# Full_bridge-2-Buck_drives_-10.net
KiCad netlist of a schematic drawn in Altium Designer
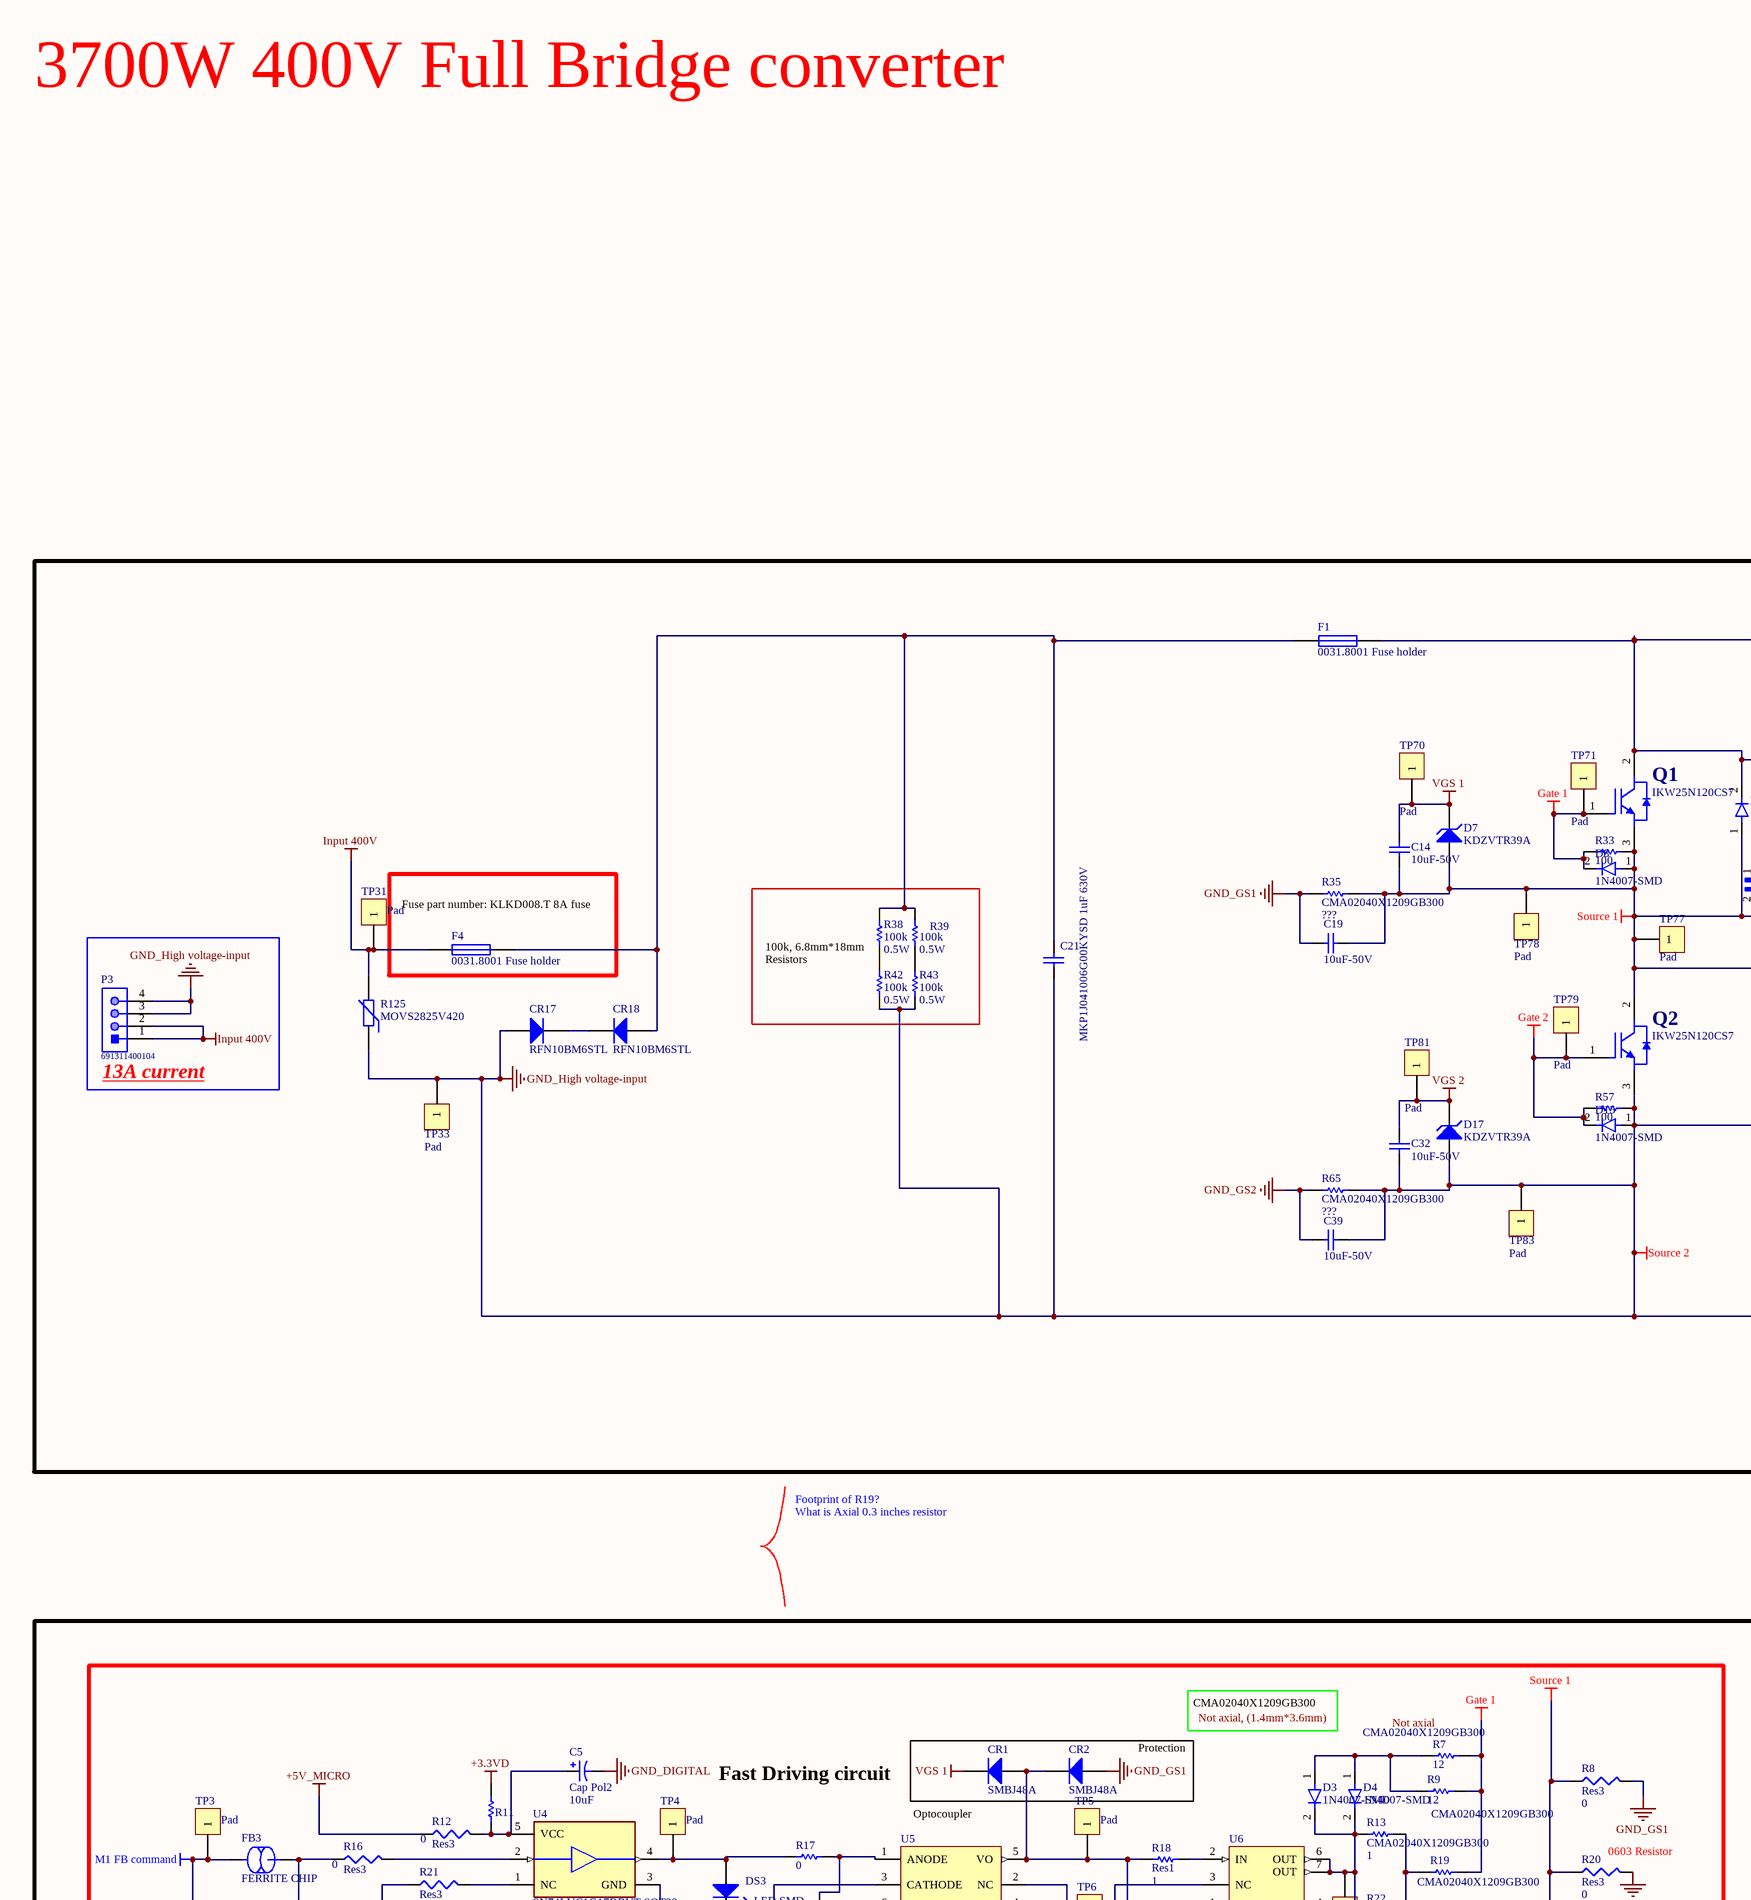
[diagram p0: Full bridge-2-Buck drives -10.SchDoc, top left]
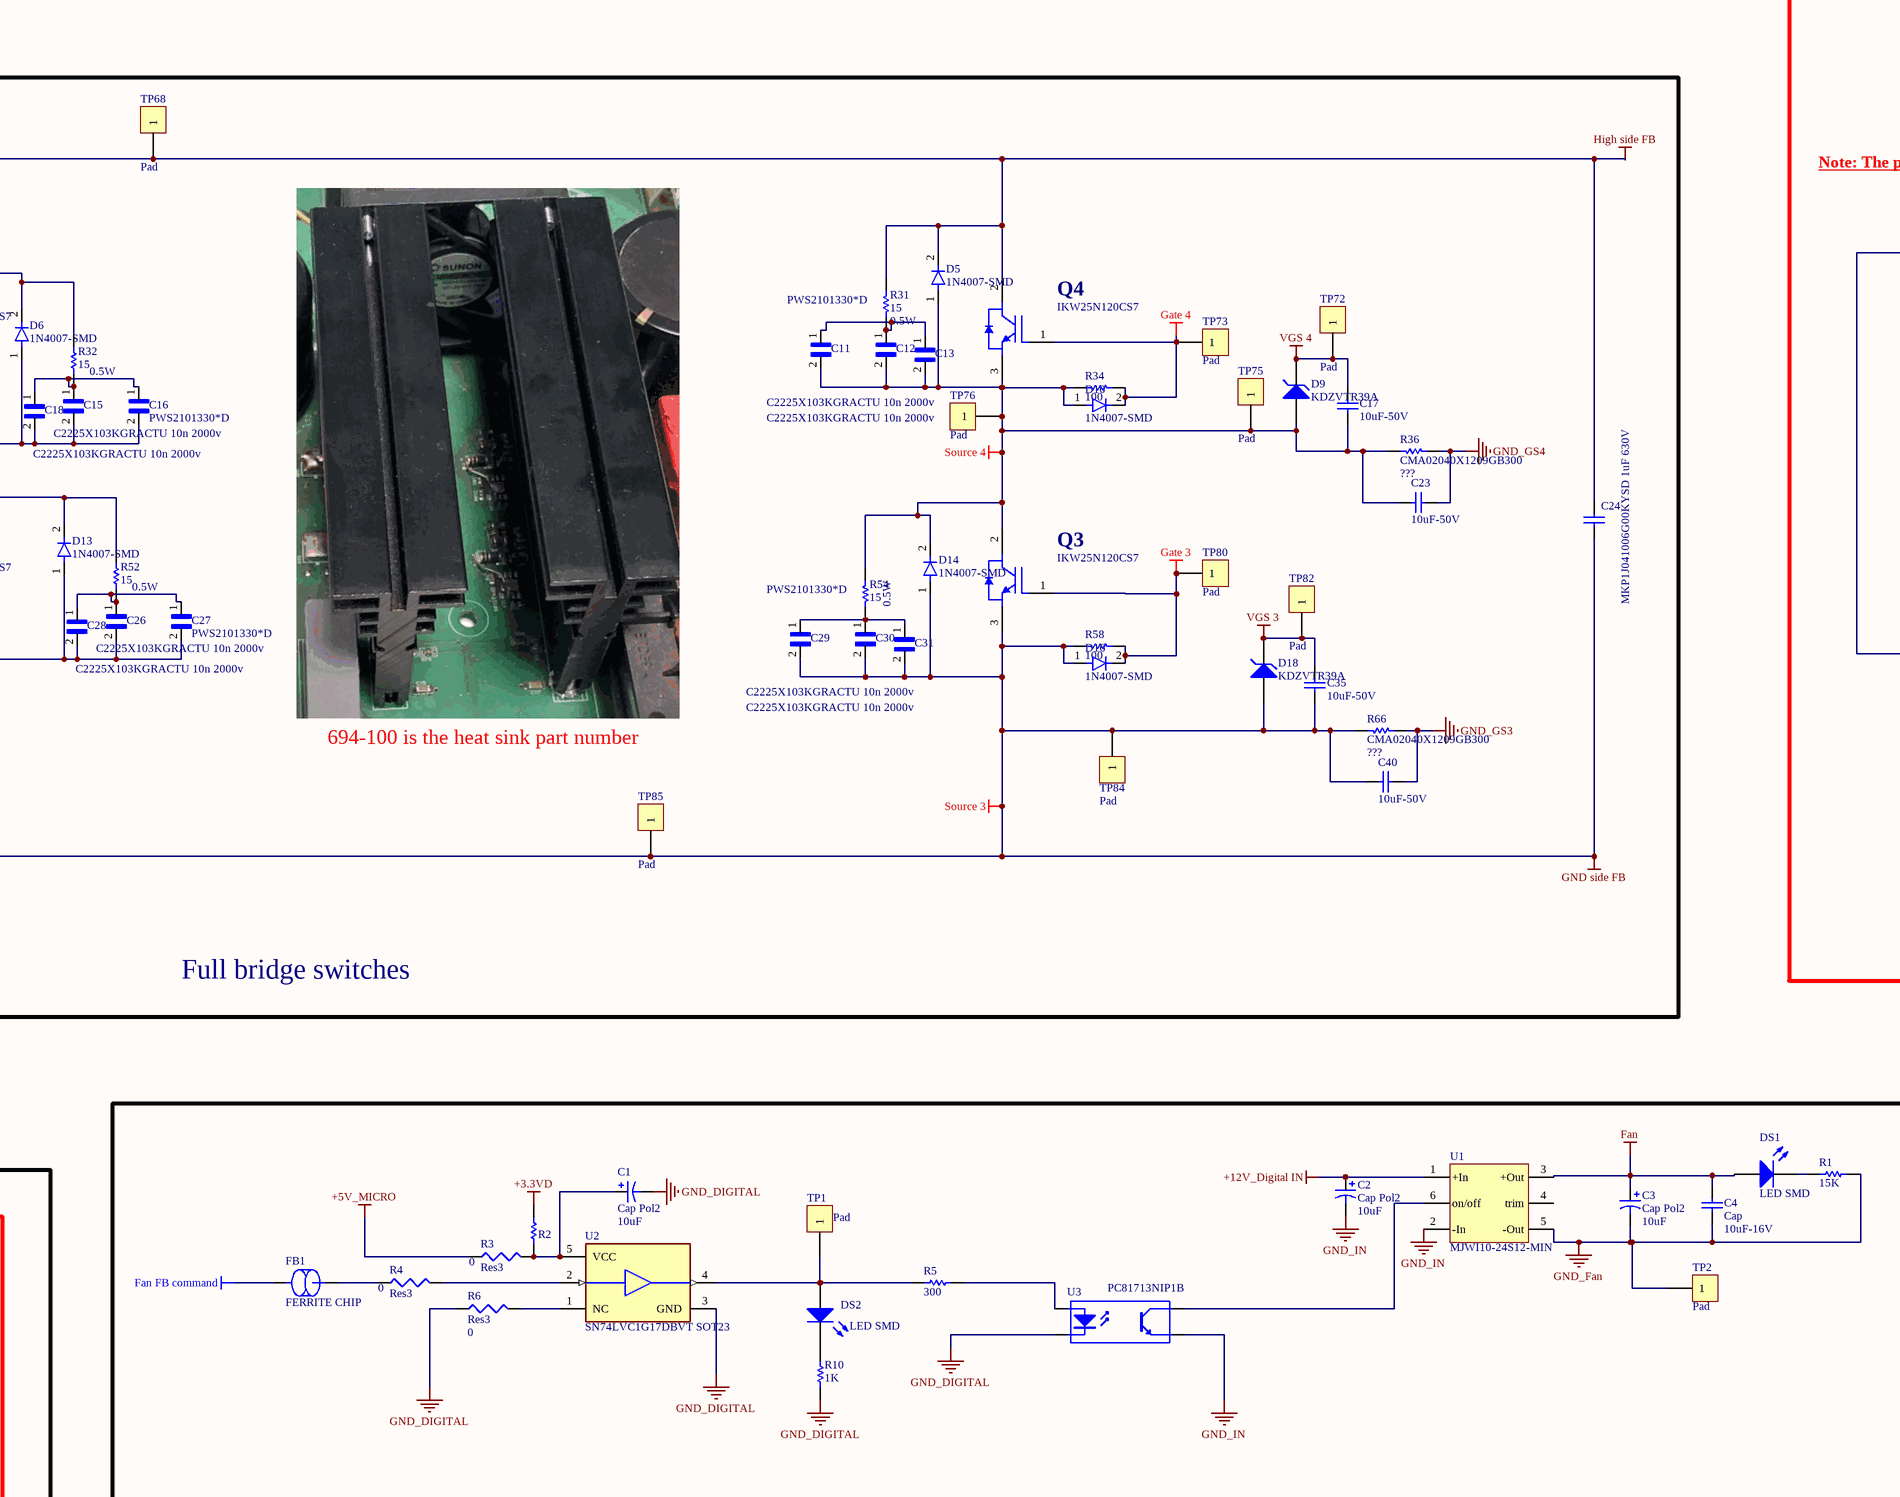
[diagram p1: Full bridge-2-Buck drives -10.SchDoc, top middle]
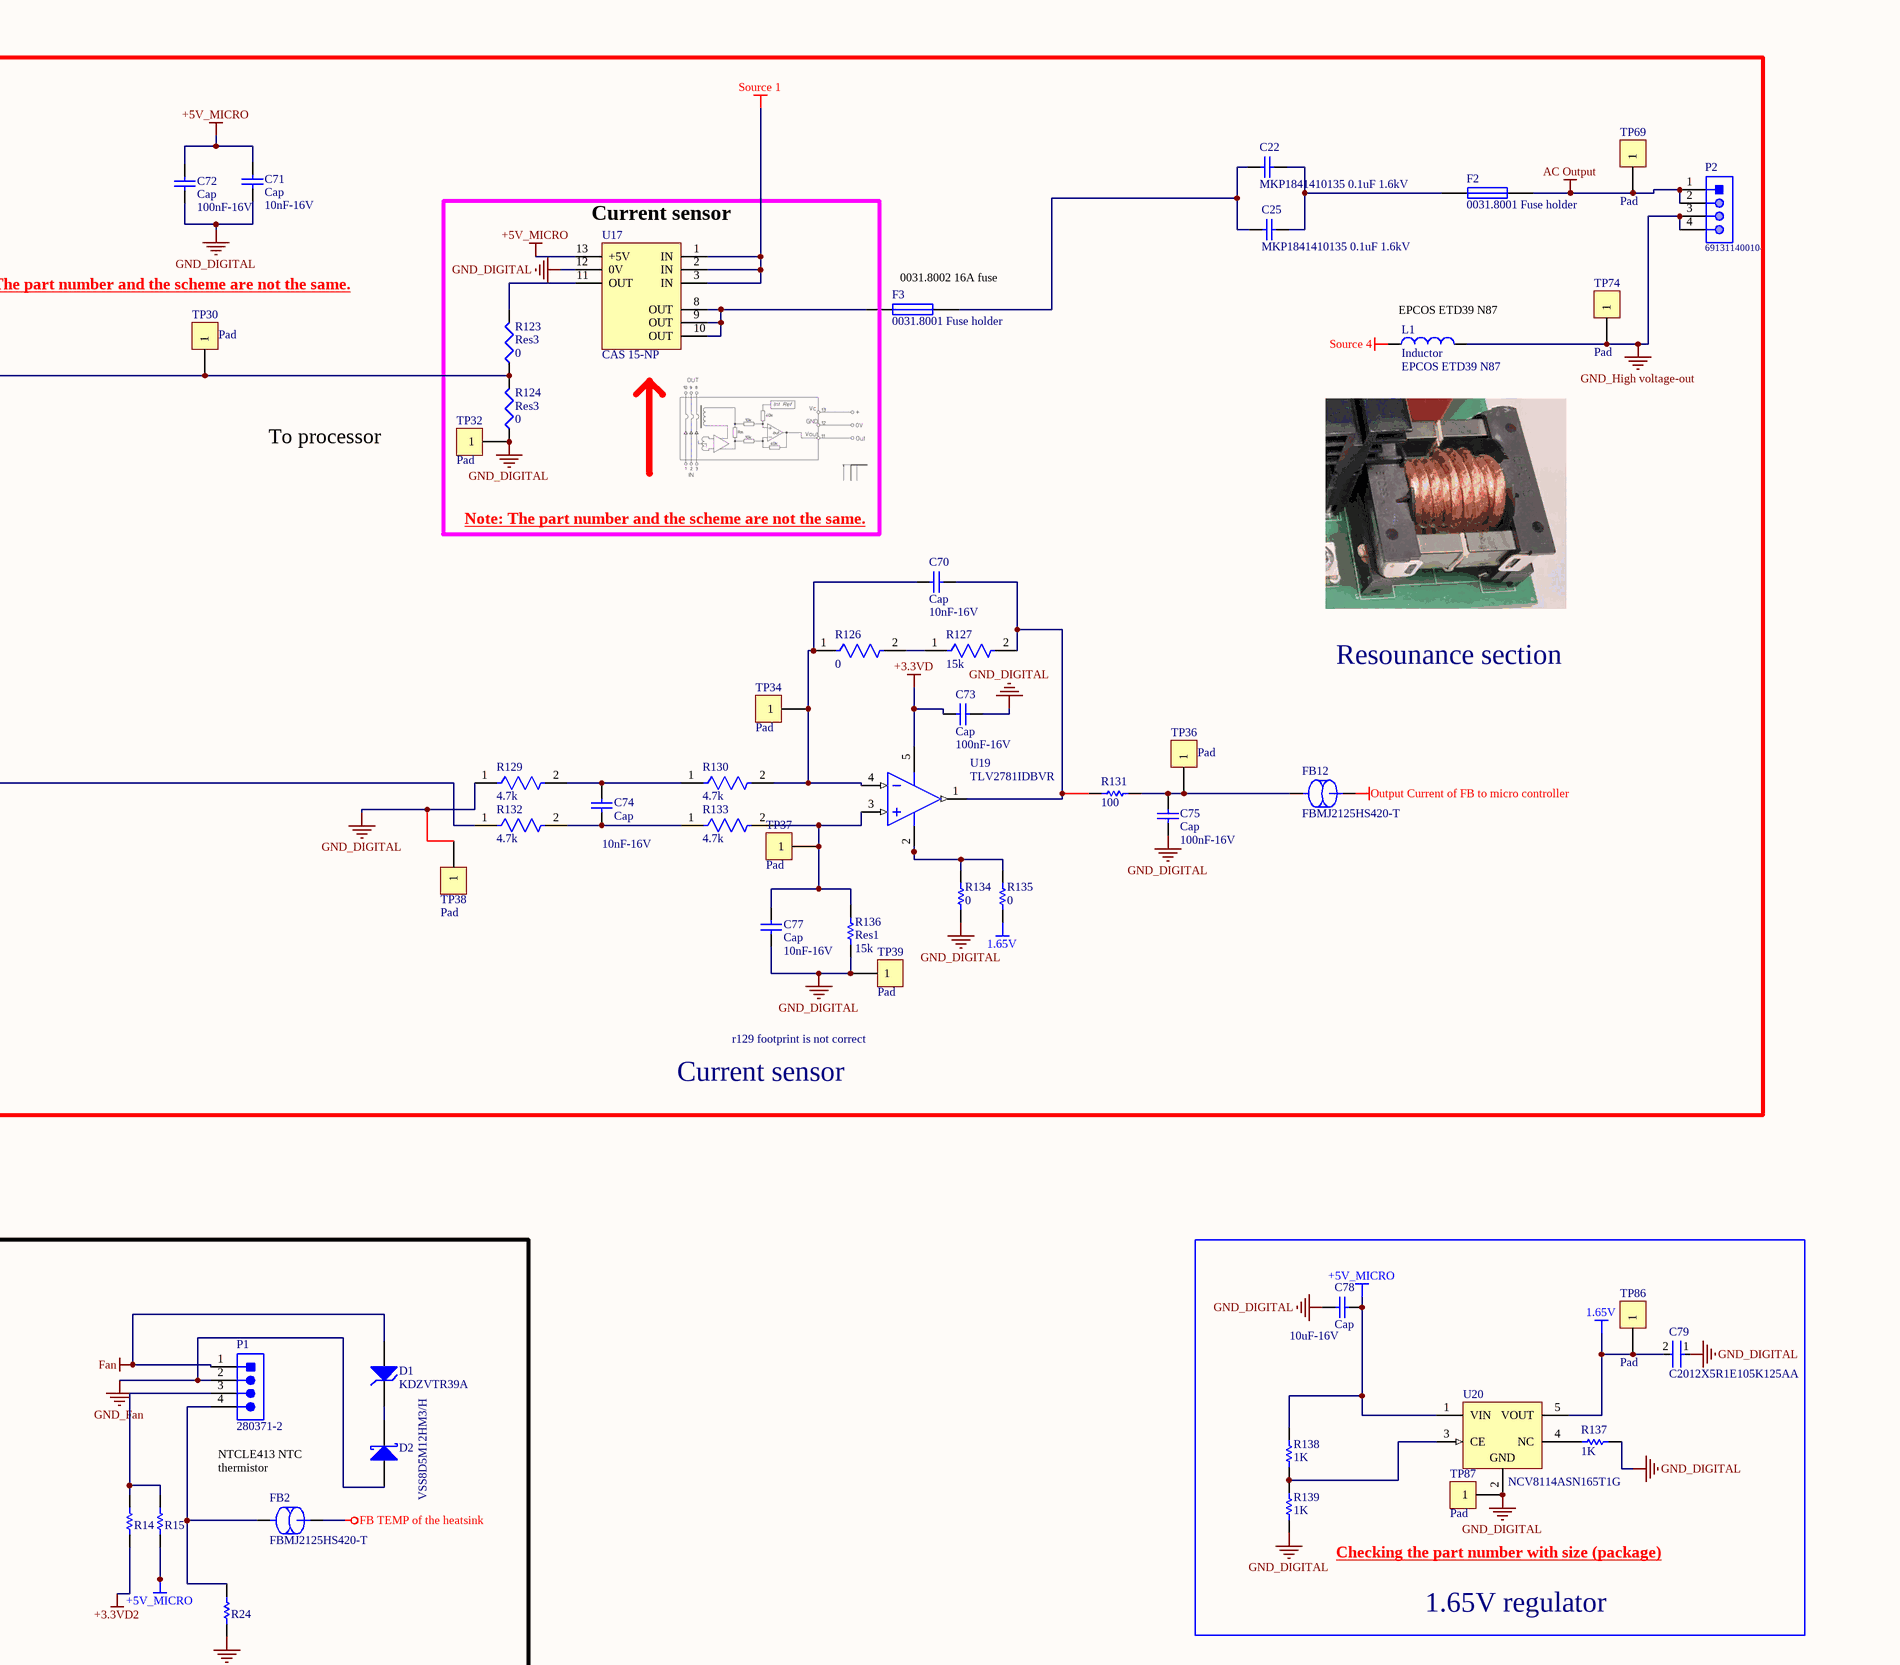
[diagram p2: Full bridge-2-Buck drives -10.SchDoc, top right]
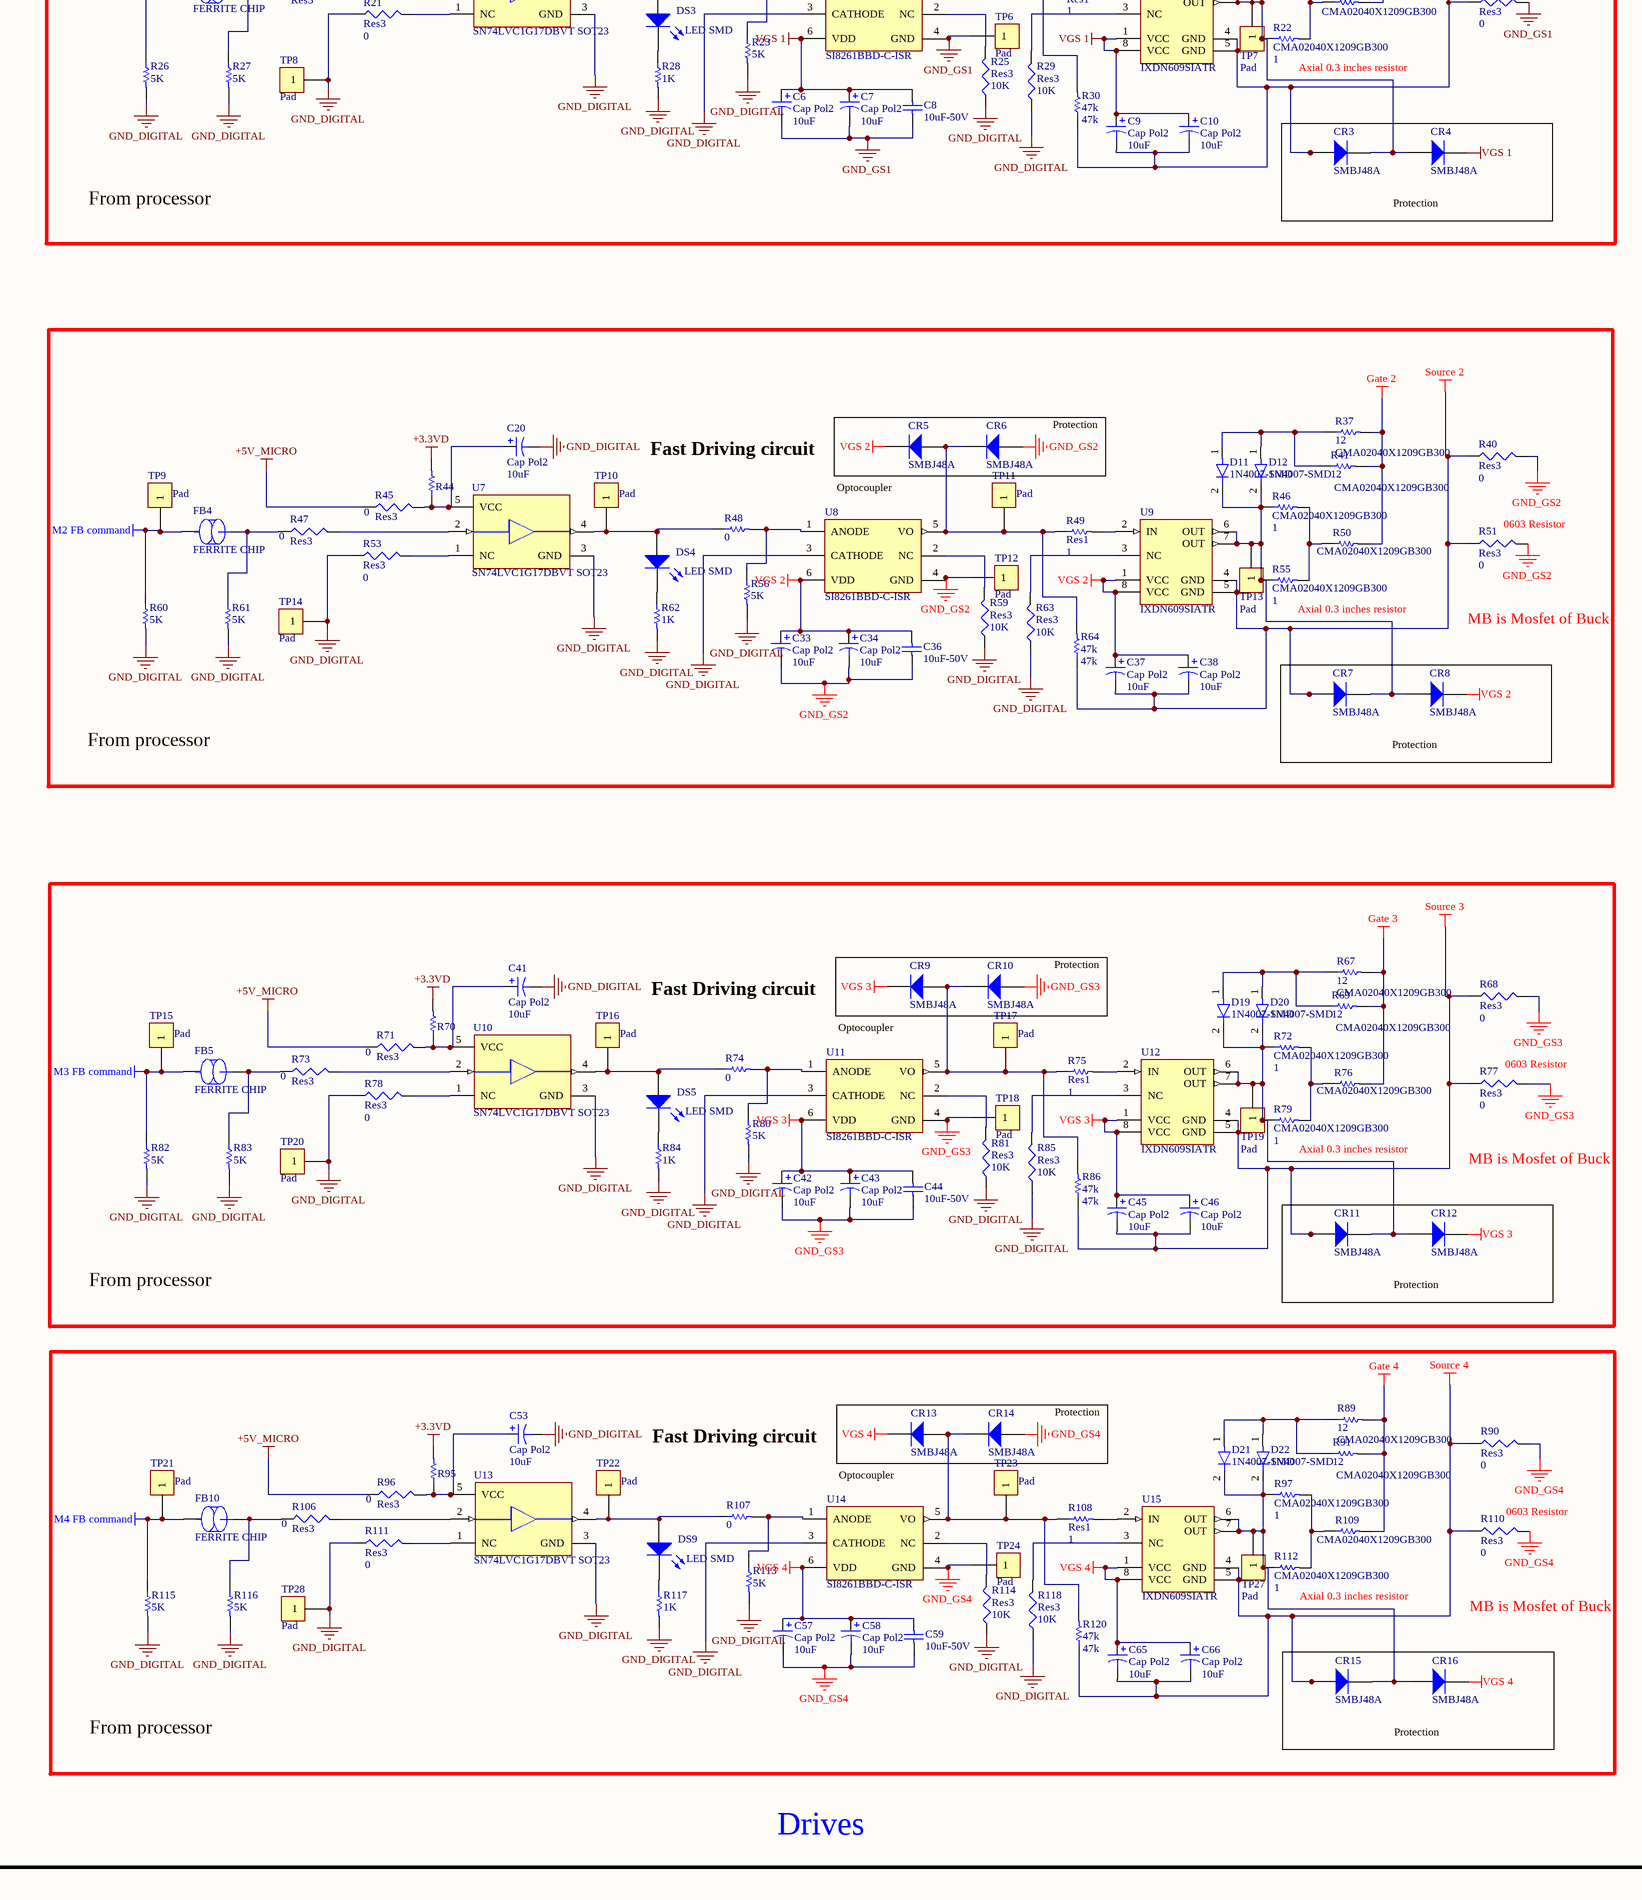
[diagram p3: Full bridge-2-Buck drives -10.SchDoc, bottom left]
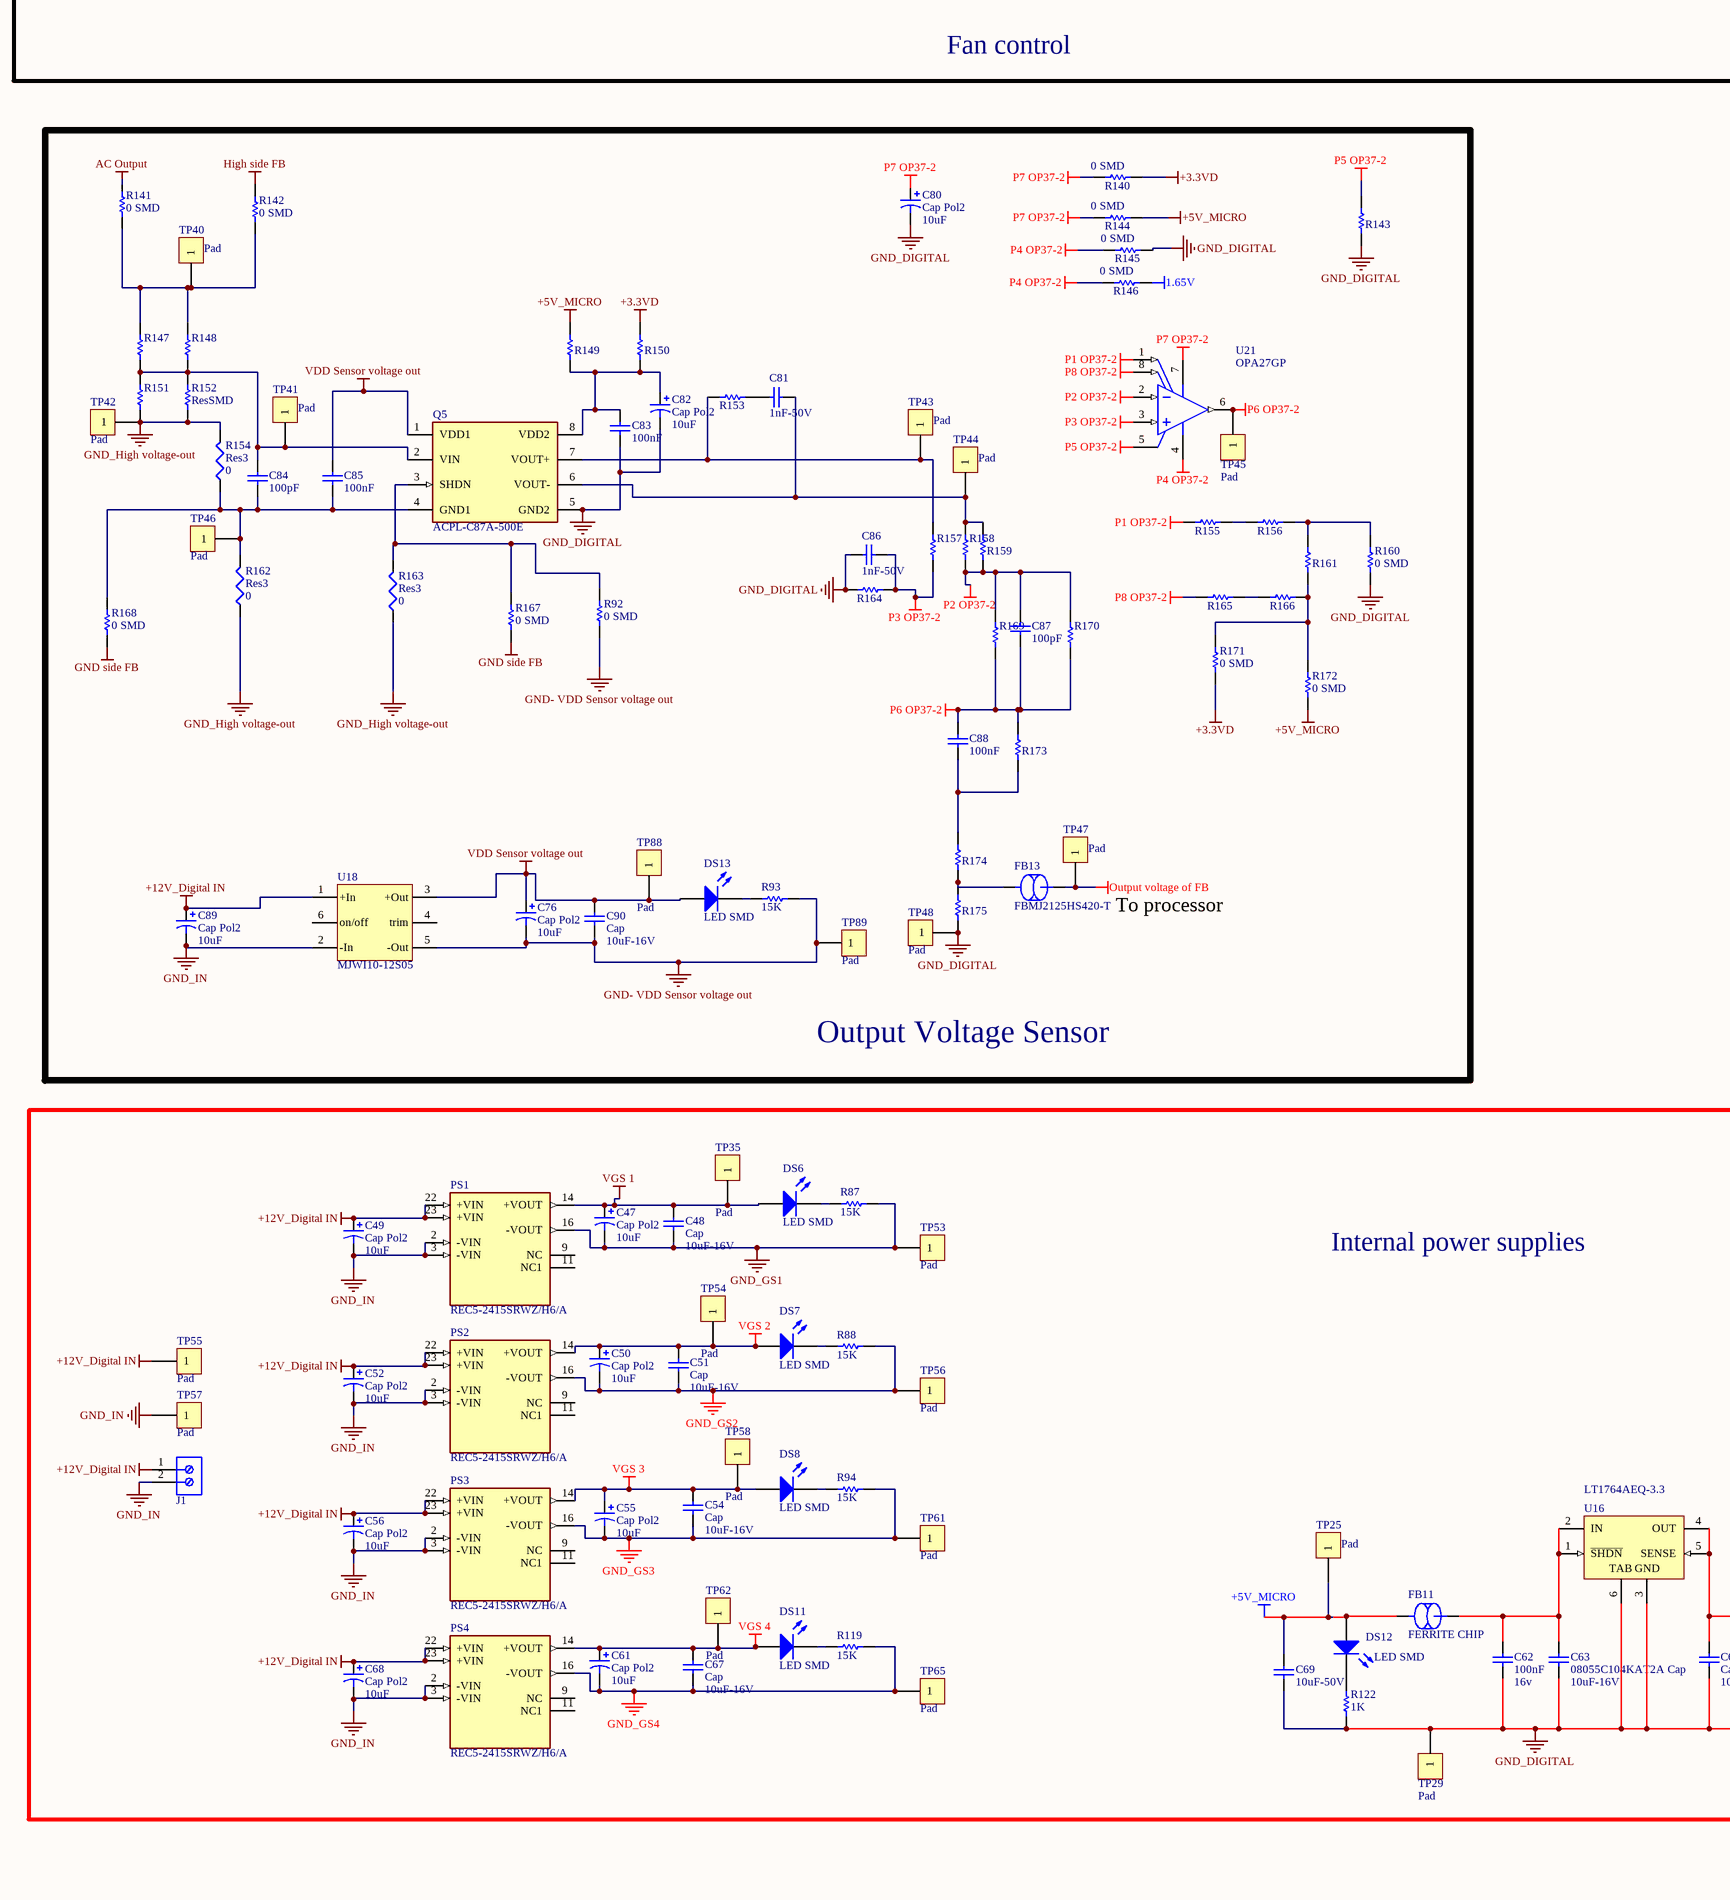
[diagram p4: Full bridge-2-Buck drives -10.SchDoc, bottom middle]
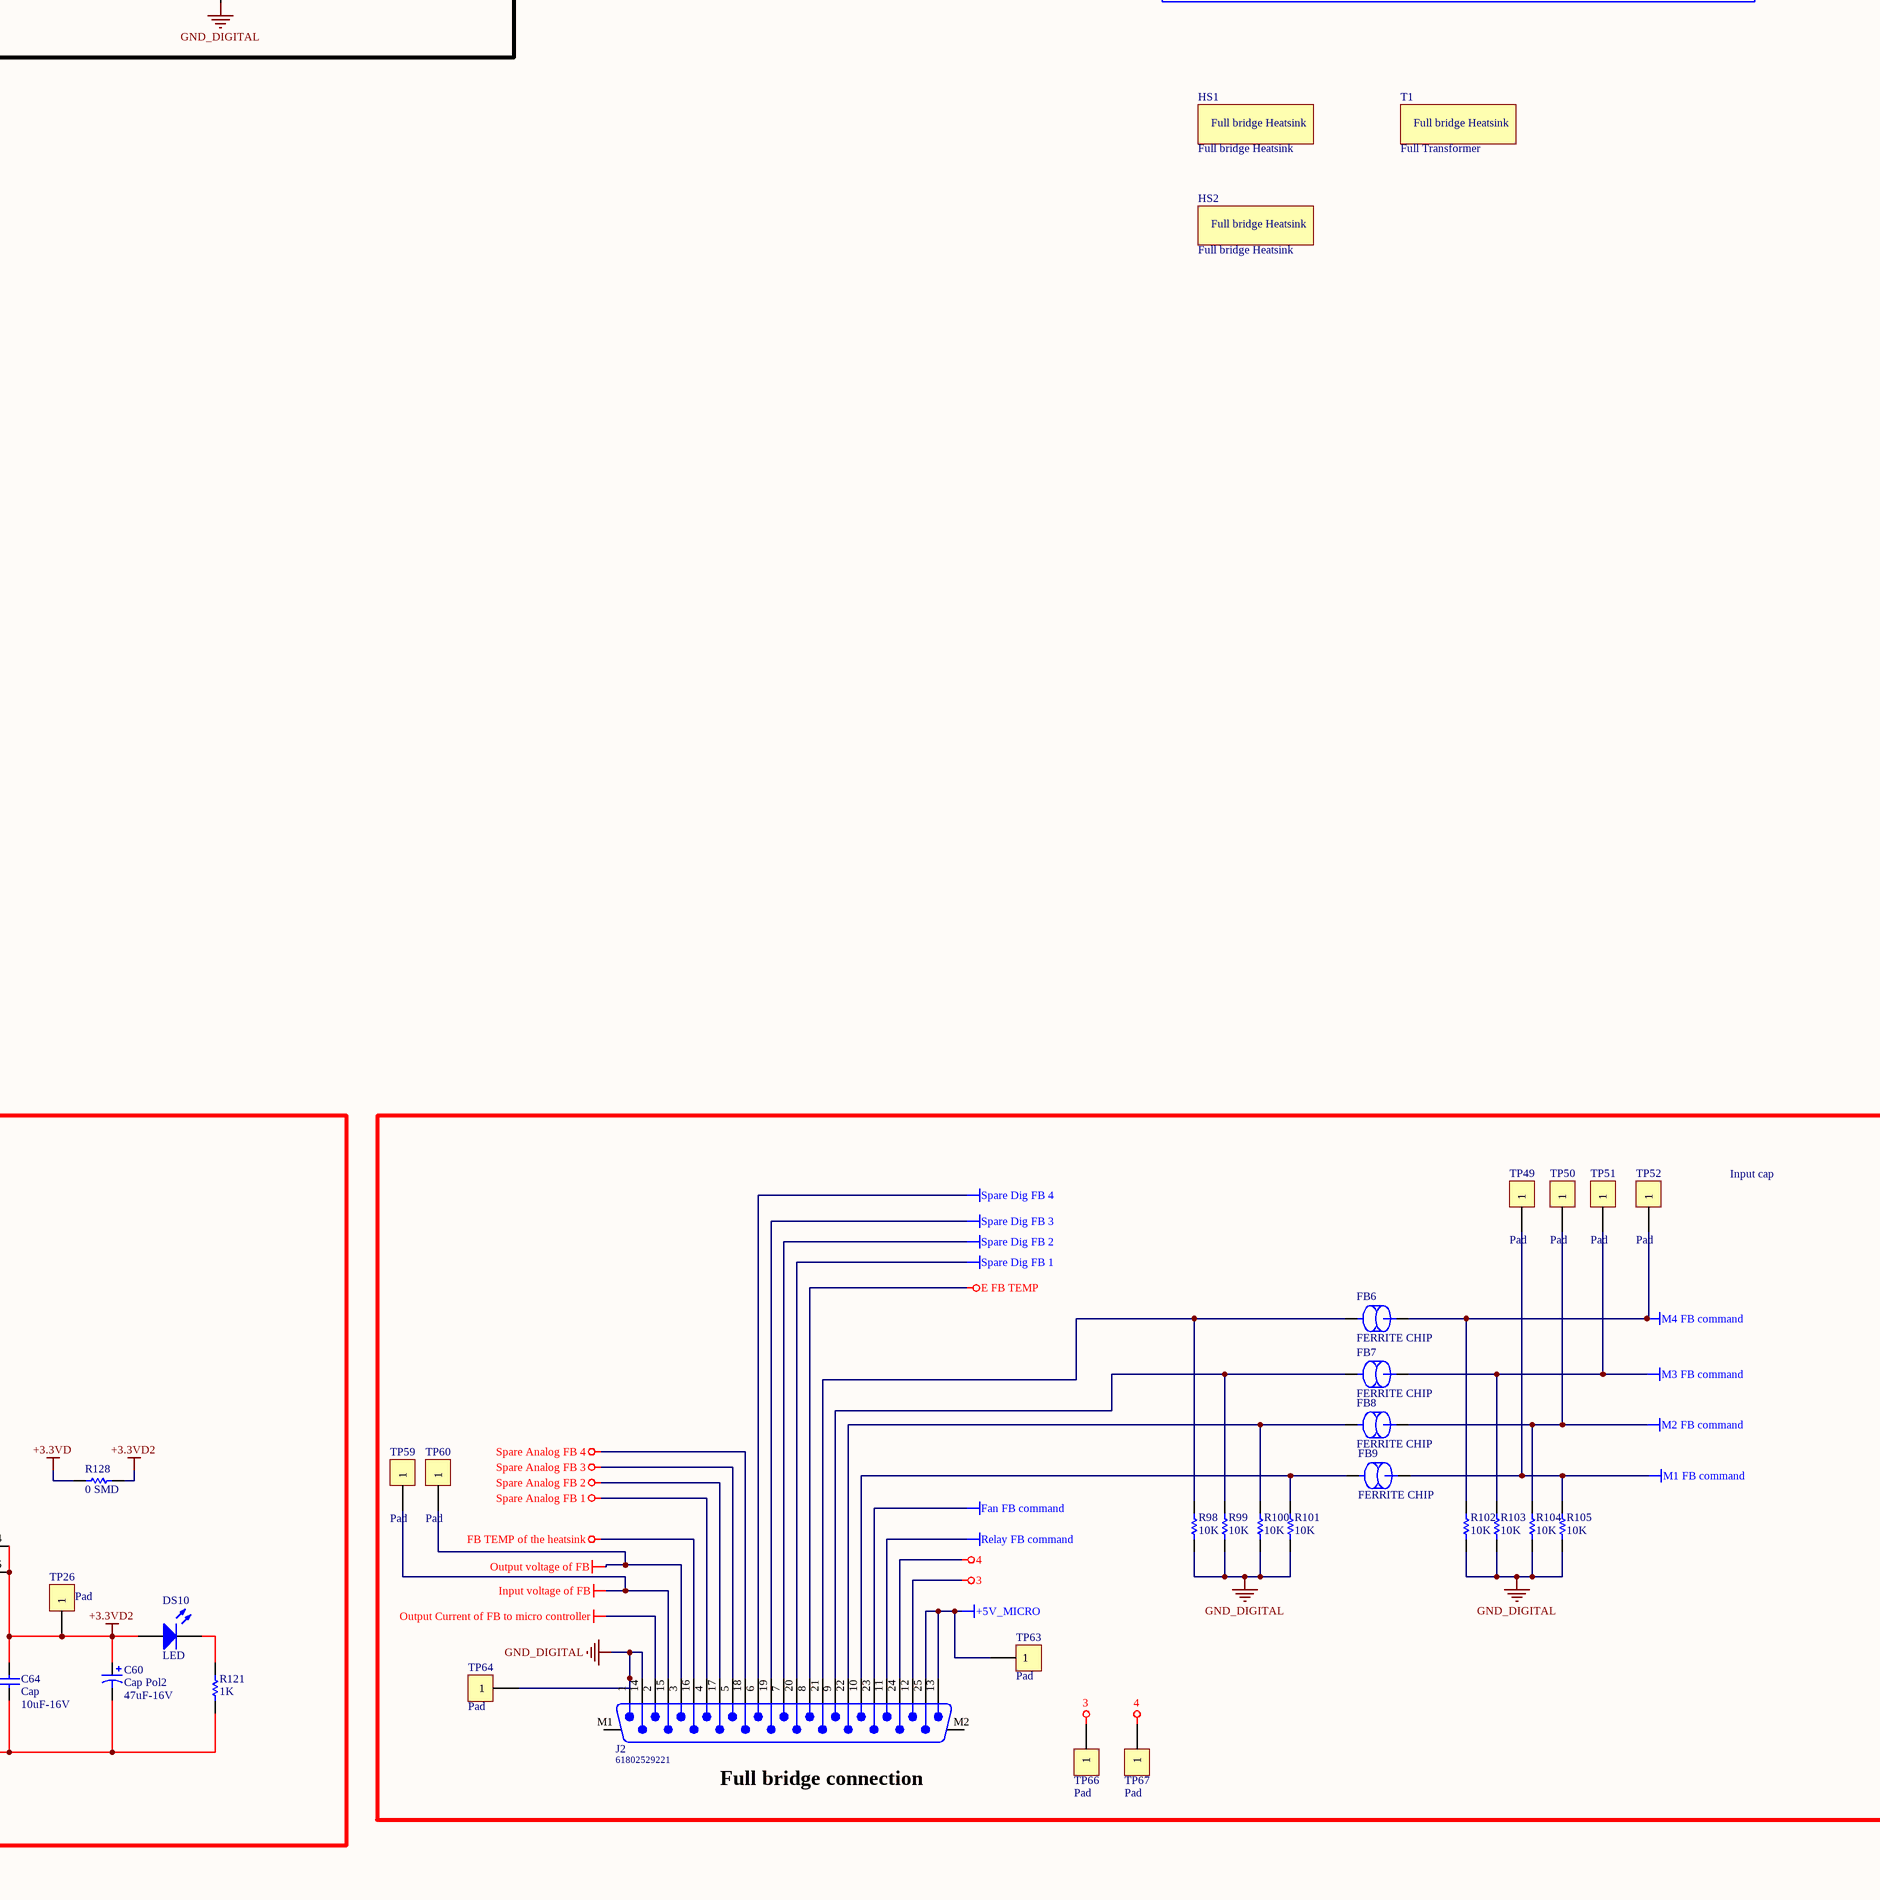
[diagram p5: Full bridge-2-Buck drives -10.SchDoc, bottom right]

(export (version "E")
  (design (tool "Eeschema 10.0.6"))
  (components
    (comp (ref "C1")
      (value "Cap Pol2")
      (footprint "Buck:CAPAE430X565N")
      (description "Polarized Capacitor (Axial)")
      (fields (field (name "ALTIUM_VALUE") "10uF") (field (name "PUBLISHER") "Altium Limited"))
      (libsource (lib "SCH") (part "Cap Pol2"))
    )
    (comp (ref "C2")
      (value "Cap Pol2")
      (footprint "Buck:CAPAE430X565N")
      (description "Polarized Capacitor (Axial)")
      (fields (field (name "ALTIUM_VALUE") "10uF") (field (name "PUBLISHER") "Altium Limited"))
      (libsource (lib "SCH") (part "Cap Pol2"))
    )
    (comp (ref "C3")
      (value "Cap Pol2")
      (footprint "Buck:CAPAE430X565N")
      (description "Polarized Capacitor (Axial)")
      (fields (field (name "ALTIUM_VALUE") "10uF") (field (name "PUBLISHER") "Altium Limited"))
      (libsource (lib "SCH") (part "Cap Pol2"))
    )
    (comp (ref "C4")
      (value "Cap")
      (footprint "Buck:C0805")
      (description "Capacitor")
      (fields (field (name "ALTIUM_VALUE") "10uF-16V") (field (name "PUBLISHER") "Altium Limited"))
      (libsource (lib "SCH") (part "Cap"))
    )
    (comp (ref "C5")
      (value "Cap Pol2")
      (footprint "Buck:CAPAE430X565N")
      (description "Polarized Capacitor (Axial)")
      (fields (field (name "ALTIUM_VALUE") "10uF") (field (name "PUBLISHER") "Altium Limited"))
      (libsource (lib "SCH") (part "Cap Pol2"))
    )
    (comp (ref "C6")
      (value "Cap Pol2")
      (footprint "Buck:CAPAE430X565N")
      (description "Polarized Capacitor (Axial)")
      (fields (field (name "ALTIUM_VALUE") "10uF") (field (name "PUBLISHER") "Altium Limited"))
      (libsource (lib "SCH") (part "Cap Pol2"))
    )
    (comp (ref "C7")
      (value "Cap Pol2")
      (footprint "Buck:CAPAE430X565N")
      (description "Polarized Capacitor (Axial)")
      (fields (field (name "ALTIUM_VALUE") "10uF") (field (name "PUBLISHER") "Altium Limited"))
      (libsource (lib "SCH") (part "Cap Pol2"))
    )
    (comp (ref "C8") (value "10uF-50V") (footprint "Buck:C0805") (libsource (lib "") (part "CapSMD_1")))
    (comp (ref "C9")
      (value "Cap Pol2")
      (footprint "Buck:CAPAE430X565N")
      (description "Polarized Capacitor (Axial)")
      (fields (field (name "ALTIUM_VALUE") "10uF") (field (name "PUBLISHER") "Altium Limited"))
      (libsource (lib "SCH") (part "Cap Pol2"))
    )
    (comp (ref "C10")
      (value "Cap Pol2")
      (footprint "Buck:CAPAE430X565N")
      (description "Polarized Capacitor (Axial)")
      (fields (field (name "ALTIUM_VALUE") "10uF") (field (name "PUBLISHER") "Altium Limited"))
      (libsource (lib "SCH") (part "Cap Pol2"))
    )
    (comp (ref "C11")
      (value "PWS2101330*D")
      (footprint "Buck:PWS2101330KD")
      (fields (field (name "MF") "AVX") (field (name "MP") "LD052C153JAB2A"))
      (libsource (lib "") (part "Ceramic disk capacitor_1"))
    )
    (comp (ref "C12")
      (value "C2225X103KGRACTU 10n 2000v")
      (footprint "Buck:C2225")
      (fields (field (name "MF") "AVX") (field (name "MP") "LD052C153JAB2A"))
      (libsource (lib "") (part "Ceramic disk capacitor_1"))
    )
    (comp (ref "C13")
      (value "C2225X103KGRACTU 10n 2000v")
      (footprint "Buck:C2225")
      (fields (field (name "MF") "AVX") (field (name "MP") "LD052C153JAB2A"))
      (libsource (lib "") (part "Ceramic disk capacitor_1"))
    )
    (comp (ref "C14") (value "10uF-50V") (footprint "Buck:C0805") (libsource (lib "") (part "CapSMD_1")))
    (comp (ref "C15")
      (value "C2225X103KGRACTU 10n 2000v")
      (footprint "Buck:C2225")
      (fields (field (name "MF") "AVX") (field (name "MP") "LD052C153JAB2A"))
      (libsource (lib "Capacitors dip") (part "Ceramic disk capacitor"))
    )
    (comp (ref "C16")
      (value "PWS2101330*D")
      (footprint "Buck:PWS2101330KD")
      (fields (field (name "MF") "AVX") (field (name "MP") "LD052C153JAB2A"))
      (libsource (lib "Capacitors dip") (part "Ceramic disk capacitor"))
    )
    (comp (ref "C17") (value "10uF-50V") (footprint "Buck:C0805") (libsource (lib "") (part "CapSMD_1")))
    (comp (ref "C18")
      (value "C2225X103KGRACTU 10n 2000v")
      (footprint "Buck:C2225")
      (fields (field (name "MF") "AVX") (field (name "MP") "LD052C153JAB2A"))
      (libsource (lib "Capacitors dip") (part "Ceramic disk capacitor"))
    )
    (comp (ref "C19") (value "10uF-50V") (footprint "Buck:C0805") (libsource (lib "") (part "CapSMD_1")))
    (comp (ref "C20")
      (value "Cap Pol2")
      (footprint "Buck:CAPAE430X565N")
      (description "Polarized Capacitor (Axial)")
      (fields (field (name "ALTIUM_VALUE") "10uF") (field (name "PUBLISHER") "Altium Limited"))
      (libsource (lib "SCH") (part "Cap Pol2"))
    )
    (comp (ref "C21")
      (value "MKP1J041006G00KYSD 1uF 630V")
      (footprint "Buck:MKP10_31x17-P27.5mm")
      (libsource (lib "MYLIB") (part "CapSMD"))
    )
    (comp (ref "C22")
      (value "MKP1841410135 0.1uF 1.6kV")
      (footprint "Buck:MKP1841410135")
      (libsource (lib "MYLIB") (part "CapSMD"))
    )
    (comp (ref "C23") (value "10uF-50V") (footprint "Buck:C0805") (libsource (lib "") (part "CapSMD_1")))
    (comp (ref "C24")
      (value "MKP1J041006G00KYSD 1uF 630V")
      (footprint "Buck:MKP10_31x17-P27.5mm")
      (libsource (lib "MYLIB") (part "CapSMD"))
    )
    (comp (ref "C25")
      (value "MKP1841410135 0.1uF 1.6kV")
      (footprint "Buck:MKP1841410135")
      (libsource (lib "MYLIB") (part "CapSMD"))
    )
    (comp (ref "C26")
      (value "C2225X103KGRACTU 10n 2000v")
      (footprint "Buck:C2225")
      (fields (field (name "MF") "AVX") (field (name "MP") "LD052C153JAB2A"))
      (libsource (lib "Capacitors dip") (part "Ceramic disk capacitor"))
    )
    (comp (ref "C27")
      (value "PWS2101330*D")
      (footprint "Buck:PWS2101330KD")
      (fields (field (name "MF") "AVX") (field (name "MP") "LD052C153JAB2A"))
      (libsource (lib "Capacitors dip") (part "Ceramic disk capacitor"))
    )
    (comp (ref "C28")
      (value "C2225X103KGRACTU 10n 2000v")
      (footprint "Buck:C2225")
      (fields (field (name "MF") "AVX") (field (name "MP") "LD052C153JAB2A"))
      (libsource (lib "Capacitors dip") (part "Ceramic disk capacitor"))
    )
    (comp (ref "C29")
      (value "PWS2101330*D")
      (footprint "Buck:PWS2101330KD")
      (fields (field (name "MF") "AVX") (field (name "MP") "LD052C153JAB2A"))
      (libsource (lib "") (part "Ceramic disk capacitor_1"))
    )
    (comp (ref "C30")
      (value "C2225X103KGRACTU 10n 2000v")
      (footprint "Buck:C2225")
      (fields (field (name "MF") "AVX") (field (name "MP") "LD052C153JAB2A"))
      (libsource (lib "") (part "Ceramic disk capacitor_1"))
    )
    (comp (ref "C31")
      (value "C2225X103KGRACTU 10n 2000v")
      (footprint "Buck:C2225")
      (fields (field (name "MF") "AVX") (field (name "MP") "LD052C153JAB2A"))
      (libsource (lib "") (part "Ceramic disk capacitor_1"))
    )
    (comp (ref "C32") (value "10uF-50V") (footprint "Buck:C0805") (libsource (lib "") (part "CapSMD_1")))
    (comp (ref "C33")
      (value "Cap Pol2")
      (footprint "Buck:CAPAE430X565N")
      (description "Polarized Capacitor (Axial)")
      (fields (field (name "ALTIUM_VALUE") "10uF") (field (name "PUBLISHER") "Altium Limited"))
      (libsource (lib "SCH") (part "Cap Pol2"))
    )
    (comp (ref "C34")
      (value "Cap Pol2")
      (footprint "Buck:CAPAE430X565N")
      (description "Polarized Capacitor (Axial)")
      (fields (field (name "ALTIUM_VALUE") "10uF") (field (name "PUBLISHER") "Altium Limited"))
      (libsource (lib "SCH") (part "Cap Pol2"))
    )
    (comp (ref "C35") (value "10uF-50V") (footprint "Buck:C0805") (libsource (lib "") (part "CapSMD_1")))
    (comp (ref "C36") (value "10uF-50V") (footprint "Buck:C0805") (libsource (lib "") (part "CapSMD_1")))
    (comp (ref "C37")
      (value "Cap Pol2")
      (footprint "Buck:CAPAE430X565N")
      (description "Polarized Capacitor (Axial)")
      (fields (field (name "ALTIUM_VALUE") "10uF") (field (name "PUBLISHER") "Altium Limited"))
      (libsource (lib "SCH") (part "Cap Pol2"))
    )
    (comp (ref "C38")
      (value "Cap Pol2")
      (footprint "Buck:CAPAE430X565N")
      (description "Polarized Capacitor (Axial)")
      (fields (field (name "ALTIUM_VALUE") "10uF") (field (name "PUBLISHER") "Altium Limited"))
      (libsource (lib "SCH") (part "Cap Pol2"))
    )
    (comp (ref "C39") (value "10uF-50V") (footprint "Buck:C0805") (libsource (lib "") (part "CapSMD_1")))
    (comp (ref "C40") (value "10uF-50V") (footprint "Buck:C0805") (libsource (lib "") (part "CapSMD_1")))
    (comp (ref "C41")
      (value "Cap Pol2")
      (footprint "Buck:CAPAE430X565N")
      (description "Polarized Capacitor (Axial)")
      (fields (field (name "ALTIUM_VALUE") "10uF") (field (name "PUBLISHER") "Altium Limited"))
      (libsource (lib "SCH") (part "Cap Pol2"))
    )
    (comp (ref "C42")
      (value "Cap Pol2")
      (footprint "Buck:CAPAE430X565N")
      (description "Polarized Capacitor (Axial)")
      (fields (field (name "ALTIUM_VALUE") "10uF") (field (name "PUBLISHER") "Altium Limited"))
      (libsource (lib "SCH") (part "Cap Pol2"))
    )
    (comp (ref "C43")
      (value "Cap Pol2")
      (footprint "Buck:CAPAE430X565N")
      (description "Polarized Capacitor (Axial)")
      (fields (field (name "ALTIUM_VALUE") "10uF") (field (name "PUBLISHER") "Altium Limited"))
      (libsource (lib "SCH") (part "Cap Pol2"))
    )
    (comp (ref "C44") (value "10uF-50V") (footprint "Buck:C0805") (libsource (lib "") (part "CapSMD_1")))
    (comp (ref "C45")
      (value "Cap Pol2")
      (footprint "Buck:CAPAE430X565N")
      (description "Polarized Capacitor (Axial)")
      (fields (field (name "ALTIUM_VALUE") "10uF") (field (name "PUBLISHER") "Altium Limited"))
      (libsource (lib "SCH") (part "Cap Pol2"))
    )
    (comp (ref "C46")
      (value "Cap Pol2")
      (footprint "Buck:CAPAE430X565N")
      (description "Polarized Capacitor (Axial)")
      (fields (field (name "ALTIUM_VALUE") "10uF") (field (name "PUBLISHER") "Altium Limited"))
      (libsource (lib "SCH") (part "Cap Pol2"))
    )
    (comp (ref "C47")
      (value "Cap Pol2")
      (footprint "Buck:CAPAE430X565N")
      (description "Polarized Capacitor (Axial)")
      (fields (field (name "ALTIUM_VALUE") "10uF") (field (name "PUBLISHER") "Altium Limited"))
      (libsource (lib "SCH") (part "Cap Pol2"))
    )
    (comp (ref "C48")
      (value "Cap")
      (footprint "Buck:C0805")
      (description "Capacitor")
      (fields (field (name "ALTIUM_VALUE") "10uF-16V") (field (name "PUBLISHER") "Altium Limited"))
      (libsource (lib "SCH") (part "Cap"))
    )
    (comp (ref "C49")
      (value "Cap Pol2")
      (footprint "Buck:CAPAE430X565N")
      (description "Polarized Capacitor (Axial)")
      (fields (field (name "ALTIUM_VALUE") "10uF") (field (name "PUBLISHER") "Altium Limited"))
      (libsource (lib "SCH") (part "Cap Pol2"))
    )
    (comp (ref "C50")
      (value "Cap Pol2")
      (footprint "Buck:CAPAE430X565N")
      (description "Polarized Capacitor (Axial)")
      (fields (field (name "ALTIUM_VALUE") "10uF") (field (name "PUBLISHER") "Altium Limited"))
      (libsource (lib "SCH") (part "Cap Pol2"))
    )
    (comp (ref "C51")
      (value "Cap")
      (footprint "Buck:C0805")
      (description "Capacitor")
      (fields (field (name "ALTIUM_VALUE") "10uF-16V") (field (name "PUBLISHER") "Altium Limited"))
      (libsource (lib "SCH") (part "Cap"))
    )
    (comp (ref "C52")
      (value "Cap Pol2")
      (footprint "Buck:CAPAE430X565N")
      (description "Polarized Capacitor (Axial)")
      (fields (field (name "ALTIUM_VALUE") "10uF") (field (name "PUBLISHER") "Altium Limited"))
      (libsource (lib "SCH") (part "Cap Pol2"))
    )
    (comp (ref "C53")
      (value "Cap Pol2")
      (footprint "Buck:CAPAE430X565N")
      (description "Polarized Capacitor (Axial)")
      (fields (field (name "ALTIUM_VALUE") "10uF") (field (name "PUBLISHER") "Altium Limited"))
      (libsource (lib "SCH") (part "Cap Pol2"))
    )
    (comp (ref "C54")
      (value "Cap")
      (footprint "Buck:C0805")
      (description "Capacitor")
      (fields (field (name "ALTIUM_VALUE") "10uF-16V") (field (name "PUBLISHER") "Altium Limited"))
      (libsource (lib "SCH") (part "Cap"))
    )
    (comp (ref "C55")
      (value "Cap Pol2")
      (footprint "Buck:CAPAE430X565N")
      (description "Polarized Capacitor (Axial)")
      (fields (field (name "ALTIUM_VALUE") "10uF") (field (name "PUBLISHER") "Altium Limited"))
      (libsource (lib "SCH") (part "Cap Pol2"))
    )
    (comp (ref "C56")
      (value "Cap Pol2")
      (footprint "Buck:CAPAE430X565N")
      (description "Polarized Capacitor (Axial)")
      (fields (field (name "ALTIUM_VALUE") "10uF") (field (name "PUBLISHER") "Altium Limited"))
      (libsource (lib "SCH") (part "Cap Pol2"))
    )
    (comp (ref "C57")
      (value "Cap Pol2")
      (footprint "Buck:CAPAE430X565N")
      (description "Polarized Capacitor (Axial)")
      (fields (field (name "ALTIUM_VALUE") "10uF") (field (name "PUBLISHER") "Altium Limited"))
      (libsource (lib "SCH") (part "Cap Pol2"))
    )
    (comp (ref "C58")
      (value "Cap Pol2")
      (footprint "Buck:CAPAE430X565N")
      (description "Polarized Capacitor (Axial)")
      (fields (field (name "ALTIUM_VALUE") "10uF") (field (name "PUBLISHER") "Altium Limited"))
      (libsource (lib "SCH") (part "Cap Pol2"))
    )
    (comp (ref "C59") (value "10uF-50V") (footprint "Buck:C0805") (libsource (lib "") (part "CapSMD_1")))
    (comp (ref "C60")
      (value "Cap Pol2")
      (footprint "Buck:CAPAE430X565N")
      (description "Polarized Capacitor (Axial)")
      (fields (field (name "ALTIUM_VALUE") "47uF-16V") (field (name "PUBLISHER") "Altium Limited"))
      (libsource (lib "SCH") (part "Cap Pol2"))
    )
    (comp (ref "C61")
      (value "Cap Pol2")
      (footprint "Buck:CAPAE430X565N")
      (description "Polarized Capacitor (Axial)")
      (fields (field (name "ALTIUM_VALUE") "10uF") (field (name "PUBLISHER") "Altium Limited"))
      (libsource (lib "SCH") (part "Cap Pol2"))
    )
    (comp (ref "C62")
      (value "100nF")
      (footprint "Buck:C0805")
      (description "None polar capacitor")
      (fields (field (name "VOLTE") "16v"))
      (libsource (lib "Mylib") (part "Cap ceramic"))
    )
    (comp (ref "C63")
      (value "08055C104KAT2A Cap")
      (footprint "Buck:C0805")
      (description "Capacitor")
      (fields (field (name "ALTIUM_VALUE") "10uF-16V") (field (name "PUBLISHER") "Altium Limited"))
      (libsource (lib "SCH") (part "Cap"))
    )
    (comp (ref "C64")
      (value "Cap")
      (footprint "Buck:C0805")
      (description "Capacitor")
      (fields (field (name "ALTIUM_VALUE") "10uF-16V") (field (name "PUBLISHER") "Altium Limited"))
      (libsource (lib "SCH") (part "Cap"))
    )
    (comp (ref "C65")
      (value "Cap Pol2")
      (footprint "Buck:CAPAE430X565N")
      (description "Polarized Capacitor (Axial)")
      (fields (field (name "ALTIUM_VALUE") "10uF") (field (name "PUBLISHER") "Altium Limited"))
      (libsource (lib "SCH") (part "Cap Pol2"))
    )
    (comp (ref "C66")
      (value "Cap Pol2")
      (footprint "Buck:CAPAE430X565N")
      (description "Polarized Capacitor (Axial)")
      (fields (field (name "ALTIUM_VALUE") "10uF") (field (name "PUBLISHER") "Altium Limited"))
      (libsource (lib "SCH") (part "Cap Pol2"))
    )
    (comp (ref "C67")
      (value "Cap")
      (footprint "Buck:C0805")
      (description "Capacitor")
      (fields (field (name "ALTIUM_VALUE") "10uF-16V") (field (name "PUBLISHER") "Altium Limited"))
      (libsource (lib "SCH") (part "Cap"))
    )
    (comp (ref "C68")
      (value "Cap Pol2")
      (footprint "Buck:CAPAE430X565N")
      (description "Polarized Capacitor (Axial)")
      (fields (field (name "ALTIUM_VALUE") "10uF") (field (name "PUBLISHER") "Altium Limited"))
      (libsource (lib "SCH") (part "Cap Pol2"))
    )
    (comp (ref "C69") (value "10uF-50V") (footprint "Buck:C0805") (libsource (lib "") (part "CapSMD_1")))
    (comp (ref "C70")
      (value "Cap")
      (footprint "Buck:C0805")
      (description "Capacitor")
      (fields (field (name "ALTIUM_VALUE") "10nF-16V") (field (name "PUBLISHER") "Altium Limited"))
      (libsource (lib "SCH") (part "Cap"))
    )
    (comp (ref "C71")
      (value "Cap")
      (footprint "Buck:C0805")
      (description "Capacitor")
      (fields (field (name "ALTIUM_VALUE") "10nF-16V") (field (name "PUBLISHER") "Altium Limited"))
      (libsource (lib "SCH") (part "Cap"))
    )
    (comp (ref "C72")
      (value "Cap")
      (footprint "Buck:C0805")
      (description "Capacitor")
      (fields (field (name "ALTIUM_VALUE") "100nF-16V") (field (name "PUBLISHER") "Altium Limited"))
      (libsource (lib "SCH") (part "Cap"))
    )
    (comp (ref "C73")
      (value "Cap")
      (footprint "Buck:C0805")
      (description "Capacitor")
      (fields (field (name "ALTIUM_VALUE") "100nF-16V") (field (name "PUBLISHER") "Altium Limited"))
      (libsource (lib "SCH") (part "Cap"))
    )
    (comp (ref "C74")
      (value "Cap")
      (footprint "Buck:C0805")
      (description "Capacitor")
      (fields (field (name "ALTIUM_VALUE") "10nF-16V") (field (name "PUBLISHER") "Altium Limited"))
      (libsource (lib "SCH") (part "Cap"))
    )
    (comp (ref "C75")
      (value "Cap")
      (footprint "Buck:C0805")
      (description "Capacitor")
      (fields (field (name "ALTIUM_VALUE") "100nF-16V") (field (name "PUBLISHER") "Altium Limited"))
      (libsource (lib "SCH") (part "Cap"))
    )
    (comp (ref "C76")
      (value "Cap Pol2")
      (footprint "Buck:CAPAE430X565N")
      (description "Polarized Capacitor (Axial)")
      (fields (field (name "ALTIUM_VALUE") "10uF") (field (name "PUBLISHER") "Altium Limited"))
      (libsource (lib "SCH") (part "Cap Pol2"))
    )
    (comp (ref "C77")
      (value "Cap")
      (footprint "Buck:C0805")
      (description "Capacitor")
      (fields (field (name "ALTIUM_VALUE") "10nF-16V") (field (name "PUBLISHER") "Altium Limited"))
      (libsource (lib "SCH") (part "Cap"))
    )
    (comp (ref "C78")
      (value "Cap")
      (footprint "Buck:C0805")
      (description "Capacitor")
      (fields (field (name "ALTIUM_VALUE") "10uF-16V") (field (name "PUBLISHER") "Altium Limited"))
      (libsource (lib "SCH") (part "Cap"))
    )
    (comp (ref "C79")
      (value "C2012X5R1E105K125AA")
      (footprint "Buck:C0805")
      (description "Multilayer Ceramic Capacitors 1μF ±10% 25V X5R SMD 0805")
      (fields (field (name "VOLTAGE") "25V") (field (name "TOLERANCE") "10%"))
      (libsource (lib "Miscellaneous Devices") (part "b4654b650e69147ec39a6b967a45e02"))
    )
    (comp (ref "C80")
      (value "Cap Pol2")
      (footprint "Buck:C0805")
      (description "Polarized Capacitor (Axial)")
      (fields (field (name "ALTIUM_VALUE") "10uF") (field (name "PUBLISHER") "Altium Limited"))
      (libsource (lib "SCH") (part "Cap Pol2"))
    )
    (comp (ref "C81") (value "1nF-50V") (footprint "Buck:C0805") (libsource (lib "MYLIB") (part "CapSMD")))
    (comp (ref "C82")
      (value "Cap Pol2")
      (footprint "Buck:C0805")
      (description "Polarized Capacitor (Axial)")
      (fields (field (name "ALTIUM_VALUE") "10uF") (field (name "PUBLISHER") "Altium Limited"))
      (libsource (lib "SCH") (part "Cap Pol2"))
    )
    (comp (ref "C83")
      (value "100nF")
      (footprint "Buck:C0805")
      (description "None polar capacitor")
      (libsource (lib "Mylib") (part "Cap ceramic"))
    )
    (comp (ref "C84")
      (value "100pF")
      (footprint "Buck:C0805")
      (description "None polar capacitor")
      (libsource (lib "Mylib") (part "Cap ceramic"))
    )
    (comp (ref "C85")
      (value "100nF")
      (footprint "Buck:C0805")
      (description "None polar capacitor")
      (libsource (lib "Mylib") (part "Cap ceramic"))
    )
    (comp (ref "C86") (value "1nF-50V") (footprint "Buck:C0805") (libsource (lib "MYLIB") (part "CapSMD")))
    (comp (ref "C87")
      (value "100pF")
      (footprint "Buck:C0805")
      (description "None polar capacitor")
      (libsource (lib "Mylib") (part "Cap ceramic"))
    )
    (comp (ref "C88")
      (value "100nF")
      (footprint "Buck:C0805")
      (description "None polar capacitor")
      (libsource (lib "Mylib") (part "Cap ceramic"))
    )
    (comp (ref "C89")
      (value "Cap Pol2")
      (footprint "Buck:CAPAE430X565N")
      (description "Polarized Capacitor (Axial)")
      (fields (field (name "ALTIUM_VALUE") "10uF") (field (name "PUBLISHER") "Altium Limited"))
      (libsource (lib "SCH") (part "Cap Pol2"))
    )
    (comp (ref "C90")
      (value "Cap")
      (footprint "Buck:C0805")
      (description "Capacitor")
      (fields (field (name "ALTIUM_VALUE") "10uF-16V") (field (name "PUBLISHER") "Altium Limited"))
      (libsource (lib "SCH") (part "Cap"))
    )
    (comp (ref "CR1")
      (value "SMBJ48A")
      (footprint "Buck:SMB (DO-214AA)")
      (libsource (lib "MYLIB") (part "DiodeSMD4.5mm"))
    )
    (comp (ref "CR2")
      (value "SMBJ48A")
      (footprint "Buck:SMB (DO-214AA)")
      (libsource (lib "MYLIB") (part "DiodeSMD4.5mm"))
    )
    (comp (ref "CR3")
      (value "SMBJ48A")
      (footprint "Buck:SMB (DO-214AA)")
      (libsource (lib "MYLIB") (part "DiodeSMD4.5mm"))
    )
    (comp (ref "CR4")
      (value "SMBJ48A")
      (footprint "Buck:SMB (DO-214AA)")
      (libsource (lib "MYLIB") (part "DiodeSMD4.5mm"))
    )
    (comp (ref "CR5")
      (value "SMBJ48A")
      (footprint "Buck:SMB (DO-214AA)")
      (libsource (lib "MYLIB") (part "DiodeSMD4.5mm"))
    )
    (comp (ref "CR6")
      (value "SMBJ48A")
      (footprint "Buck:SMB (DO-214AA)")
      (libsource (lib "MYLIB") (part "DiodeSMD4.5mm"))
    )
    (comp (ref "CR7")
      (value "SMBJ48A")
      (footprint "Buck:SMB (DO-214AA)")
      (libsource (lib "MYLIB") (part "DiodeSMD4.5mm"))
    )
    (comp (ref "CR8")
      (value "SMBJ48A")
      (footprint "Buck:SMB (DO-214AA)")
      (libsource (lib "MYLIB") (part "DiodeSMD4.5mm"))
    )
    (comp (ref "CR9")
      (value "SMBJ48A")
      (footprint "Buck:SMB (DO-214AA)")
      (libsource (lib "MYLIB") (part "DiodeSMD4.5mm"))
    )
    (comp (ref "CR10")
      (value "SMBJ48A")
      (footprint "Buck:SMB (DO-214AA)")
      (libsource (lib "MYLIB") (part "DiodeSMD4.5mm"))
    )
    (comp (ref "CR11")
      (value "SMBJ48A")
      (footprint "Buck:SMB (DO-214AA)")
      (libsource (lib "MYLIB") (part "DiodeSMD4.5mm"))
    )
    (comp (ref "CR12")
      (value "SMBJ48A")
      (footprint "Buck:SMB (DO-214AA)")
      (libsource (lib "MYLIB") (part "DiodeSMD4.5mm"))
    )
    (comp (ref "CR13")
      (value "SMBJ48A")
      (footprint "Buck:SMB (DO-214AA)")
      (libsource (lib "MYLIB") (part "DiodeSMD4.5mm"))
    )
    (comp (ref "CR14")
      (value "SMBJ48A")
      (footprint "Buck:SMB (DO-214AA)")
      (libsource (lib "MYLIB") (part "DiodeSMD4.5mm"))
    )
    (comp (ref "CR15")
      (value "SMBJ48A")
      (footprint "Buck:SMB (DO-214AA)")
      (libsource (lib "MYLIB") (part "DiodeSMD4.5mm"))
    )
    (comp (ref "CR16")
      (value "SMBJ48A")
      (footprint "Buck:SMB (DO-214AA)")
      (libsource (lib "MYLIB") (part "DiodeSMD4.5mm"))
    )
    (comp (ref "CR17")
      (value "RFN10BM6STL")
      (footprint "Buck:RFN10BM")
      (libsource (lib "MYLIB") (part "DiodeSMD4.5mm"))
    )
    (comp (ref "CR18")
      (value "RFN10BM6STL")
      (footprint "Buck:RFN10BM")
      (libsource (lib "MYLIB") (part "DiodeSMD4.5mm"))
    )
    (comp (ref "D1")
      (value "KDZVTR39A")
      (footprint "Buck:SOD-123FL")
      (description "Zener Diode")
      (fields (field (name "PUBLISHER") "Altium Limited"))
      (libsource (lib "Miscellaneous Devices") (part "D Zener"))
    )
    (comp (ref "D2")
      (value "VSS8D5M12HM3/H")
      (footprint "Buck:DO-221AD")
      (description "Schottky Diode")
      (fields (field (name "PUBLISHER") "Altium Limited"))
      (libsource (lib "Miscellaneous Devices") (part "D Schottky"))
    )
    (comp (ref "D3")
      (value "1N4007-SMD")
      (footprint "Buck:SMA (DO-214AC)")
      (description "Diode Standard 1000V 1A Through Hole DO-204AL _DO-41_")
      (fields (field (name "MF") "ON Semiconductor") (field (name "MP") "1N4007"))
      (libsource (lib "Buck") (part "1N4007"))
    )
    (comp (ref "D4")
      (value "1N4007-SMD")
      (footprint "Buck:SMA (DO-214AC)")
      (description "Diode Standard 1000V 1A Through Hole DO-204AL _DO-41_")
      (fields (field (name "MF") "ON Semiconductor") (field (name "MP") "1N4007"))
      (libsource (lib "Buck") (part "1N4007"))
    )
    (comp (ref "D5")
      (value "1N4007-SMD")
      (footprint "Buck:SMA (DO-214AC)")
      (description "Diode Standard 1000V 1A Through Hole DO-204AL _DO-41_")
      (fields (field (name "MF") "ON Semiconductor") (field (name "MP") "1N4007"))
      (libsource (lib "Buck") (part "1N4007"))
    )
    (comp (ref "D6")
      (value "1N4007-SMD")
      (footprint "Buck:SMA (DO-214AC)")
      (description "Diode Standard 1000V 1A Through Hole DO-204AL _DO-41_")
      (fields (field (name "MF") "ON Semiconductor") (field (name "MP") "1N4007"))
      (libsource (lib "Buck") (part "1N4007"))
    )
    (comp (ref "D7")
      (value "KDZVTR39A")
      (footprint "Buck:SOD-123FL")
      (description "Zener Diode")
      (fields (field (name "PUBLISHER") "Altium Limited"))
      (libsource (lib "Miscellaneous Devices") (part "D Zener"))
    )
    (comp (ref "D8")
      (value "1N4007-SMD")
      (footprint "Buck:SMA (DO-214AC)")
      (description "Diode Standard 1000V 1A Through Hole DO-204AL _DO-41_")
      (fields (field (name "MF") "ON Semiconductor") (field (name "MP") "1N4007"))
      (libsource (lib "Buck") (part "1N4007"))
    )
    (comp (ref "D9")
      (value "KDZVTR39A")
      (footprint "Buck:SOD-123FL")
      (description "Zener Diode")
      (fields (field (name "PUBLISHER") "Altium Limited"))
      (libsource (lib "Miscellaneous Devices") (part "D Zener"))
    )
    (comp (ref "D10")
      (value "1N4007-SMD")
      (footprint "Buck:SMA (DO-214AC)")
      (description "Diode Standard 1000V 1A Through Hole DO-204AL _DO-41_")
      (fields (field (name "MF") "ON Semiconductor") (field (name "MP") "1N4007"))
      (libsource (lib "Buck") (part "1N4007"))
    )
    (comp (ref "D11")
      (value "1N4007-SMD")
      (footprint "Buck:SMA (DO-214AC)")
      (description "Diode Standard 1000V 1A Through Hole DO-204AL _DO-41_")
      (fields (field (name "MF") "ON Semiconductor") (field (name "MP") "1N4007"))
      (libsource (lib "Buck") (part "1N4007"))
    )
    (comp (ref "D12")
      (value "1N4007-SMD")
      (footprint "Buck:SMA (DO-214AC)")
      (description "Diode Standard 1000V 1A Through Hole DO-204AL _DO-41_")
      (fields (field (name "MF") "ON Semiconductor") (field (name "MP") "1N4007"))
      (libsource (lib "Buck") (part "1N4007"))
    )
    (comp (ref "D13")
      (value "1N4007-SMD")
      (footprint "Buck:SMA (DO-214AC)")
      (description "Diode Standard 1000V 1A Through Hole DO-204AL _DO-41_")
      (fields (field (name "MF") "ON Semiconductor") (field (name "MP") "1N4007"))
      (libsource (lib "Buck") (part "1N4007"))
    )
    (comp (ref "D14")
      (value "1N4007-SMD")
      (footprint "Buck:SMA (DO-214AC)")
      (description "Diode Standard 1000V 1A Through Hole DO-204AL _DO-41_")
      (fields (field (name "MF") "ON Semiconductor") (field (name "MP") "1N4007"))
      (libsource (lib "Buck") (part "1N4007"))
    )
    (comp (ref "D15")
      (value "1N4007-SMD")
      (footprint "Buck:SMA (DO-214AC)")
      (description "Diode Standard 1000V 1A Through Hole DO-204AL _DO-41_")
      (fields (field (name "MF") "ON Semiconductor") (field (name "MP") "1N4007"))
      (libsource (lib "Buck") (part "1N4007"))
    )
    (comp (ref "D16")
      (value "1N4007-SMD")
      (footprint "Buck:SMA (DO-214AC)")
      (description "Diode Standard 1000V 1A Through Hole DO-204AL _DO-41_")
      (fields (field (name "MF") "ON Semiconductor") (field (name "MP") "1N4007"))
      (libsource (lib "Buck") (part "1N4007"))
    )
    (comp (ref "D17")
      (value "KDZVTR39A")
      (footprint "Buck:SOD-123FL")
      (description "Zener Diode")
      (fields (field (name "PUBLISHER") "Altium Limited"))
      (libsource (lib "Miscellaneous Devices") (part "D Zener"))
    )
    (comp (ref "D18")
      (value "KDZVTR39A")
      (footprint "Buck:SOD-123FL")
      (description "Zener Diode")
      (fields (field (name "PUBLISHER") "Altium Limited"))
      (libsource (lib "Miscellaneous Devices") (part "D Zener"))
    )
    (comp (ref "D19")
      (value "1N4007-SMD")
      (footprint "Buck:SMA (DO-214AC)")
      (description "Diode Standard 1000V 1A Through Hole DO-204AL _DO-41_")
      (fields (field (name "MF") "ON Semiconductor") (field (name "MP") "1N4007"))
      (libsource (lib "Buck") (part "1N4007"))
    )
    (comp (ref "D20")
      (value "1N4007-SMD")
      (footprint "Buck:SMA (DO-214AC)")
      (description "Diode Standard 1000V 1A Through Hole DO-204AL _DO-41_")
      (fields (field (name "MF") "ON Semiconductor") (field (name "MP") "1N4007"))
      (libsource (lib "Buck") (part "1N4007"))
    )
    (comp (ref "D21")
      (value "1N4007-SMD")
      (footprint "Buck:SMA (DO-214AC)")
      (description "Diode Standard 1000V 1A Through Hole DO-204AL _DO-41_")
      (fields (field (name "MF") "ON Semiconductor") (field (name "MP") "1N4007"))
      (libsource (lib "Buck") (part "1N4007"))
    )
    (comp (ref "D22")
      (value "1N4007-SMD")
      (footprint "Buck:SMA (DO-214AC)")
      (description "Diode Standard 1000V 1A Through Hole DO-204AL _DO-41_")
      (fields (field (name "MF") "ON Semiconductor") (field (name "MP") "1N4007"))
      (libsource (lib "Buck") (part "1N4007"))
    )
    (comp (ref "DS1") (value "LED SMD") (footprint "Buck:LED0805") (libsource (lib "MYLIB") (part "LED SMD")))
    (comp (ref "DS2")
      (value "LED SMD")
      (footprint "Buck:LED0805")
      (description "Blue SURFACE MOUNT LED LAMP, -40 to +85 ,0805 SIZE")
      (fields (field (name "PART NUMBER") "QTLP630C-7"))
      (libsource (lib "kashizadeh_ali") (part "LED"))
    )
    (comp (ref "DS3")
      (value "LED SMD")
      (footprint "Buck:LED0805")
      (description "Blue SURFACE MOUNT LED LAMP, -40 to +85 ,0805 SIZE")
      (fields (field (name "PART NUMBER") "QTLP630C-7"))
      (libsource (lib "kashizadeh_ali") (part "LED"))
    )
    (comp (ref "DS4")
      (value "LED SMD")
      (footprint "Buck:LED0805")
      (description "Blue SURFACE MOUNT LED LAMP, -40 to +85 ,0805 SIZE")
      (fields (field (name "PART NUMBER") "QTLP630C-7"))
      (libsource (lib "kashizadeh_ali") (part "LED"))
    )
    (comp (ref "DS5")
      (value "LED SMD")
      (footprint "Buck:LED0805")
      (description "Blue SURFACE MOUNT LED LAMP, -40 to +85 ,0805 SIZE")
      (fields (field (name "PART NUMBER") "QTLP630C-7"))
      (libsource (lib "kashizadeh_ali") (part "LED"))
    )
    (comp (ref "DS6") (value "LED SMD") (footprint "Buck:LED0805") (libsource (lib "MYLIB") (part "LED SMD")))
    (comp (ref "DS7") (value "LED SMD") (footprint "Buck:LED0805") (libsource (lib "MYLIB") (part "LED SMD")))
    (comp (ref "DS8") (value "LED SMD") (footprint "Buck:LED0805") (libsource (lib "MYLIB") (part "LED SMD")))
    (comp (ref "DS9")
      (value "LED SMD")
      (footprint "Buck:LED0805")
      (description "Blue SURFACE MOUNT LED LAMP, -40 to +85 ,0805 SIZE")
      (fields (field (name "PART NUMBER") "QTLP630C-7"))
      (libsource (lib "kashizadeh_ali") (part "LED"))
    )
    (comp (ref "DS10") (value "LED") (footprint "Buck:LED0805") (libsource (lib "SCH") (part "LED")))
    (comp (ref "DS11")
      (value "LED SMD")
      (footprint "Buck:LED0805")
      (libsource (lib "MYLIB") (part "LED SMD"))
    )
    (comp (ref "DS12")
      (value "LED SMD")
      (footprint "Buck:LED0805")
      (description "Blue SURFACE MOUNT LED LAMP, -40 to +85 ,0805 SIZE")
      (fields (field (name "PART NUMBER") "QTLP630C-7"))
      (libsource (lib "kashizadeh_ali") (part "LED"))
    )
    (comp (ref "DS13")
      (value "LED SMD")
      (footprint "Buck:LED0805")
      (libsource (lib "MYLIB") (part "LED SMD"))
    )
    (comp (ref "F1")
      (value "0031.8001 Fuse holder")
      (footprint "Buck:00318001")
      (description "Fuse")
      (fields (field (name "PUBLISHER") "Altium Limited"))
      (libsource (lib "Miscellaneous Devices") (part "Fuse 1"))
    )
    (comp (ref "F2")
      (value "0031.8001 Fuse holder")
      (footprint "Buck:00318001")
      (description "Fuse")
      (fields (field (name "PUBLISHER") "Altium Limited"))
      (libsource (lib "Miscellaneous Devices") (part "Fuse 1"))
    )
    (comp (ref "F3")
      (value "0031.8001 Fuse holder")
      (footprint "Buck:00318001")
      (description "Fuse")
      (fields (field (name "PUBLISHER") "Altium Limited"))
      (libsource (lib "Miscellaneous Devices") (part "Fuse 1"))
    )
    (comp (ref "F4")
      (value "0031.8001 Fuse holder")
      (footprint "Buck:00318001")
      (description "Fuse")
      (fields (field (name "PUBLISHER") "Altium Limited"))
      (libsource (lib "Miscellaneous Devices") (part "Fuse 1"))
    )
    (comp (ref "FB1")
      (value "FERRITE CHIP")
      (footprint "Buck:L0805")
      (libsource (lib "No_avaran") (part "FERRITE CHIP"))
    )
    (comp (ref "FB2")
      (value "FBMJ2125HS420-T")
      (footprint "Buck:L0805")
      (libsource (lib "No_avaran") (part "FERRITE CHIP"))
    )
    (comp (ref "FB3")
      (value "FERRITE CHIP")
      (footprint "Buck:L0805")
      (libsource (lib "No_avaran") (part "FERRITE CHIP"))
    )
    (comp (ref "FB4")
      (value "FERRITE CHIP")
      (footprint "Buck:L0805")
      (libsource (lib "No_avaran") (part "FERRITE CHIP"))
    )
    (comp (ref "FB5")
      (value "FERRITE CHIP")
      (footprint "Buck:L0805")
      (libsource (lib "No_avaran") (part "FERRITE CHIP"))
    )
    (comp (ref "FB6")
      (value "FERRITE CHIP")
      (footprint "Buck:L0805")
      (libsource (lib "No_avaran") (part "FERRITE CHIP"))
    )
    (comp (ref "FB7")
      (value "FERRITE CHIP")
      (footprint "Buck:L0805")
      (libsource (lib "No_avaran") (part "FERRITE CHIP"))
    )
    (comp (ref "FB8")
      (value "FERRITE CHIP")
      (footprint "Buck:L0805")
      (libsource (lib "No_avaran") (part "FERRITE CHIP"))
    )
    (comp (ref "FB9")
      (value "FERRITE CHIP")
      (footprint "Buck:L0805")
      (libsource (lib "No_avaran") (part "FERRITE CHIP"))
    )
    (comp (ref "FB10")
      (value "FERRITE CHIP")
      (footprint "Buck:L0805")
      (libsource (lib "No_avaran") (part "FERRITE CHIP"))
    )
    (comp (ref "FB11")
      (value "FERRITE CHIP")
      (footprint "Buck:L0805")
      (libsource (lib "No_avaran") (part "FERRITE CHIP"))
    )
    (comp (ref "FB12")
      (value "FBMJ2125HS420-T")
      (footprint "Buck:L0805")
      (libsource (lib "No_avaran") (part "FERRITE CHIP"))
    )
    (comp (ref "FB13")
      (value "FBMJ2125HS420-T")
      (footprint "Buck:L0805")
      (libsource (lib "No_avaran") (part "FERRITE CHIP"))
    )
    (comp (ref "HS1")
      (value "Full bridge Heatsink")
      (footprint "Buck:Full_bridge_Heatsink")
      (libsource (lib "Full bridge-V1.00") (part "Full_bridge_Heatsink"))
    )
    (comp (ref "HS2")
      (value "Full bridge Heatsink")
      (footprint "Buck:Full_bridge_Heatsink")
      (libsource (lib "Full bridge-V1.00") (part "Full_bridge_Heatsink"))
    )
    (comp (ref "J1")
      (value "691101710002")
      (footprint "Buck:691101710002")
      (description "WR-TBL Series 101 Horizontal Entry Modular, THT, pitch 5mm, 2p")
      (fields (field (name "MANUFACTURER") "Wurth Elektronik"))
      (libsource (lib "Altium_WR-TBL (rev22b)") (part "691101710002"))
    )
    (comp (ref "J2")
      (value "61802529221")
      (footprint "Buck:61802525123")
      (description "Male PCB Connector with Hex Screw WR-DSUB, Vertical, 25 pins")
      (fields (field (name "MANUFACTURER") "Wurth Elektronik") (field (name "PUBLISHER") "WurthElektronik"))
      (libsource (lib "Miscellaneous Connectors") (part "WE-CN-2S-2M-D25"))
    )
    (comp (ref "L1")
      (value "Inductor")
      (footprint "Buck:FullBridge_Inductor")
      (fields (field (name "ALTIUM_VALUE") "EPCOS ETD39 N87") (field (name "PUBLISHER") "Altium Limited"))
      (libsource (lib "Miscellaneous Devices") (part "Inductor"))
    )
    (comp (ref "P1")
      (value "280371-2")
      (footprint "Buck:TECO-280371-2_V")
      (fields (field (name "MANUFACTURER") "TE Connectivity"))
      (libsource (lib "Miscellaneous Devices") (part "CN-1P-M-R4"))
    )
    (comp (ref "P2")
      (value "691311400104")
      (footprint "Buck:691311400104")
      (description "Serie 3114 - 7.62mm Close Vertical PCB Header WR-TBL, 4 pin")
      (fields (field (name "MANUFACTURER") "Wurth Elektronik") (field (name "PUBLISHER") "WurthElektronik"))
      (libsource (lib "Miscellaneous Connectors") (part "WE-CN-1P-M-R4"))
    )
    (comp (ref "P3")
      (value "691311400104")
      (footprint "Buck:691311400104")
      (description "Serie 3114 - 7.62mm Close Vertical PCB Header WR-TBL, 4 pin")
      (fields (field (name "MANUFACTURER") "Wurth Elektronik") (field (name "PUBLISHER") "WurthElektronik"))
      (libsource (lib "") (part "WE-CN-1P-M-R4_1"))
    )
    (comp (ref "PS1")
      (value "REC5-2415SRWZ/H6/A")
      (footprint "Buck:REC52415SRWZH6A")
      (description "DC/DC-Converter, 2kV, 4kVDC & 6kVDC Isolation. Continuous Short Circuit Protection")
      (libsource (lib "REC5-2415SRWZ_H6_A") (part "REC5-2415SRWZ/H6/A"))
    )
    (comp (ref "PS2")
      (value "REC5-2415SRWZ/H6/A")
      (footprint "Buck:REC52415SRWZH6A")
      (description "DC/DC-Converter, 2kV, 4kVDC & 6kVDC Isolation. Continuous Short Circuit Protection")
      (libsource (lib "REC5-2415SRWZ_H6_A") (part "REC5-2415SRWZ/H6/A"))
    )
    (comp (ref "PS3")
      (value "REC5-2415SRWZ/H6/A")
      (footprint "Buck:REC52415SRWZH6A")
      (description "DC/DC-Converter, 2kV, 4kVDC & 6kVDC Isolation. Continuous Short Circuit Protection")
      (libsource (lib "REC5-2415SRWZ_H6_A") (part "REC5-2415SRWZ/H6/A"))
    )
    (comp (ref "PS4")
      (value "REC5-2415SRWZ/H6/A")
      (footprint "Buck:REC52415SRWZH6A")
      (description "DC/DC-Converter, 2kV, 4kVDC & 6kVDC Isolation. Continuous Short Circuit Protection")
      (libsource (lib "REC5-2415SRWZ_H6_A") (part "REC5-2415SRWZ/H6/A"))
    )
    (comp (ref "Q1")
      (value "IKW25N120CS7")
      (footprint "Buck:PG-TO247-3")
      (fields (field (name "MANUFACTURER") "Infineon") (field (name "PARTNUMBER") "IKW40N120H3"))
      (libsource (lib "Miscellaneous Devices") (part "INF-IXXXXXXX-PG-TO220_247-3_1"))
    )
    (comp (ref "Q2")
      (value "IKW25N120CS7")
      (footprint "Buck:PG-TO247-3")
      (fields (field (name "MANUFACTURER") "Infineon") (field (name "PARTNUMBER") "IKW40N120H3"))
      (libsource (lib "Miscellaneous Devices") (part "INF-IXXXXXXX-PG-TO220_247-3_1"))
    )
    (comp (ref "Q3")
      (value "IKW25N120CS7")
      (footprint "Buck:PG-TO247-3")
      (fields (field (name "MANUFACTURER") "Infineon") (field (name "PARTNUMBER") "IKW40N120H3"))
      (libsource (lib "Miscellaneous Devices") (part "INF-IXXXXXXX-PG-TO220_247-3_1"))
    )
    (comp (ref "Q4")
      (value "IKW25N120CS7")
      (footprint "Buck:PG-TO247-3")
      (fields (field (name "MANUFACTURER") "Infineon") (field (name "PARTNUMBER") "IKW40N120H3"))
      (libsource (lib "Miscellaneous Devices") (part "INF-IXXXXXXX-PG-TO220_247-3_1"))
    )
    (comp (ref "Q5")
      (value "ACPL-C87A-500E")
      (footprint "Buck:FP-SSO-8-MFG")
      (description "IC OPAMP ISOLATION 100KHZ 8SO")
      (libsource (lib "Miscellaneous Devices") (part "b42ed144594ce334135a4fb1ded0a30"))
    )
    (comp (ref "R1") (value "15K") (footprint "Buck:R0805") (libsource (lib "MYLIB") (part "ResSMD")))
    (comp (ref "R2") (value "ResSMD") (footprint "Buck:R0805") (libsource (lib "MYLIB") (part "ResSMD")))
    (comp (ref "R3")
      (value "Res3")
      (footprint "Buck:R0603")
      (description "Resistor")
      (fields (field (name "ALTIUM_VALUE") "0") (field (name "PUBLISHER") "Altium Limited"))
      (libsource (lib "Miscellaneous Devices") (part "Res3"))
    )
    (comp (ref "R4")
      (value "Res3")
      (footprint "Buck:R0603")
      (description "Resistor")
      (fields (field (name "ALTIUM_VALUE") "0") (field (name "PUBLISHER") "Altium Limited"))
      (libsource (lib "Miscellaneous Devices") (part "Res3"))
    )
    (comp (ref "R5") (value "300") (footprint "Buck:R0805") (libsource (lib "MYLIB") (part "ResSMD")))
    (comp (ref "R6")
      (value "Res3")
      (footprint "Buck:R0603")
      (description "Resistor")
      (fields (field (name "ALTIUM_VALUE") "0") (field (name "PUBLISHER") "Altium Limited"))
      (libsource (lib "Miscellaneous Devices") (part "Res3"))
    )
    (comp (ref "R7")
      (value "12")
      (footprint "Buck:MELF 0204")
      (description "Semiconductor Resistor")
      (fields (field (name "ALTIUM_VALUE") "CMA02040X1209GB300") (field (name "PUBLISHER") "Altium Limited"))
      (libsource (lib "Miscellaneous Devices") (part "Res Semi"))
    )
    (comp (ref "R8")
      (value "Res3")
      (footprint "Buck:R0603")
      (description "Resistor")
      (fields (field (name "ALTIUM_VALUE") "0") (field (name "PUBLISHER") "Altium Limited"))
      (libsource (lib "Miscellaneous Devices") (part "Res3"))
    )
    (comp (ref "R9")
      (value "12")
      (footprint "Buck:MELF 0204")
      (description "Semiconductor Resistor")
      (fields (field (name "ALTIUM_VALUE") "CMA02040X1209GB300") (field (name "PUBLISHER") "Altium Limited"))
      (libsource (lib "Miscellaneous Devices") (part "Res Semi"))
    )
    (comp (ref "R10") (value "1K") (footprint "Buck:R0805") (libsource (lib "MYLIB") (part "ResSMD")))
    (comp (ref "R11") (value "ResSMD") (footprint "Buck:R0805") (libsource (lib "MYLIB") (part "ResSMD")))
    (comp (ref "R12")
      (value "Res3")
      (footprint "Buck:R0603")
      (description "Resistor")
      (fields (field (name "ALTIUM_VALUE") "0") (field (name "PUBLISHER") "Altium Limited"))
      (libsource (lib "Miscellaneous Devices") (part "Res3"))
    )
    (comp (ref "R13")
      (value "CMA02040X1209GB300")
      (footprint "Buck:MMF50S")
      (description "Resistor")
      (fields (field (name "ALTIUM_VALUE") "1") (field (name "PUBLISHER") "Altium Limited"))
      (libsource (lib "Miscellaneous Devices") (part "Res1"))
    )
    (comp (ref "R14") (value "ResSMD") (footprint "Buck:R0805") (libsource (lib "MYLIB") (part "ResSMD")))
    (comp (ref "R15") (value "ResSMD") (footprint "Buck:R0805") (libsource (lib "MYLIB") (part "ResSMD")))
    (comp (ref "R16")
      (value "Res3")
      (footprint "Buck:R0603")
      (description "Resistor")
      (fields (field (name "ALTIUM_VALUE") "0") (field (name "PUBLISHER") "Altium Limited"))
      (libsource (lib "Miscellaneous Devices") (part "Res3"))
    )
    (comp (ref "R17") (value "0") (footprint "Buck:R0805") (libsource (lib "MYLIB") (part "ResSMD")))
    (comp (ref "R18")
      (value "Res1")
      (footprint "Buck:R0805")
      (description "Resistor")
      (fields (field (name "ALTIUM_VALUE") "1") (field (name "PUBLISHER") "Altium Limited"))
      (libsource (lib "Miscellaneous Devices") (part "Res1"))
    )
    (comp (ref "R19")
      (value "CMA02040X1209GB300")
      (footprint "Buck:MELF 0204")
      (description "Resistor")
      (fields (field (name "PUBLISHER") "Altium Limited"))
      (libsource (lib "Miscellaneous Devices") (part "Res1"))
    )
    (comp (ref "R20")
      (value "Res3")
      (footprint "Buck:R0603")
      (description "Resistor")
      (fields (field (name "ALTIUM_VALUE") "0") (field (name "PUBLISHER") "Altium Limited"))
      (libsource (lib "Miscellaneous Devices") (part "Res3"))
    )
    (comp (ref "R21")
      (value "Res3")
      (footprint "Buck:R0603")
      (description "Resistor")
      (fields (field (name "ALTIUM_VALUE") "0") (field (name "PUBLISHER") "Altium Limited"))
      (libsource (lib "Miscellaneous Devices") (part "Res3"))
    )
    (comp (ref "R22")
      (value "CMA02040X1209GB300")
      (footprint "Buck:MMF50S")
      (description "Resistor")
      (fields (field (name "ALTIUM_VALUE") "1") (field (name "PUBLISHER") "Altium Limited"))
      (libsource (lib "Miscellaneous Devices") (part "Res1"))
    )
    (comp (ref "R23") (value "5K") (footprint "Buck:R0805") (libsource (lib "MYLIB") (part "ResSMD")))
    (comp (ref "R24") (value "ResSMD") (footprint "Buck:R0805") (libsource (lib "MYLIB") (part "ResSMD")))
    (comp (ref "R25")
      (value "Res3")
      (footprint "Buck:R0603")
      (description "Resistor")
      (fields (field (name "ALTIUM_VALUE") "10K") (field (name "PUBLISHER") "Altium Limited"))
      (libsource (lib "Miscellaneous Devices") (part "Res3"))
    )
    (comp (ref "R26") (value "5K") (footprint "Buck:R0805") (libsource (lib "MYLIB") (part "ResSMD")))
    (comp (ref "R27") (value "5K") (footprint "Buck:R0805") (libsource (lib "MYLIB") (part "ResSMD")))
    (comp (ref "R28") (value "1K") (footprint "Buck:R0805") (libsource (lib "MYLIB") (part "ResSMD")))
    (comp (ref "R29")
      (value "Res3")
      (footprint "Buck:R0603")
      (description "Resistor")
      (fields (field (name "ALTIUM_VALUE") "10K") (field (name "PUBLISHER") "Altium Limited"))
      (libsource (lib "Miscellaneous Devices") (part "Res3"))
    )
    (comp (ref "R30")
      (value "47k")
      (footprint "Buck:R0805")
      (description "Resistor")
      (fields (field (name "ALTIUM_VALUE") "47k") (field (name "PUBLISHER") "Altium Limited"))
      (libsource (lib "Miscellaneous Devices") (part "Res1"))
    )
    (comp (ref "R31")
      (value "15")
      (footprint "Buck:AXIAL-0.5")
      (description "Semiconductor Resistor")
      (fields (field (name "ALTIUM_VALUE") "0.5W") (field (name "PUBLISHER") "Altium Limited"))
      (libsource (lib "Miscellaneous Devices") (part "Res Semi"))
    )
    (comp (ref "R32")
      (value "15")
      (footprint "Buck:AXIAL-0.5")
      (description "Semiconductor Resistor")
      (fields (field (name "ALTIUM_VALUE") "0.5W") (field (name "PUBLISHER") "Altium Limited"))
      (libsource (lib "Miscellaneous Devices") (part "Res Semi"))
    )
    (comp (ref "R33") (value "100") (footprint "Buck:R0805") (libsource (lib "MYLIB") (part "ResSMD")))
    (comp (ref "R34") (value "100") (footprint "Buck:R0805") (libsource (lib "MYLIB") (part "ResSMD")))
    (comp (ref "R35")
      (value "CMA02040X1209GB300")
      (footprint "Buck:MMF50S")
      (description "Resistor")
      (fields (field (name "ALTIUM_VALUE") "???") (field (name "PUBLISHER") "Altium Limited"))
      (libsource (lib "Miscellaneous Devices") (part "Res1"))
    )
    (comp (ref "R36")
      (value "CMA02040X1209GB300")
      (footprint "Buck:MMF50S")
      (description "Resistor")
      (fields (field (name "ALTIUM_VALUE") "???") (field (name "PUBLISHER") "Altium Limited"))
      (libsource (lib "Miscellaneous Devices") (part "Res1"))
    )
    (comp (ref "R37")
      (value "12")
      (footprint "Buck:MELF 0204")
      (description "Semiconductor Resistor")
      (fields (field (name "ALTIUM_VALUE") "CMA02040X1209GB300") (field (name "PUBLISHER") "Altium Limited"))
      (libsource (lib "Miscellaneous Devices") (part "Res Semi"))
    )
    (comp (ref "R38")
      (value "100k")
      (footprint "Buck:AXIAL0.9-VR68")
      (description "Semiconductor Resistor")
      (fields (field (name "ALTIUM_VALUE") "0.5W") (field (name "PUBLISHER") "Altium Limited"))
      (libsource (lib "Miscellaneous Devices") (part "Res Semi"))
    )
    (comp (ref "R39")
      (value "100k")
      (footprint "Buck:AXIAL0.9-VR68")
      (description "Semiconductor Resistor")
      (fields (field (name "ALTIUM_VALUE") "0.5W") (field (name "PUBLISHER") "Altium Limited"))
      (libsource (lib "Miscellaneous Devices") (part "Res Semi"))
    )
    (comp (ref "R40")
      (value "Res3")
      (footprint "Buck:R0603")
      (description "Resistor")
      (fields (field (name "ALTIUM_VALUE") "0") (field (name "PUBLISHER") "Altium Limited"))
      (libsource (lib "Miscellaneous Devices") (part "Res3"))
    )
    (comp (ref "R41")
      (value "12")
      (footprint "Buck:MELF 0204")
      (description "Semiconductor Resistor")
      (fields (field (name "ALTIUM_VALUE") "CMA02040X1209GB300") (field (name "PUBLISHER") "Altium Limited"))
      (libsource (lib "Miscellaneous Devices") (part "Res Semi"))
    )
    (comp (ref "R42")
      (value "100k")
      (footprint "Buck:AXIAL0.9-VR68")
      (description "Semiconductor Resistor")
      (fields (field (name "ALTIUM_VALUE") "0.5W") (field (name "PUBLISHER") "Altium Limited"))
      (libsource (lib "Miscellaneous Devices") (part "Res Semi"))
    )
    (comp (ref "R43")
      (value "100k")
      (footprint "Buck:AXIAL0.9-VR68")
      (description "Semiconductor Resistor")
      (fields (field (name "ALTIUM_VALUE") "0.5W") (field (name "PUBLISHER") "Altium Limited"))
      (libsource (lib "Miscellaneous Devices") (part "Res Semi"))
    )
    (comp (ref "R44") (value "ResSMD") (footprint "Buck:R0805") (libsource (lib "MYLIB") (part "ResSMD")))
    (comp (ref "R45")
      (value "Res3")
      (footprint "Buck:R0603")
      (description "Resistor")
      (fields (field (name "ALTIUM_VALUE") "0") (field (name "PUBLISHER") "Altium Limited"))
      (libsource (lib "Miscellaneous Devices") (part "Res3"))
    )
    (comp (ref "R46")
      (value "CMA02040X1209GB300")
      (footprint "Buck:MMF50S")
      (description "Resistor")
      (fields (field (name "ALTIUM_VALUE") "1") (field (name "PUBLISHER") "Altium Limited"))
      (libsource (lib "Miscellaneous Devices") (part "Res1"))
    )
    (comp (ref "R47")
      (value "Res3")
      (footprint "Buck:R0603")
      (description "Resistor")
      (fields (field (name "ALTIUM_VALUE") "0") (field (name "PUBLISHER") "Altium Limited"))
      (libsource (lib "Miscellaneous Devices") (part "Res3"))
    )
    (comp (ref "R48") (value "0") (footprint "Buck:R0805") (libsource (lib "MYLIB") (part "ResSMD")))
    (comp (ref "R49")
      (value "Res1")
      (footprint "Buck:R0805")
      (description "Resistor")
      (fields (field (name "ALTIUM_VALUE") "1") (field (name "PUBLISHER") "Altium Limited"))
      (libsource (lib "Miscellaneous Devices") (part "Res1"))
    )
    (comp (ref "R50")
      (value "CMA02040X1209GB300")
      (footprint "Buck:MELF 0204")
      (description "Resistor")
      (fields (field (name "PUBLISHER") "Altium Limited"))
      (libsource (lib "Miscellaneous Devices") (part "Res1"))
    )
    (comp (ref "R51")
      (value "Res3")
      (footprint "Buck:R0603")
      (description "Resistor")
      (fields (field (name "ALTIUM_VALUE") "0") (field (name "PUBLISHER") "Altium Limited"))
      (libsource (lib "Miscellaneous Devices") (part "Res3"))
    )
    (comp (ref "R52")
      (value "15")
      (footprint "Buck:AXIAL-0.5")
      (description "Semiconductor Resistor")
      (fields (field (name "ALTIUM_VALUE") "0.5W") (field (name "PUBLISHER") "Altium Limited"))
      (libsource (lib "Miscellaneous Devices") (part "Res Semi"))
    )
    (comp (ref "R53")
      (value "Res3")
      (footprint "Buck:R0603")
      (description "Resistor")
      (fields (field (name "ALTIUM_VALUE") "0") (field (name "PUBLISHER") "Altium Limited"))
      (libsource (lib "Miscellaneous Devices") (part "Res3"))
    )
    (comp (ref "R54")
      (value "15")
      (footprint "Buck:AXIAL-0.5")
      (description "Semiconductor Resistor")
      (fields (field (name "ALTIUM_VALUE") "0.5W") (field (name "PUBLISHER") "Altium Limited"))
      (libsource (lib "Miscellaneous Devices") (part "Res Semi"))
    )
    (comp (ref "R55")
      (value "CMA02040X1209GB300")
      (footprint "Buck:MMF50S")
      (description "Resistor")
      (fields (field (name "ALTIUM_VALUE") "1") (field (name "PUBLISHER") "Altium Limited"))
      (libsource (lib "Miscellaneous Devices") (part "Res1"))
    )
    (comp (ref "R56") (value "5K") (footprint "Buck:R0805") (libsource (lib "MYLIB") (part "ResSMD")))
    (comp (ref "R57") (value "100") (footprint "Buck:R0805") (libsource (lib "MYLIB") (part "ResSMD")))
    (comp (ref "R58") (value "100") (footprint "Buck:R0805") (libsource (lib "MYLIB") (part "ResSMD")))
    (comp (ref "R59")
      (value "Res3")
      (footprint "Buck:R0603")
      (description "Resistor")
      (fields (field (name "ALTIUM_VALUE") "10K") (field (name "PUBLISHER") "Altium Limited"))
      (libsource (lib "Miscellaneous Devices") (part "Res3"))
    )
    (comp (ref "R60") (value "5K") (footprint "Buck:R0805") (libsource (lib "MYLIB") (part "ResSMD")))
    (comp (ref "R61") (value "5K") (footprint "Buck:R0805") (libsource (lib "MYLIB") (part "ResSMD")))
    (comp (ref "R62") (value "1K") (footprint "Buck:R0805") (libsource (lib "MYLIB") (part "ResSMD")))
    (comp (ref "R63")
      (value "Res3")
      (footprint "Buck:R0603")
      (description "Resistor")
      (fields (field (name "ALTIUM_VALUE") "10K") (field (name "PUBLISHER") "Altium Limited"))
      (libsource (lib "Miscellaneous Devices") (part "Res3"))
    )
    (comp (ref "R64")
      (value "47k")
      (footprint "Buck:R0805")
      (description "Resistor")
      (fields (field (name "ALTIUM_VALUE") "47k") (field (name "PUBLISHER") "Altium Limited"))
      (libsource (lib "Miscellaneous Devices") (part "Res1"))
    )
    (comp (ref "R65")
      (value "CMA02040X1209GB300")
      (footprint "Buck:MMF50S")
      (description "Resistor")
      (fields (field (name "ALTIUM_VALUE") "???") (field (name "PUBLISHER") "Altium Limited"))
      (libsource (lib "Miscellaneous Devices") (part "Res1"))
    )
    (comp (ref "R66")
      (value "CMA02040X1209GB300")
      (footprint "Buck:MMF50S")
      (description "Resistor")
      (fields (field (name "ALTIUM_VALUE") "???") (field (name "PUBLISHER") "Altium Limited"))
      (libsource (lib "Miscellaneous Devices") (part "Res1"))
    )
    (comp (ref "R67")
      (value "12")
      (footprint "Buck:MELF 0204")
      (description "Semiconductor Resistor")
      (fields (field (name "ALTIUM_VALUE") "CMA02040X1209GB300") (field (name "PUBLISHER") "Altium Limited"))
      (libsource (lib "Miscellaneous Devices") (part "Res Semi"))
    )
    (comp (ref "R68")
      (value "Res3")
      (footprint "Buck:R0603")
      (description "Resistor")
      (fields (field (name "ALTIUM_VALUE") "0") (field (name "PUBLISHER") "Altium Limited"))
      (libsource (lib "Miscellaneous Devices") (part "Res3"))
    )
    (comp (ref "R69")
      (value "12")
      (footprint "Buck:MELF 0204")
      (description "Semiconductor Resistor")
      (fields (field (name "ALTIUM_VALUE") "CMA02040X1209GB300") (field (name "PUBLISHER") "Altium Limited"))
      (libsource (lib "Miscellaneous Devices") (part "Res Semi"))
    )
    (comp (ref "R70") (value "ResSMD") (footprint "Buck:R0805") (libsource (lib "MYLIB") (part "ResSMD")))
    (comp (ref "R71")
      (value "Res3")
      (footprint "Buck:R0603")
      (description "Resistor")
      (fields (field (name "ALTIUM_VALUE") "0") (field (name "PUBLISHER") "Altium Limited"))
      (libsource (lib "Miscellaneous Devices") (part "Res3"))
    )
    (comp (ref "R72")
      (value "CMA02040X1209GB300")
      (footprint "Buck:MMF50S")
      (description "Resistor")
      (fields (field (name "ALTIUM_VALUE") "1") (field (name "PUBLISHER") "Altium Limited"))
      (libsource (lib "Miscellaneous Devices") (part "Res1"))
    )
    (comp (ref "R73")
      (value "Res3")
      (footprint "Buck:R0603")
      (description "Resistor")
      (fields (field (name "ALTIUM_VALUE") "0") (field (name "PUBLISHER") "Altium Limited"))
      (libsource (lib "Miscellaneous Devices") (part "Res3"))
    )
    (comp (ref "R74") (value "0") (footprint "Buck:R0805") (libsource (lib "MYLIB") (part "ResSMD")))
    (comp (ref "R75")
      (value "Res1")
      (footprint "Buck:R0805")
      (description "Resistor")
      (fields (field (name "ALTIUM_VALUE") "1") (field (name "PUBLISHER") "Altium Limited"))
      (libsource (lib "Miscellaneous Devices") (part "Res1"))
    )
    (comp (ref "R76")
      (value "CMA02040X1209GB300")
      (footprint "Buck:MELF 0204")
      (description "Resistor")
      (fields (field (name "PUBLISHER") "Altium Limited"))
      (libsource (lib "Miscellaneous Devices") (part "Res1"))
    )
    (comp (ref "R77")
      (value "Res3")
      (footprint "Buck:R0603")
      (description "Resistor")
      (fields (field (name "ALTIUM_VALUE") "0") (field (name "PUBLISHER") "Altium Limited"))
      (libsource (lib "Miscellaneous Devices") (part "Res3"))
    )
    (comp (ref "R78")
      (value "Res3")
      (footprint "Buck:R0603")
      (description "Resistor")
      (fields (field (name "ALTIUM_VALUE") "0") (field (name "PUBLISHER") "Altium Limited"))
      (libsource (lib "Miscellaneous Devices") (part "Res3"))
    )
    (comp (ref "R79")
      (value "CMA02040X1209GB300")
      (footprint "Buck:MMF50S")
      (description "Resistor")
      (fields (field (name "ALTIUM_VALUE") "1") (field (name "PUBLISHER") "Altium Limited"))
      (libsource (lib "Miscellaneous Devices") (part "Res1"))
    )
    (comp (ref "R80") (value "5K") (footprint "Buck:R0805") (libsource (lib "MYLIB") (part "ResSMD")))
    (comp (ref "R81")
      (value "Res3")
      (footprint "Buck:R0603")
      (description "Resistor")
      (fields (field (name "ALTIUM_VALUE") "10K") (field (name "PUBLISHER") "Altium Limited"))
      (libsource (lib "Miscellaneous Devices") (part "Res3"))
    )
    (comp (ref "R82") (value "5K") (footprint "Buck:R0805") (libsource (lib "MYLIB") (part "ResSMD")))
    (comp (ref "R83") (value "5K") (footprint "Buck:R0805") (libsource (lib "MYLIB") (part "ResSMD")))
    (comp (ref "R84") (value "1K") (footprint "Buck:R0805") (libsource (lib "MYLIB") (part "ResSMD")))
    (comp (ref "R85")
      (value "Res3")
      (footprint "Buck:R0603")
      (description "Resistor")
      (fields (field (name "ALTIUM_VALUE") "10K") (field (name "PUBLISHER") "Altium Limited"))
      (libsource (lib "Miscellaneous Devices") (part "Res3"))
    )
    (comp (ref "R86")
      (value "47k")
      (footprint "Buck:R0805")
      (description "Resistor")
      (fields (field (name "ALTIUM_VALUE") "47k") (field (name "PUBLISHER") "Altium Limited"))
      (libsource (lib "Miscellaneous Devices") (part "Res1"))
    )
    (comp (ref "R87") (value "15K") (footprint "Buck:R0805") (libsource (lib "MYLIB") (part "ResSMD")))
    (comp (ref "R88") (value "15K") (footprint "Buck:R0805") (libsource (lib "MYLIB") (part "ResSMD")))
    (comp (ref "R89")
      (value "12")
      (footprint "Buck:MELF 0204")
      (description "Semiconductor Resistor")
      (fields (field (name "ALTIUM_VALUE") "CMA02040X1209GB300") (field (name "PUBLISHER") "Altium Limited"))
      (libsource (lib "Miscellaneous Devices") (part "Res Semi"))
    )
    (comp (ref "R90")
      (value "Res3")
      (footprint "Buck:R0603")
      (description "Resistor")
      (fields (field (name "ALTIUM_VALUE") "0") (field (name "PUBLISHER") "Altium Limited"))
      (libsource (lib "Miscellaneous Devices") (part "Res3"))
    )
    (comp (ref "R91")
      (value "12")
      (footprint "Buck:MELF 0204")
      (description "Semiconductor Resistor")
      (fields (field (name "ALTIUM_VALUE") "CMA02040X1209GB300") (field (name "PUBLISHER") "Altium Limited"))
      (libsource (lib "Miscellaneous Devices") (part "Res Semi"))
    )
    (comp (ref "R92") (value "0 SMD") (footprint "Buck:R0805") (libsource (lib "MYLIB") (part "ResSMD")))
    (comp (ref "R93") (value "15K") (footprint "Buck:R0805") (libsource (lib "MYLIB") (part "ResSMD")))
    (comp (ref "R94") (value "15K") (footprint "Buck:R0805") (libsource (lib "MYLIB") (part "ResSMD")))
    (comp (ref "R95") (value "ResSMD") (footprint "Buck:R0805") (libsource (lib "MYLIB") (part "ResSMD")))
    (comp (ref "R96")
      (value "Res3")
      (footprint "Buck:R0603")
      (description "Resistor")
      (fields (field (name "ALTIUM_VALUE") "0") (field (name "PUBLISHER") "Altium Limited"))
      (libsource (lib "Miscellaneous Devices") (part "Res3"))
    )
    (comp (ref "R97")
      (value "CMA02040X1209GB300")
      (footprint "Buck:MMF50S")
      (description "Resistor")
      (fields (field (name "ALTIUM_VALUE") "1") (field (name "PUBLISHER") "Altium Limited"))
      (libsource (lib "Miscellaneous Devices") (part "Res1"))
    )
    (comp (ref "R98") (value "10K") (footprint "Buck:R0805") (libsource (lib "MYLIB") (part "ResSMD")))
    (comp (ref "R99") (value "10K") (footprint "Buck:R0805") (libsource (lib "MYLIB") (part "ResSMD")))
    (comp (ref "R100") (value "10K") (footprint "Buck:R0805") (libsource (lib "MYLIB") (part "ResSMD")))
    (comp (ref "R101") (value "10K") (footprint "Buck:R0805") (libsource (lib "MYLIB") (part "ResSMD")))
    (comp (ref "R102") (value "10K") (footprint "Buck:R0805") (libsource (lib "MYLIB") (part "ResSMD")))
    (comp (ref "R103") (value "10K") (footprint "Buck:R0805") (libsource (lib "MYLIB") (part "ResSMD")))
    (comp (ref "R104") (value "10K") (footprint "Buck:R0805") (libsource (lib "MYLIB") (part "ResSMD")))
    (comp (ref "R105") (value "10K") (footprint "Buck:R0805") (libsource (lib "MYLIB") (part "ResSMD")))
    (comp (ref "R106")
      (value "Res3")
      (footprint "Buck:R0603")
      (description "Resistor")
      (fields (field (name "ALTIUM_VALUE") "0") (field (name "PUBLISHER") "Altium Limited"))
      (libsource (lib "Miscellaneous Devices") (part "Res3"))
    )
    (comp (ref "R107") (value "0") (footprint "Buck:R0805") (libsource (lib "MYLIB") (part "ResSMD")))
    (comp (ref "R108")
      (value "Res1")
      (footprint "Buck:R0805")
      (description "Resistor")
      (fields (field (name "ALTIUM_VALUE") "1") (field (name "PUBLISHER") "Altium Limited"))
      (libsource (lib "Miscellaneous Devices") (part "Res1"))
    )
    (comp (ref "R109")
      (value "CMA02040X1209GB300")
      (footprint "Buck:MELF 0204")
      (description "Resistor")
      (fields (field (name "PUBLISHER") "Altium Limited"))
      (libsource (lib "Miscellaneous Devices") (part "Res1"))
    )
    (comp (ref "R110")
      (value "Res3")
      (footprint "Buck:R0603")
      (description "Resistor")
      (fields (field (name "ALTIUM_VALUE") "0") (field (name "PUBLISHER") "Altium Limited"))
      (libsource (lib "Miscellaneous Devices") (part "Res3"))
    )
    (comp (ref "R111")
      (value "Res3")
      (footprint "Buck:R0603")
      (description "Resistor")
      (fields (field (name "ALTIUM_VALUE") "0") (field (name "PUBLISHER") "Altium Limited"))
      (libsource (lib "Miscellaneous Devices") (part "Res3"))
    )
    (comp (ref "R112")
      (value "CMA02040X1209GB300")
      (footprint "Buck:MMF50S")
      (description "Resistor")
      (fields (field (name "ALTIUM_VALUE") "1") (field (name "PUBLISHER") "Altium Limited"))
      (libsource (lib "Miscellaneous Devices") (part "Res1"))
    )
    (comp (ref "R113") (value "5K") (footprint "Buck:R0805") (libsource (lib "MYLIB") (part "ResSMD")))
    (comp (ref "R114")
      (value "Res3")
      (footprint "Buck:R0603")
      (description "Resistor")
      (fields (field (name "ALTIUM_VALUE") "10K") (field (name "PUBLISHER") "Altium Limited"))
      (libsource (lib "Miscellaneous Devices") (part "Res3"))
    )
    (comp (ref "R115") (value "5K") (footprint "Buck:R0805") (libsource (lib "MYLIB") (part "ResSMD")))
    (comp (ref "R116") (value "5K") (footprint "Buck:R0805") (libsource (lib "MYLIB") (part "ResSMD")))
    (comp (ref "R117") (value "1K") (footprint "Buck:R0805") (libsource (lib "MYLIB") (part "ResSMD")))
    (comp (ref "R118")
      (value "Res3")
      (footprint "Buck:R0603")
      (description "Resistor")
      (fields (field (name "ALTIUM_VALUE") "10K") (field (name "PUBLISHER") "Altium Limited"))
      (libsource (lib "Miscellaneous Devices") (part "Res3"))
    )
    (comp (ref "R119") (value "15K") (footprint "Buck:R0805") (libsource (lib "MYLIB") (part "ResSMD")))
    (comp (ref "R120")
      (value "47k")
      (footprint "Buck:R0805")
      (description "Resistor")
      (fields (field (name "ALTIUM_VALUE") "47k") (field (name "PUBLISHER") "Altium Limited"))
      (libsource (lib "Miscellaneous Devices") (part "Res1"))
    )
    (comp (ref "R121")
      (value "1K")
      (footprint "Buck:R0805")
      (description "resistor 1/4 wat")
      (libsource (lib "Mylib") (part "Res"))
    )
    (comp (ref "R122") (value "1K") (footprint "Buck:R0805") (libsource (lib "MYLIB") (part "ResSMD")))
    (comp (ref "R123")
      (value "Res3")
      (footprint "Buck:R0603")
      (description "Resistor")
      (fields (field (name "ALTIUM_VALUE") "0") (field (name "PUBLISHER") "Altium Limited"))
      (libsource (lib "Miscellaneous Devices") (part "Res3"))
    )
    (comp (ref "R124")
      (value "Res3")
      (footprint "Buck:R0603")
      (description "Resistor")
      (fields (field (name "ALTIUM_VALUE") "0") (field (name "PUBLISHER") "Altium Limited"))
      (libsource (lib "Miscellaneous Devices") (part "Res3"))
    )
    (comp (ref "R125")
      (value "MOVS2825V420")
      (footprint "Buck:MOVS2825V420")
      (description "Varistor (Voltage-Sensitive Resistor)")
      (fields (field (name "PUBLISHER") "Altium Limited"))
      (libsource (lib "Miscellaneous Devices") (part "Res Varistor"))
    )
    (comp (ref "R126")
      (value "0")
      (footprint "Buck:R0603")
      (description "RES Thick Film, 2kΩ, 1%, 0.25W, 100ppm/°C, 1206")
      (fields (field (name "TOLERANCE") "1%"))
      (libsource (lib "Miscellaneous Devices") (part "1029c3af85768c4190bb7ad29bc67b5"))
    )
    (comp (ref "R127")
      (value "15k")
      (footprint "Buck:R0603")
      (description "RES Thick Film, 2kΩ, 1%, 0.25W, 100ppm/°C, 1206")
      (fields (field (name "TOLERANCE") "1%"))
      (libsource (lib "Miscellaneous Devices") (part "1029c3af85768c4190bb7ad29bc67b5"))
    )
    (comp (ref "R128") (value "0 SMD") (footprint "Buck:R0805") (libsource (lib "MYLIB") (part "ResSMD")))
    (comp (ref "R129")
      (value "4.7k")
      (footprint "Buck:R0805")
      (description "RES Thick Film, 2kΩ, 1%, 0.25W, 100ppm/°C, 1206")
      (fields (field (name "TOLERANCE") "1%"))
      (libsource (lib "Miscellaneous Devices") (part "1029c3af85768c4190bb7ad29bc67b5"))
    )
    (comp (ref "R130")
      (value "4.7k")
      (footprint "Buck:R0805")
      (description "RES Thick Film, 2kΩ, 1%, 0.25W, 100ppm/°C, 1206")
      (fields (field (name "TOLERANCE") "1%"))
      (libsource (lib "Miscellaneous Devices") (part "1029c3af85768c4190bb7ad29bc67b5"))
    )
    (comp (ref "R131") (value "100") (footprint "Buck:R0805") (libsource (lib "MYLIB") (part "ResSMD")))
    (comp (ref "R132")
      (value "4.7k")
      (footprint "Buck:R0805")
      (description "RES Thick Film, 2kΩ, 1%, 0.25W, 100ppm/°C, 1206")
      (fields (field (name "TOLERANCE") "1%"))
      (libsource (lib "Miscellaneous Devices") (part "1029c3af85768c4190bb7ad29bc67b5"))
    )
    (comp (ref "R133")
      (value "4.7k")
      (footprint "Buck:R0805")
      (description "RES Thick Film, 2kΩ, 1%, 0.25W, 100ppm/°C, 1206")
      (fields (field (name "TOLERANCE") "1%"))
      (libsource (lib "Miscellaneous Devices") (part "1029c3af85768c4190bb7ad29bc67b5"))
    )
    (comp (ref "R134") (value "0") (footprint "Buck:R0805") (libsource (lib "MYLIB") (part "ResSMD")))
    (comp (ref "R135") (value "0") (footprint "Buck:R0805") (libsource (lib "MYLIB") (part "ResSMD")))
    (comp (ref "R136")
      (value "Res1")
      (footprint "Buck:R0805")
      (description "Resistor")
      (fields (field (name "ALTIUM_VALUE") "15k") (field (name "PUBLISHER") "Altium Limited"))
      (libsource (lib "Miscellaneous Devices") (part "Res1"))
    )
    (comp (ref "R137") (value "1K") (footprint "Buck:R0805") (libsource (lib "MYLIB") (part "ResSMD")))
    (comp (ref "R138") (value "1K") (footprint "Buck:R0805") (libsource (lib "MYLIB") (part "ResSMD")))
    (comp (ref "R139") (value "1K") (footprint "Buck:R0805") (libsource (lib "MYLIB") (part "ResSMD")))
    (comp (ref "R140") (value "0 SMD") (footprint "Buck:R0805") (libsource (lib "MYLIB") (part "ResSMD")))
    (comp (ref "R141") (value "0 SMD") (footprint "Buck:R0805") (libsource (lib "MYLIB") (part "ResSMD")))
    (comp (ref "R142") (value "0 SMD") (footprint "Buck:R0805") (libsource (lib "MYLIB") (part "ResSMD")))
    (comp (ref "R143") (value "ResSMD") (footprint "Buck:R0805") (libsource (lib "MYLIB") (part "ResSMD")))
    (comp (ref "R144") (value "0 SMD") (footprint "Buck:R0805") (libsource (lib "MYLIB") (part "ResSMD")))
    (comp (ref "R145") (value "0 SMD") (footprint "Buck:R0805") (libsource (lib "MYLIB") (part "ResSMD")))
    (comp (ref "R146") (value "0 SMD") (footprint "Buck:R0805") (libsource (lib "MYLIB") (part "ResSMD")))
    (comp (ref "R147") (value "ResSMD") (footprint "Buck:R0805") (libsource (lib "MYLIB") (part "ResSMD")))
    (comp (ref "R148") (value "ResSMD") (footprint "Buck:R0805") (libsource (lib "MYLIB") (part "ResSMD")))
    (comp (ref "R149") (value "ResSMD") (footprint "Buck:R0805") (libsource (lib "MYLIB") (part "ResSMD")))
    (comp (ref "R150") (value "ResSMD") (footprint "Buck:R0805") (libsource (lib "MYLIB") (part "ResSMD")))
    (comp (ref "R151") (value "ResSMD") (footprint "Buck:R0805") (libsource (lib "MYLIB") (part "ResSMD")))
    (comp (ref "R152") (value "ResSMD") (footprint "Buck:R0805") (libsource (lib "MYLIB") (part "ResSMD")))
    (comp (ref "R153") (value "ResSMD") (footprint "Buck:R0805") (libsource (lib "MYLIB") (part "ResSMD")))
    (comp (ref "R154")
      (value "Res3")
      (footprint "Buck:R0603")
      (description "Resistor")
      (fields (field (name "ALTIUM_VALUE") "0") (field (name "PUBLISHER") "Altium Limited"))
      (libsource (lib "Miscellaneous Devices") (part "Res3"))
    )
    (comp (ref "R155") (value "ResSMD") (footprint "Buck:R0805") (libsource (lib "MYLIB") (part "ResSMD")))
    (comp (ref "R156") (value "ResSMD") (footprint "Buck:R0805") (libsource (lib "MYLIB") (part "ResSMD")))
    (comp (ref "R157") (value "ResSMD") (footprint "Buck:R0805") (libsource (lib "MYLIB") (part "ResSMD")))
    (comp (ref "R158") (value "ResSMD") (footprint "Buck:R0805") (libsource (lib "MYLIB") (part "ResSMD")))
    (comp (ref "R159") (value "ResSMD") (footprint "Buck:R0805") (libsource (lib "MYLIB") (part "ResSMD")))
    (comp (ref "R160") (value "0 SMD") (footprint "Buck:R0805") (libsource (lib "MYLIB") (part "ResSMD")))
    (comp (ref "R161") (value "ResSMD") (footprint "Buck:R0805") (libsource (lib "MYLIB") (part "ResSMD")))
    (comp (ref "R162")
      (value "Res3")
      (footprint "Buck:R0603")
      (description "Resistor")
      (fields (field (name "ALTIUM_VALUE") "0") (field (name "PUBLISHER") "Altium Limited"))
      (libsource (lib "Miscellaneous Devices") (part "Res3"))
    )
    (comp (ref "R163")
      (value "Res3")
      (footprint "Buck:R0603")
      (description "Resistor")
      (fields (field (name "ALTIUM_VALUE") "0") (field (name "PUBLISHER") "Altium Limited"))
      (libsource (lib "Miscellaneous Devices") (part "Res3"))
    )
    (comp (ref "R164") (value "ResSMD") (footprint "Buck:R0805") (libsource (lib "MYLIB") (part "ResSMD")))
    (comp (ref "R165") (value "ResSMD") (footprint "Buck:R0805") (libsource (lib "MYLIB") (part "ResSMD")))
    (comp (ref "R166") (value "ResSMD") (footprint "Buck:R0805") (libsource (lib "MYLIB") (part "ResSMD")))
    (comp (ref "R167") (value "0 SMD") (footprint "Buck:R0805") (libsource (lib "MYLIB") (part "ResSMD")))
    (comp (ref "R168") (value "0 SMD") (footprint "Buck:R0805") (libsource (lib "MYLIB") (part "ResSMD")))
    (comp (ref "R169") (value "ResSMD") (footprint "Buck:R0805") (libsource (lib "MYLIB") (part "ResSMD")))
    (comp (ref "R170") (value "ResSMD") (footprint "Buck:R0805") (libsource (lib "MYLIB") (part "ResSMD")))
    (comp (ref "R171") (value "0 SMD") (footprint "Buck:R0805") (libsource (lib "MYLIB") (part "ResSMD")))
    (comp (ref "R172") (value "0 SMD") (footprint "Buck:R0805") (libsource (lib "MYLIB") (part "ResSMD")))
    (comp (ref "R173") (value "ResSMD") (footprint "Buck:R0805") (libsource (lib "MYLIB") (part "ResSMD")))
    (comp (ref "R174") (value "ResSMD") (footprint "Buck:R0805") (libsource (lib "MYLIB") (part "ResSMD")))
    (comp (ref "R175") (value "ResSMD") (footprint "Buck:R0805") (libsource (lib "MYLIB") (part "ResSMD")))
    (comp (ref "T1")
      (value "Full Transformer")
      (footprint "Buck:Full_Transformer")
      (libsource (lib "Full bridge-V1.00") (part "Full_Transformer"))
    )
    (comp (ref "TP1")
      (value "Pad")
      (footprint "Buck:TP-0.5mm")
      (libsource (lib "") (part "Con1 pin-Small_1"))
    )
    (comp (ref "TP2")
      (value "Pad")
      (footprint "Buck:TP-0.5mm")
      (libsource (lib "MYLIB") (part "Con1 pin-Small"))
    )
    (comp (ref "TP3")
      (value "Pad")
      (footprint "Buck:TP-0.5mm")
      (libsource (lib "") (part "Con1 pin-Small_1"))
    )
    (comp (ref "TP4")
      (value "Pad")
      (footprint "Buck:TP-0.5mm")
      (libsource (lib "") (part "Con1 pin-Small_1"))
    )
    (comp (ref "TP5")
      (value "Pad")
      (footprint "Buck:TP-0.5mm")
      (libsource (lib "") (part "Con1 pin-Small_1"))
    )
    (comp (ref "TP6")
      (value "Pad")
      (footprint "Buck:TP-0.5mm")
      (libsource (lib "MYLIB") (part "Con1 pin-Small"))
    )
    (comp (ref "TP7")
      (value "Pad")
      (footprint "Buck:TP-0.5mm")
      (libsource (lib "") (part "Con1 pin-Small_3"))
    )
    (comp (ref "TP8")
      (value "Pad")
      (footprint "Buck:TP-0.5mm")
      (libsource (lib "") (part "Con1 pin-Small_2"))
    )
    (comp (ref "TP9")
      (value "Pad")
      (footprint "Buck:TP-0.5mm")
      (libsource (lib "") (part "Con1 pin-Small_1"))
    )
    (comp (ref "TP10")
      (value "Pad")
      (footprint "Buck:TP-0.5mm")
      (libsource (lib "") (part "Con1 pin-Small_1"))
    )
    (comp (ref "TP11")
      (value "Pad")
      (footprint "Buck:TP-0.5mm")
      (libsource (lib "") (part "Con1 pin-Small_1"))
    )
    (comp (ref "TP12")
      (value "Pad")
      (footprint "Buck:TP-0.5mm")
      (libsource (lib "MYLIB") (part "Con1 pin-Small"))
    )
    (comp (ref "TP13")
      (value "Pad")
      (footprint "Buck:TP-0.5mm")
      (libsource (lib "") (part "Con1 pin-Small_3"))
    )
    (comp (ref "TP14")
      (value "Pad")
      (footprint "Buck:TP-0.5mm")
      (libsource (lib "") (part "Con1 pin-Small_2"))
    )
    (comp (ref "TP15")
      (value "Pad")
      (footprint "Buck:TP-0.5mm")
      (libsource (lib "") (part "Con1 pin-Small_1"))
    )
    (comp (ref "TP16")
      (value "Pad")
      (footprint "Buck:TP-0.5mm")
      (libsource (lib "") (part "Con1 pin-Small_1"))
    )
    (comp (ref "TP17")
      (value "Pad")
      (footprint "Buck:TP-0.5mm")
      (libsource (lib "") (part "Con1 pin-Small_1"))
    )
    (comp (ref "TP18")
      (value "Pad")
      (footprint "Buck:TP-0.5mm")
      (libsource (lib "MYLIB") (part "Con1 pin-Small"))
    )
    (comp (ref "TP19")
      (value "Pad")
      (footprint "Buck:TP-0.5mm")
      (libsource (lib "") (part "Con1 pin-Small_3"))
    )
    (comp (ref "TP20")
      (value "Pad")
      (footprint "Buck:TP-0.5mm")
      (libsource (lib "") (part "Con1 pin-Small_2"))
    )
    (comp (ref "TP21")
      (value "Pad")
      (footprint "Buck:TP-0.5mm")
      (libsource (lib "") (part "Con1 pin-Small_1"))
    )
    (comp (ref "TP22")
      (value "Pad")
      (footprint "Buck:TP-0.5mm")
      (libsource (lib "") (part "Con1 pin-Small_1"))
    )
    (comp (ref "TP23")
      (value "Pad")
      (footprint "Buck:TP-0.5mm")
      (libsource (lib "") (part "Con1 pin-Small_1"))
    )
    (comp (ref "TP24")
      (value "Pad")
      (footprint "Buck:TP-0.5mm")
      (libsource (lib "MYLIB") (part "Con1 pin-Small"))
    )
    (comp (ref "TP25")
      (value "Pad")
      (footprint "Buck:TP-0.5mm")
      (libsource (lib "") (part "Con1 pin-Small_1"))
    )
    (comp (ref "TP26")
      (value "Pad")
      (footprint "Buck:TP-0.5mm")
      (libsource (lib "") (part "Con1 pin-Small_1"))
    )
    (comp (ref "TP27")
      (value "Pad")
      (footprint "Buck:TP-0.5mm")
      (libsource (lib "") (part "Con1 pin-Small_3"))
    )
    (comp (ref "TP28")
      (value "Pad")
      (footprint "Buck:TP-0.5mm")
      (libsource (lib "") (part "Con1 pin-Small_2"))
    )
    (comp (ref "TP29")
      (value "Pad")
      (footprint "Buck:TP-0.5mm")
      (libsource (lib "") (part "Con1 pin-Small_3"))
    )
    (comp (ref "TP30")
      (value "Pad")
      (footprint "Buck:TP-0.5mm")
      (libsource (lib "") (part "Con1 pin-Small_1"))
    )
    (comp (ref "TP31")
      (value "Pad")
      (footprint "Buck:TP-0.5mm")
      (libsource (lib "") (part "Con1 pin-Small_1"))
    )
    (comp (ref "TP32")
      (value "Pad")
      (footprint "Buck:TP-0.5mm")
      (libsource (lib "") (part "Con1 pin-Small_2"))
    )
    (comp (ref "TP33")
      (value "Pad")
      (footprint "Buck:TP-0.5mm")
      (libsource (lib "") (part "Con1 pin-Small_3"))
    )
    (comp (ref "TP34")
      (value "Pad")
      (footprint "Buck:TP-0.5mm")
      (libsource (lib "") (part "Con1 pin-Small_2"))
    )
    (comp (ref "TP35")
      (value "Pad")
      (footprint "Buck:TP-0.5mm")
      (libsource (lib "") (part "Con1 pin-Small_1"))
    )
    (comp (ref "TP36")
      (value "Pad")
      (footprint "Buck:TP-0.5mm")
      (libsource (lib "") (part "Con1 pin-Small_1"))
    )
    (comp (ref "TP37")
      (value "Pad")
      (footprint "Buck:TP-0.5mm")
      (libsource (lib "") (part "Con1 pin-Small_2"))
    )
    (comp (ref "TP38")
      (value "Pad")
      (footprint "Buck:TP-0.5mm")
      (libsource (lib "") (part "Con1 pin-Small_3"))
    )
    (comp (ref "TP39")
      (value "Pad")
      (footprint "Buck:TP-0.5mm")
      (libsource (lib "MYLIB") (part "Con1 pin-Small"))
    )
    (comp (ref "TP40")
      (value "Pad")
      (footprint "Buck:TP-0.5mm")
      (libsource (lib "") (part "Con1 pin-Small_1"))
    )
    (comp (ref "TP41")
      (value "Pad")
      (footprint "Buck:TP-0.5mm")
      (libsource (lib "") (part "Con1 pin-Small_1"))
    )
    (comp (ref "TP42")
      (value "Pad")
      (footprint "Buck:TP-0.5mm")
      (libsource (lib "") (part "Con1 pin-Small_2"))
    )
    (comp (ref "TP43")
      (value "Pad")
      (footprint "Buck:TP-0.5mm")
      (libsource (lib "") (part "Con1 pin-Small_1"))
    )
    (comp (ref "TP44")
      (value "Pad")
      (footprint "Buck:TP-0.5mm")
      (libsource (lib "") (part "Con1 pin-Small_1"))
    )
    (comp (ref "TP45")
      (value "Pad")
      (footprint "Buck:TP-0.5mm")
      (libsource (lib "") (part "Con1 pin-Small_3"))
    )
    (comp (ref "TP46")
      (value "Pad")
      (footprint "Buck:TP-0.5mm")
      (libsource (lib "") (part "Con1 pin-Small_2"))
    )
    (comp (ref "TP47")
      (value "Pad")
      (footprint "Buck:TP-0.5mm")
      (libsource (lib "") (part "Con1 pin-Small_1"))
    )
    (comp (ref "TP48")
      (value "Pad")
      (footprint "Buck:TP-0.5mm")
      (libsource (lib "") (part "Con1 pin-Small_2"))
    )
    (comp (ref "TP49")
      (value "Pad")
      (footprint "Buck:TP-0.5mm")
      (libsource (lib "") (part "Con1 pin-Small_1"))
    )
    (comp (ref "TP50")
      (value "Pad")
      (footprint "Buck:TP-0.5mm")
      (libsource (lib "") (part "Con1 pin-Small_1"))
    )
    (comp (ref "TP51")
      (value "Pad")
      (footprint "Buck:TP-0.5mm")
      (libsource (lib "") (part "Con1 pin-Small_1"))
    )
    (comp (ref "TP52")
      (value "Pad")
      (footprint "Buck:TP-0.5mm")
      (libsource (lib "") (part "Con1 pin-Small_1"))
    )
    (comp (ref "TP53")
      (value "Pad")
      (footprint "Buck:TP-0.5mm")
      (libsource (lib "MYLIB") (part "Con1 pin-Small"))
    )
    (comp (ref "TP54")
      (value "Pad")
      (footprint "Buck:TP-0.5mm")
      (libsource (lib "") (part "Con1 pin-Small_1"))
    )
    (comp (ref "TP55")
      (value "Pad")
      (footprint "Buck:TP-0.5mm")
      (libsource (lib "MYLIB") (part "Con1 pin-Small"))
    )
    (comp (ref "TP56")
      (value "Pad")
      (footprint "Buck:TP-0.5mm")
      (libsource (lib "MYLIB") (part "Con1 pin-Small"))
    )
    (comp (ref "TP57")
      (value "Pad")
      (footprint "Buck:TP-0.5mm")
      (libsource (lib "MYLIB") (part "Con1 pin-Small"))
    )
    (comp (ref "TP58")
      (value "Pad")
      (footprint "Buck:TP-0.5mm")
      (libsource (lib "") (part "Con1 pin-Small_1"))
    )
    (comp (ref "TP59")
      (value "Pad")
      (footprint "Buck:TP-0.5mm")
      (libsource (lib "") (part "Con1 pin-Small_1"))
    )
    (comp (ref "TP60")
      (value "Pad")
      (footprint "Buck:TP-0.5mm")
      (libsource (lib "") (part "Con1 pin-Small_1"))
    )
    (comp (ref "TP61")
      (value "Pad")
      (footprint "Buck:TP-0.5mm")
      (libsource (lib "MYLIB") (part "Con1 pin-Small"))
    )
    (comp (ref "TP62")
      (value "Pad")
      (footprint "Buck:TP-0.5mm")
      (libsource (lib "") (part "Con1 pin-Small_1"))
    )
    (comp (ref "TP63")
      (value "Pad")
      (footprint "Buck:TP-0.5mm")
      (libsource (lib "MYLIB") (part "Con1 pin-Small"))
    )
    (comp (ref "TP64")
      (value "Pad")
      (footprint "Buck:TP-0.5mm")
      (libsource (lib "") (part "Con1 pin-Small_2"))
    )
    (comp (ref "TP65")
      (value "Pad")
      (footprint "Buck:TP-0.5mm")
      (libsource (lib "MYLIB") (part "Con1 pin-Small"))
    )
    (comp (ref "TP66")
      (value "Pad")
      (footprint "Buck:TP-0.5mm")
      (libsource (lib "") (part "Con1 pin-Small_3"))
    )
    (comp (ref "TP67")
      (value "Pad")
      (footprint "Buck:TP-0.5mm")
      (libsource (lib "") (part "Con1 pin-Small_3"))
    )
    (comp (ref "TP68")
      (value "Pad")
      (footprint "Buck:TP-0.5mm")
      (libsource (lib "") (part "Con1 pin-Small_1"))
    )
    (comp (ref "TP69")
      (value "Pad")
      (footprint "Buck:TP-0.5mm")
      (libsource (lib "") (part "Con1 pin-Small_1"))
    )
    (comp (ref "TP70")
      (value "Pad")
      (footprint "Buck:TP-0.5mm")
      (libsource (lib "") (part "Con1 pin-Small_1"))
    )
    (comp (ref "TP71")
      (value "Pad")
      (footprint "Buck:TP-0.5mm")
      (libsource (lib "") (part "Con1 pin-Small_1"))
    )
    (comp (ref "TP72")
      (value "Pad")
      (footprint "Buck:TP-0.5mm")
      (libsource (lib "") (part "Con1 pin-Small_1"))
    )
    (comp (ref "TP73")
      (value "Pad")
      (footprint "Buck:TP-0.5mm")
      (libsource (lib "MYLIB") (part "Con1 pin-Small"))
    )
    (comp (ref "TP74")
      (value "Pad")
      (footprint "Buck:TP-0.5mm")
      (libsource (lib "") (part "Con1 pin-Small_1"))
    )
    (comp (ref "TP75")
      (value "Pad")
      (footprint "Buck:TP-0.5mm")
      (libsource (lib "") (part "Con1 pin-Small_1"))
    )
    (comp (ref "TP76")
      (value "Pad")
      (footprint "Buck:TP-0.5mm")
      (libsource (lib "") (part "Con1 pin-Small_2"))
    )
    (comp (ref "TP77")
      (value "Pad")
      (footprint "Buck:TP-0.5mm")
      (libsource (lib "MYLIB") (part "Con1 pin-Small"))
    )
    (comp (ref "TP78")
      (value "Pad")
      (footprint "Buck:TP-0.5mm")
      (libsource (lib "") (part "Con1 pin-Small_3"))
    )
    (comp (ref "TP79")
      (value "Pad")
      (footprint "Buck:TP-0.5mm")
      (libsource (lib "") (part "Con1 pin-Small_1"))
    )
    (comp (ref "TP80")
      (value "Pad")
      (footprint "Buck:TP-0.5mm")
      (libsource (lib "MYLIB") (part "Con1 pin-Small"))
    )
    (comp (ref "TP81")
      (value "Pad")
      (footprint "Buck:TP-0.5mm")
      (libsource (lib "") (part "Con1 pin-Small_1"))
    )
    (comp (ref "TP82")
      (value "Pad")
      (footprint "Buck:TP-0.5mm")
      (libsource (lib "") (part "Con1 pin-Small_1"))
    )
    (comp (ref "TP83")
      (value "Pad")
      (footprint "Buck:TP-0.5mm")
      (libsource (lib "") (part "Con1 pin-Small_3"))
    )
    (comp (ref "TP84")
      (value "Pad")
      (footprint "Buck:TP-0.5mm")
      (libsource (lib "") (part "Con1 pin-Small_3"))
    )
    (comp (ref "TP85")
      (value "Pad")
      (footprint "Buck:TP-0.5mm")
      (libsource (lib "") (part "Con1 pin-Small_1"))
    )
    (comp (ref "TP86")
      (value "Pad")
      (footprint "Buck:TP-0.5mm")
      (libsource (lib "") (part "Con1 pin-Small_1"))
    )
    (comp (ref "TP87")
      (value "Pad")
      (footprint "Buck:TP-0.5mm")
      (libsource (lib "") (part "Con1 pin-Small_2"))
    )
    (comp (ref "TP88")
      (value "Pad")
      (footprint "Buck:TP-0.5mm")
      (libsource (lib "") (part "Con1 pin-Small_1"))
    )
    (comp (ref "TP89")
      (value "Pad")
      (footprint "Buck:TP-0.5mm")
      (libsource (lib "MYLIB") (part "Con1 pin-Small"))
    )
    (comp (ref "U1")
      (value "MJWI10-24S12-MIN")
      (footprint "Buck:MJWI10-24S12")
      (libsource (lib "MYLIB") (part "MINMAX-MJWI20"))
    )
    (comp (ref "U2")
      (value "SN74LVC1G17DBVT SOT23")
      (footprint "Buck:SOT95P280X145-5N")
      (description "IC BUF NON-INVERT 5.5V SC70-5")
      (libsource (lib "Miscellaneous Devices") (part "333895c48767551a2a38df23237d11a"))
    )
    (comp (ref "U3")
      (value "PC81713NIP1B")
      (footprint "Buck:SOP-4L")
      (libsource (lib "MYLIB") (part "PC817"))
    )
    (comp (ref "U4")
      (value "SN74LVC1G17DBVT SOT23")
      (footprint "Buck:SOT95P280X145-5N")
      (description "IC BUF NON-INVERT 5.5V SC70-5")
      (libsource (lib "Miscellaneous Devices") (part "333895c48767551a2a38df23237d11a"))
    )
    (comp (ref "U5")
      (value "SI8261BBD-C-ISR")
      (footprint "Buck:SLAB-SDIP6_N")
      (fields (field (name "PARTNUMBER") "Si8261BBD-C-IS") (field (name "MANUFACTURER") "Silicon Labs"))
      (libsource (lib "Miscellaneous Devices") (part "SLAB-Si8261X-SDIP-6"))
    )
    (comp (ref "U6")
      (value "IXDN609SIATR")
      (footprint "Buck:IXDN609SIATR")
      (fields (field (name "PARTNUMBER") "IXDN609SI"))
      (libsource (lib "Miscellaneous Devices") (part "IXYS-IXDN609-8"))
    )
    (comp (ref "U7")
      (value "SN74LVC1G17DBVT SOT23")
      (footprint "Buck:SOT95P280X145-5N")
      (description "IC BUF NON-INVERT 5.5V SC70-5")
      (libsource (lib "Miscellaneous Devices") (part "333895c48767551a2a38df23237d11a"))
    )
    (comp (ref "U8")
      (value "SI8261BBD-C-ISR")
      (footprint "Buck:SLAB-SDIP6_N")
      (fields (field (name "PARTNUMBER") "Si8261BBD-C-IS") (field (name "MANUFACTURER") "Silicon Labs"))
      (libsource (lib "Miscellaneous Devices") (part "SLAB-Si8261X-SDIP-6"))
    )
    (comp (ref "U9")
      (value "IXDN609SIATR")
      (footprint "Buck:IXDN609SIATR")
      (fields (field (name "PARTNUMBER") "IXDN609SI"))
      (libsource (lib "Miscellaneous Devices") (part "IXYS-IXDN609-8"))
    )
    (comp (ref "U10")
      (value "SN74LVC1G17DBVT SOT23")
      (footprint "Buck:SOT95P280X145-5N")
      (description "IC BUF NON-INVERT 5.5V SC70-5")
      (libsource (lib "Miscellaneous Devices") (part "333895c48767551a2a38df23237d11a"))
    )
    (comp (ref "U11")
      (value "SI8261BBD-C-ISR")
      (footprint "Buck:SLAB-SDIP6_N")
      (fields (field (name "PARTNUMBER") "Si8261BBD-C-IS") (field (name "MANUFACTURER") "Silicon Labs"))
      (libsource (lib "Miscellaneous Devices") (part "SLAB-Si8261X-SDIP-6"))
    )
    (comp (ref "U12")
      (value "IXDN609SIATR")
      (footprint "Buck:IXDN609SIATR")
      (fields (field (name "PARTNUMBER") "IXDN609SI"))
      (libsource (lib "Miscellaneous Devices") (part "IXYS-IXDN609-8"))
    )
    (comp (ref "U13")
      (value "SN74LVC1G17DBVT SOT23")
      (footprint "Buck:SOT95P280X145-5N")
      (description "IC BUF NON-INVERT 5.5V SC70-5")
      (libsource (lib "Miscellaneous Devices") (part "333895c48767551a2a38df23237d11a"))
    )
    (comp (ref "U14")
      (value "SI8261BBD-C-ISR")
      (footprint "Buck:SLAB-SDIP6_N")
      (fields (field (name "PARTNUMBER") "Si8261BBD-C-IS") (field (name "MANUFACTURER") "Silicon Labs"))
      (libsource (lib "Miscellaneous Devices") (part "SLAB-Si8261X-SDIP-6"))
    )
    (comp (ref "U15")
      (value "IXDN609SIATR")
      (footprint "Buck:IXDN609SIATR")
      (fields (field (name "PARTNUMBER") "IXDN609SI"))
      (libsource (lib "Miscellaneous Devices") (part "IXYS-IXDN609-8"))
    )
    (comp (ref "U16")
      (value "LT1764AEQ-3.3")
      (footprint "Buck:LT1764AEQ33TRPBF")
      (fields (field (name "MANUFACTURER") "Linear Technology"))
      (libsource (lib "Linear Technology Power Management LDO Linear Regulators") (part "LT1764AEQ-3.3"))
    )
    (comp (ref "U17")
      (value "CAS 15-NP")
      (footprint "Buck:CAS 15-NP")
      (description "Current Transducer, 5 V, -40 to 85 degC, 10-Pin THD, RoHS, Tray")
      (fields (field (name "MANUFACTURER") "LEM") (field (name "PARTNUMBER") "LTSR 15-NP"))
      (libsource (lib "Miscellaneous Devices") (part "CAS 15-NP"))
    )
    (comp (ref "U18")
      (value "MJWI10-12S05")
      (footprint "Buck:MJWI15-24S05")
      (libsource (lib "MYLIB") (part "MINMAX-MJWI20"))
    )
    (comp (ref "U19")
      (value "TLV2781IDBVR")
      (footprint "Buck:DBV0005A_L")
      (fields (field (name "PARTNUMBER") "OPA320AIDBVR") (field (name "MANUFACTURER") "Texas Instruments"))
      (libsource (lib "Miscellaneous Devices") (part "TI-OPA_SM7XXXX-DBV5"))
    )
    (comp (ref "U20")
      (value "NCV8114ASN165T1G")
      (footprint "Buck:TSOP-5")
      (libsource (lib "Miscellaneous Devices") (part "ONSC-MC78PC-SOT-23-5"))
    )
    (comp (ref "U21")
      (value "OPA27GP")
      (footprint "Buck:P0008A")
      (fields (field (name "MANUFACTURER") "Texas Instruments"))
      (libsource (lib "Miscellaneous Devices") (part "TI-OPA27-X8"))
    )
  )
  (nets
    (net (code "1") (name "+3.3VD") (class "Default")
      (node (ref "C73") (pin "2") (pinfunction "2_2") (pintype "passive"))
      (node (ref "R11") (pin "2") (pinfunction "2_2") (pintype "passive"))
      (node (ref "R128") (pin "1") (pinfunction "1_1") (pintype "passive"))
      (node (ref "R140") (pin "1") (pinfunction "1_1") (pintype "passive"))
      (node (ref "R150") (pin "2") (pinfunction "2_2") (pintype "passive"))
      (node (ref "R171") (pin "1") (pinfunction "1_1") (pintype "passive"))
      (node (ref "R2") (pin "2") (pinfunction "2_2") (pintype "passive"))
      (node (ref "R44") (pin "2") (pinfunction "2_2") (pintype "passive"))
      (node (ref "R70") (pin "2") (pinfunction "2_2") (pintype "passive"))
      (node (ref "R95") (pin "2") (pinfunction "2_2") (pintype "passive"))
      (node (ref "U19") (pin "5") (pinfunction "V+_5") (pintype "power_in"))
    )
    (net (code "2") (name "+3.3VD2") (class "Default")
      (node (ref "C60") (pin "1") (pinfunction "1_1") (pintype "passive"))
      (node (ref "C64") (pin "2") (pinfunction "2_2") (pintype "passive"))
      (node (ref "DS10") (pin "1") (pinfunction "A_1") (pintype "passive"))
      (node (ref "R128") (pin "2") (pinfunction "2_2") (pintype "passive"))
      (node (ref "R14") (pin "1") (pinfunction "1_1") (pintype "passive"))
      (node (ref "TP26") (pin "1") (pinfunction "1_1") (pintype "passive"))
      (node (ref "U16") (pin "4") (pinfunction "OUT_4") (pintype "power_in"))
      (node (ref "U16") (pin "5") (pinfunction "SENSE_5") (pintype "input"))
    )
    (net (code "3") (name "+5V_MICRO") (class "Default")
      (node (ref "C69") (pin "2") (pinfunction "2_2") (pintype "passive"))
      (node (ref "C71") (pin "2") (pinfunction "2_2") (pintype "passive"))
      (node (ref "C72") (pin "2") (pinfunction "2_2") (pintype "passive"))
      (node (ref "C78") (pin "2") (pinfunction "2_2") (pintype "passive"))
      (node (ref "DS12") (pin "1") (pinfunction "A_1") (pintype "passive"))
      (node (ref "FB11") (pin "1") (pinfunction "1_1") (pintype "power_in"))
      (node (ref "J2") (pin "13") (pinfunction "13_13") (pintype "passive"))
      (node (ref "J2") (pin "25") (pinfunction "25_25") (pintype "passive"))
      (node (ref "R12") (pin "1") (pinfunction "1_1") (pintype "passive"))
      (node (ref "R138") (pin "1") (pinfunction "1_1") (pintype "passive"))
      (node (ref "R144") (pin "1") (pinfunction "1_1") (pintype "passive"))
      (node (ref "R149") (pin "2") (pinfunction "2_2") (pintype "passive"))
      (node (ref "R15") (pin "1") (pinfunction "1_1") (pintype "passive"))
      (node (ref "R172") (pin "2") (pinfunction "2_2") (pintype "passive"))
      (node (ref "R3") (pin "1") (pinfunction "1_1") (pintype "passive"))
      (node (ref "R45") (pin "1") (pinfunction "1_1") (pintype "passive"))
      (node (ref "R71") (pin "1") (pinfunction "1_1") (pintype "passive"))
      (node (ref "R96") (pin "1") (pinfunction "1_1") (pintype "passive"))
      (node (ref "TP25") (pin "1") (pinfunction "1_1") (pintype "passive"))
      (node (ref "TP63") (pin "1") (pinfunction "1_1") (pintype "passive"))
      (node (ref "U17") (pin "13") (pinfunction "+5V_13") (pintype "passive"))
      (node (ref "U20") (pin "1") (pinfunction "VIN_1") (pintype "power_in"))
    )
    (net (code "4") (name "+12V_Digital IN") (class "Default")
      (node (ref "C2") (pin "1") (pinfunction "1_1") (pintype "passive"))
      (node (ref "C49") (pin "1") (pinfunction "1_1") (pintype "passive"))
      (node (ref "C52") (pin "1") (pinfunction "1_1") (pintype "passive"))
      (node (ref "C56") (pin "1") (pinfunction "1_1") (pintype "passive"))
      (node (ref "C68") (pin "1") (pinfunction "1_1") (pintype "passive"))
      (node (ref "C89") (pin "1") (pinfunction "1_1") (pintype "passive"))
      (node (ref "J1") (pin "1") (pinfunction "1_1") (pintype "passive"))
      (node (ref "PS1") (pin "22") (pinfunction "+VIN_22") (pintype "input"))
      (node (ref "PS1") (pin "23") (pinfunction "+VIN_23") (pintype "input"))
      (node (ref "PS2") (pin "22") (pinfunction "+VIN_22") (pintype "input"))
      (node (ref "PS2") (pin "23") (pinfunction "+VIN_23") (pintype "input"))
      (node (ref "PS3") (pin "22") (pinfunction "+VIN_22") (pintype "input"))
      (node (ref "PS3") (pin "23") (pinfunction "+VIN_23") (pintype "input"))
      (node (ref "PS4") (pin "22") (pinfunction "+VIN_22") (pintype "input"))
      (node (ref "PS4") (pin "23") (pinfunction "+VIN_23") (pintype "input"))
      (node (ref "TP55") (pin "1") (pinfunction "1_1") (pintype "passive"))
      (node (ref "U1") (pin "1") (pinfunction "+In_1") (pintype "passive"))
      (node (ref "U18") (pin "1") (pinfunction "+In_1") (pintype "passive"))
    )
    (net (code "5") (name "1.65V") (class "Default")
      (node (ref "C79") (pin "2") (pinfunction "2_2") (pintype "passive"))
      (node (ref "R135") (pin "2") (pinfunction "2_2") (pintype "passive"))
      (node (ref "R146") (pin "1") (pinfunction "1_1") (pintype "passive"))
      (node (ref "TP86") (pin "1") (pinfunction "1_1") (pintype "passive"))
      (node (ref "U20") (pin "5") (pinfunction "VOUT_5") (pintype "power_in"))
    )
    (net (code "6") (name "3") (class "Default")
      (node (ref "J2") (pin "12") (pinfunction "12_12") (pintype "passive"))
      (node (ref "TP66") (pin "1") (pinfunction "1_1") (pintype "passive"))
    )
    (net (code "7") (name "4") (class "Default")
      (node (ref "J2") (pin "24") (pinfunction "24_24") (pintype "passive"))
      (node (ref "TP67") (pin "1") (pinfunction "1_1") (pintype "passive"))
    )
    (net (code "8") (name "AC Output") (class "Default")
      (node (ref "F2") (pin "2") (pinfunction "2_2") (pintype "passive"))
      (node (ref "P2") (pin "1") (pinfunction "1_1") (pintype "passive"))
      (node (ref "P2") (pin "2") (pinfunction "2_2") (pintype "passive"))
      (node (ref "R141") (pin "1") (pinfunction "1_1") (pintype "passive"))
      (node (ref "TP69") (pin "1") (pinfunction "1_1") (pintype "passive"))
    )
    (net (code "9") (name "E FB TEMP") (class "Default")
      (node (ref "J2") (pin "8") (pinfunction "8_8") (pintype "passive"))
    )
    (net (code "10") (name "FB TEMP of the heatsink") (class "Default")
      (node (ref "FB2") (pin "2") (pinfunction "2_2") (pintype "power_in"))
      (node (ref "J2") (pin "16") (pinfunction "16_16") (pintype "passive"))
    )
    (net (code "11") (name "Fan") (class "Default")
      (node (ref "C3") (pin "1") (pinfunction "1_1") (pintype "passive"))
      (node (ref "C4") (pin "2") (pinfunction "2_2") (pintype "passive"))
      (node (ref "D1") (pin "1") (pinfunction "A_1") (pintype "passive"))
      (node (ref "DS1") (pin "1") (pinfunction "A_1") (pintype "passive"))
      (node (ref "P1") (pin "1") (pinfunction "1_1") (pintype "passive"))
      (node (ref "U1") (pin "3") (pinfunction "+Out_3") (pintype "passive"))
    )
    (net (code "12") (name "Fan FB command") (class "Default")
      (node (ref "FB1") (pin "1") (pinfunction "1_1") (pintype "power_in"))
      (node (ref "J2") (pin "23") (pinfunction "23_23") (pintype "passive"))
    )
    (net (code "13") (name "GND side FB") (class "Default")
      (node (ref "C21") (pin "1") (pinfunction "1_1") (pintype "passive"))
      (node (ref "C24") (pin "1") (pinfunction "1_1") (pintype "passive"))
      (node (ref "C26") (pin "2") (pinfunction "2_2") (pintype "passive"))
      (node (ref "C27") (pin "2") (pinfunction "2_2") (pintype "passive"))
      (node (ref "C28") (pin "2") (pinfunction "2_2") (pintype "passive"))
      (node (ref "C29") (pin "2") (pinfunction "2_2") (pintype "passive"))
      (node (ref "C30") (pin "2") (pinfunction "2_2") (pintype "passive"))
      (node (ref "C31") (pin "2") (pinfunction "2_2") (pintype "passive"))
      (node (ref "C32") (pin "1") (pinfunction "1_1") (pintype "passive"))
      (node (ref "C35") (pin "1") (pinfunction "1_1") (pintype "passive"))
      (node (ref "C37") (pin "2") (pinfunction "2_2") (pintype "passive"))
      (node (ref "C38") (pin "2") (pinfunction "2_2") (pintype "passive"))
      (node (ref "C39") (pin "1") (pinfunction "1_1") (pintype "passive"))
      (node (ref "C40") (pin "1") (pinfunction "1_1") (pintype "passive"))
      (node (ref "C45") (pin "2") (pinfunction "2_2") (pintype "passive"))
      (node (ref "C46") (pin "2") (pinfunction "2_2") (pintype "passive"))
      (node (ref "CR11") (pin "1") (pinfunction "A_1") (pintype "passive"))
      (node (ref "CR17") (pin "1") (pinfunction "A_1") (pintype "passive"))
      (node (ref "CR7") (pin "1") (pinfunction "A_1") (pintype "passive"))
      (node (ref "D13") (pin "1") (pinfunction "A_1") (pintype "passive"))
      (node (ref "D14") (pin "1") (pinfunction "A_1") (pintype "passive"))
      (node (ref "D15") (pin "1") (pinfunction "A_1") (pintype "passive"))
      (node (ref "D16") (pin "1") (pinfunction "A_1") (pintype "passive"))
      (node (ref "D17") (pin "1") (pinfunction "A_1") (pintype "passive"))
      (node (ref "D18") (pin "1") (pinfunction "A_1") (pintype "passive"))
      (node (ref "P3") (pin "3") (pinfunction "3_3") (pintype "passive"))
      (node (ref "P3") (pin "4") (pinfunction "4_4") (pintype "passive"))
      (node (ref "Q2") (pin "3") (pinfunction "E_3") (pintype "passive"))
      (node (ref "Q3") (pin "3") (pinfunction "E_3") (pintype "passive"))
      (node (ref "R125") (pin "1") (pinfunction "1_1") (pintype "passive"))
      (node (ref "R167") (pin "2") (pinfunction "2_2") (pintype "passive"))
      (node (ref "R168") (pin "2") (pinfunction "2_2") (pintype "passive"))
      (node (ref "R40") (pin "1") (pinfunction "1_1") (pintype "passive"))
      (node (ref "R42") (pin "2") (pinfunction "2_2") (pintype "passive"))
      (node (ref "R43") (pin "2") (pinfunction "2_2") (pintype "passive"))
      (node (ref "R51") (pin "1") (pinfunction "1_1") (pintype "passive"))
      (node (ref "R57") (pin "1") (pinfunction "1_1") (pintype "passive"))
      (node (ref "R58") (pin "1") (pinfunction "1_1") (pintype "passive"))
      (node (ref "R64") (pin "1") (pinfunction "1_1") (pintype "passive"))
      (node (ref "R65") (pin "2") (pinfunction "2_2") (pintype "passive"))
      (node (ref "R66") (pin "2") (pinfunction "2_2") (pintype "passive"))
      (node (ref "R68") (pin "1") (pinfunction "1_1") (pintype "passive"))
      (node (ref "R77") (pin "1") (pinfunction "1_1") (pintype "passive"))
      (node (ref "R86") (pin "1") (pinfunction "1_1") (pintype "passive"))
      (node (ref "TP33") (pin "1") (pinfunction "1_1") (pintype "passive"))
      (node (ref "TP83") (pin "1") (pinfunction "1_1") (pintype "passive"))
      (node (ref "TP84") (pin "1") (pinfunction "1_1") (pintype "passive"))
      (node (ref "TP85") (pin "1") (pinfunction "1_1") (pintype "passive"))
      (node (ref "U12") (pin "4") (pinfunction "GND_4") (pintype "power_in"))
      (node (ref "U12") (pin "5") (pinfunction "GND_5") (pintype "power_in"))
      (node (ref "U9") (pin "4") (pinfunction "GND_4") (pintype "power_in"))
      (node (ref "U9") (pin "5") (pinfunction "GND_5") (pintype "power_in"))
    )
    (net (code "14") (name "GND- VDD Sensor voltage out") (class "Default")
      (node (ref "C76") (pin "2") (pinfunction "2_2") (pintype "passive"))
      (node (ref "C90") (pin "1") (pinfunction "1_1") (pintype "passive"))
      (node (ref "R92") (pin "2") (pinfunction "2_2") (pintype "passive"))
      (node (ref "R93") (pin "2") (pinfunction "2_2") (pintype "passive"))
      (node (ref "TP89") (pin "1") (pinfunction "1_1") (pintype "passive"))
      (node (ref "U18") (pin "5") (pinfunction "-Out_5") (pintype "passive"))
    )
    (net (code "15") (name "GND_DIGITAL") (class "Default")
      (node (ref "C1") (pin "2") (pinfunction "2_2") (pintype "passive"))
      (node (ref "C20") (pin "2") (pinfunction "2_2") (pintype "passive"))
      (node (ref "C41") (pin "2") (pinfunction "2_2") (pintype "passive"))
      (node (ref "C5") (pin "2") (pinfunction "2_2") (pintype "passive"))
      (node (ref "C53") (pin "2") (pinfunction "2_2") (pintype "passive"))
      (node (ref "C60") (pin "2") (pinfunction "2_2") (pintype "passive"))
      (node (ref "C62") (pin "1") (pinfunction "1_1") (pintype "passive"))
      (node (ref "C63") (pin "1") (pinfunction "1_1") (pintype "passive"))
      (node (ref "C64") (pin "1") (pinfunction "1_1") (pintype "passive"))
      (node (ref "C69") (pin "1") (pinfunction "1_1") (pintype "passive"))
      (node (ref "C71") (pin "1") (pinfunction "1_1") (pintype "passive"))
      (node (ref "C72") (pin "1") (pinfunction "1_1") (pintype "passive"))
      (node (ref "C73") (pin "1") (pinfunction "1_1") (pintype "passive"))
      (node (ref "C75") (pin "1") (pinfunction "1_1") (pintype "passive"))
      (node (ref "C77") (pin "1") (pinfunction "1_1") (pintype "passive"))
      (node (ref "C78") (pin "1") (pinfunction "1_1") (pintype "passive"))
      (node (ref "C79") (pin "1") (pinfunction "1_1") (pintype "passive"))
      (node (ref "C80") (pin "2") (pinfunction "2_2") (pintype "passive"))
      (node (ref "C82") (pin "2") (pinfunction "2_2") (pintype "passive"))
      (node (ref "C83") (pin "2") (pinfunction "2_2") (pintype "passive"))
      (node (ref "C86") (pin "2") (pinfunction "2_2") (pintype "passive"))
      (node (ref "J2") (pin "1") (pinfunction "1_1") (pintype "passive"))
      (node (ref "J2") (pin "14") (pinfunction "14_14") (pintype "passive"))
      (node (ref "Q5") (pin "5") (pinfunction "GND2_5") (pintype "power_in"))
      (node (ref "R10") (pin "2") (pinfunction "2_2") (pintype "passive"))
      (node (ref "R100") (pin "2") (pinfunction "2_2") (pintype "passive"))
      (node (ref "R101") (pin "2") (pinfunction "2_2") (pintype "passive"))
      (node (ref "R102") (pin "2") (pinfunction "2_2") (pintype "passive"))
      (node (ref "R103") (pin "2") (pinfunction "2_2") (pintype "passive"))
      (node (ref "R104") (pin "2") (pinfunction "2_2") (pintype "passive"))
      (node (ref "R105") (pin "2") (pinfunction "2_2") (pintype "passive"))
      (node (ref "R111") (pin "1") (pinfunction "1_1") (pintype "passive"))
      (node (ref "R113") (pin "2") (pinfunction "2_2") (pintype "passive"))
      (node (ref "R114") (pin "1") (pinfunction "1_1") (pintype "passive"))
      (node (ref "R115") (pin "2") (pinfunction "2_2") (pintype "passive"))
      (node (ref "R116") (pin "2") (pinfunction "2_2") (pintype "passive"))
      (node (ref "R117") (pin "2") (pinfunction "2_2") (pintype "passive"))
      (node (ref "R118") (pin "1") (pinfunction "1_1") (pintype "passive"))
      (node (ref "R121") (pin "2") (pinfunction "2_2") (pintype "passive"))
      (node (ref "R122") (pin "2") (pinfunction "2_2") (pintype "passive"))
      (node (ref "R124") (pin "1") (pinfunction "1_1") (pintype "passive"))
      (node (ref "R129") (pin "1") (pinfunction "1_1") (pintype "passive"))
      (node (ref "R134") (pin "2") (pinfunction "2_2") (pintype "passive"))
      (node (ref "R136") (pin "1") (pinfunction "1_1") (pintype "passive"))
      (node (ref "R137") (pin "2") (pinfunction "2_2") (pintype "passive"))
      (node (ref "R139") (pin "2") (pinfunction "2_2") (pintype "passive"))
      (node (ref "R143") (pin "2") (pinfunction "2_2") (pintype "passive"))
      (node (ref "R145") (pin "1") (pinfunction "1_1") (pintype "passive"))
      (node (ref "R160") (pin "2") (pinfunction "2_2") (pintype "passive"))
      (node (ref "R164") (pin "2") (pinfunction "2_2") (pintype "passive"))
      (node (ref "R175") (pin "2") (pinfunction "2_2") (pintype "passive"))
      (node (ref "R21") (pin "1") (pinfunction "1_1") (pintype "passive"))
      (node (ref "R23") (pin "2") (pinfunction "2_2") (pintype "passive"))
      (node (ref "R24") (pin "2") (pinfunction "2_2") (pintype "passive"))
      (node (ref "R25") (pin "1") (pinfunction "1_1") (pintype "passive"))
      (node (ref "R26") (pin "2") (pinfunction "2_2") (pintype "passive"))
      (node (ref "R27") (pin "2") (pinfunction "2_2") (pintype "passive"))
      (node (ref "R28") (pin "2") (pinfunction "2_2") (pintype "passive"))
      (node (ref "R29") (pin "1") (pinfunction "1_1") (pintype "passive"))
      (node (ref "R53") (pin "1") (pinfunction "1_1") (pintype "passive"))
      (node (ref "R56") (pin "2") (pinfunction "2_2") (pintype "passive"))
      (node (ref "R59") (pin "1") (pinfunction "1_1") (pintype "passive"))
      (node (ref "R6") (pin "1") (pinfunction "1_1") (pintype "passive"))
      (node (ref "R60") (pin "2") (pinfunction "2_2") (pintype "passive"))
      (node (ref "R61") (pin "2") (pinfunction "2_2") (pintype "passive"))
      (node (ref "R62") (pin "2") (pinfunction "2_2") (pintype "passive"))
      (node (ref "R63") (pin "1") (pinfunction "1_1") (pintype "passive"))
      (node (ref "R78") (pin "1") (pinfunction "1_1") (pintype "passive"))
      (node (ref "R80") (pin "2") (pinfunction "2_2") (pintype "passive"))
      (node (ref "R81") (pin "1") (pinfunction "1_1") (pintype "passive"))
      (node (ref "R82") (pin "2") (pinfunction "2_2") (pintype "passive"))
      (node (ref "R83") (pin "2") (pinfunction "2_2") (pintype "passive"))
      (node (ref "R84") (pin "2") (pinfunction "2_2") (pintype "passive"))
      (node (ref "R85") (pin "1") (pinfunction "1_1") (pintype "passive"))
      (node (ref "R98") (pin "2") (pinfunction "2_2") (pintype "passive"))
      (node (ref "R99") (pin "2") (pinfunction "2_2") (pintype "passive"))
      (node (ref "TP14") (pin "1") (pinfunction "1_1") (pintype "passive"))
      (node (ref "TP20") (pin "1") (pinfunction "1_1") (pintype "passive"))
      (node (ref "TP28") (pin "1") (pinfunction "1_1") (pintype "passive"))
      (node (ref "TP29") (pin "1") (pinfunction "1_1") (pintype "passive"))
      (node (ref "TP32") (pin "1") (pinfunction "1_1") (pintype "passive"))
      (node (ref "TP38") (pin "1") (pinfunction "1_1") (pintype "passive"))
      (node (ref "TP39") (pin "1") (pinfunction "1_1") (pintype "passive"))
      (node (ref "TP48") (pin "1") (pinfunction "1_1") (pintype "passive"))
      (node (ref "TP64") (pin "1") (pinfunction "1_1") (pintype "passive"))
      (node (ref "TP8") (pin "1") (pinfunction "1_1") (pintype "passive"))
      (node (ref "TP87") (pin "1") (pinfunction "1_1") (pintype "passive"))
      (node (ref "U10") (pin "3") (pinfunction "GND_3") (pintype "power_in"))
      (node (ref "U11") (pin "3") (pinfunction "CATHODE_3") (pintype "passive"))
      (node (ref "U13") (pin "3") (pinfunction "GND_3") (pintype "power_in"))
      (node (ref "U14") (pin "3") (pinfunction "CATHODE_3") (pintype "passive"))
      (node (ref "U16") (pin "3") (pinfunction "GND_3") (pintype "power_in"))
      (node (ref "U16") (pin "6") (pinfunction "TAB_6") (pintype "power_in"))
      (node (ref "U17") (pin "12") (pinfunction "0V_12") (pintype "passive"))
      (node (ref "U2") (pin "3") (pinfunction "GND_3") (pintype "power_in"))
      (node (ref "U20") (pin "2") (pinfunction "GND_2") (pintype "power_in"))
      (node (ref "U3") (pin "2") (pinfunction "K_2") (pintype "passive"))
      (node (ref "U4") (pin "3") (pinfunction "GND_3") (pintype "power_in"))
      (node (ref "U5") (pin "3") (pinfunction "CATHODE_3") (pintype "passive"))
      (node (ref "U7") (pin "3") (pinfunction "GND_3") (pintype "power_in"))
      (node (ref "U8") (pin "3") (pinfunction "CATHODE_3") (pintype "passive"))
    )
    (net (code "16") (name "GND_Fan") (class "Default")
      (node (ref "C3") (pin "2") (pinfunction "2_2") (pintype "passive"))
      (node (ref "C4") (pin "1") (pinfunction "1_1") (pintype "passive"))
      (node (ref "D2") (pin "1") (pinfunction "A_1") (pintype "passive"))
      (node (ref "P1") (pin "2") (pinfunction "2_2") (pintype "passive"))
      (node (ref "R1") (pin "2") (pinfunction "2_2") (pintype "passive"))
      (node (ref "TP2") (pin "1") (pinfunction "1_1") (pintype "passive"))
      (node (ref "U1") (pin "5") (pinfunction "-Out_5") (pintype "passive"))
    )
    (net (code "17") (name "GND_GS1") (class "Default")
      (node (ref "C19") (pin "2") (pinfunction "2_2") (pintype "passive"))
      (node (ref "C47") (pin "2") (pinfunction "2_2") (pintype "passive"))
      (node (ref "C48") (pin "1") (pinfunction "1_1") (pintype "passive"))
      (node (ref "C6") (pin "2") (pinfunction "2_2") (pintype "passive"))
      (node (ref "C7") (pin "2") (pinfunction "2_2") (pintype "passive"))
      (node (ref "C8") (pin "1") (pinfunction "1_1") (pintype "passive"))
      (node (ref "CR2") (pin "1") (pinfunction "A_1") (pintype "passive"))
      (node (ref "PS1") (pin "16") (pinfunction "-VOUT_16") (pintype "output"))
      (node (ref "R20") (pin "2") (pinfunction "2_2") (pintype "passive"))
      (node (ref "R35") (pin "1") (pinfunction "1_1") (pintype "passive"))
      (node (ref "R8") (pin "2") (pinfunction "2_2") (pintype "passive"))
      (node (ref "R87") (pin "2") (pinfunction "2_2") (pintype "passive"))
      (node (ref "TP53") (pin "1") (pinfunction "1_1") (pintype "passive"))
      (node (ref "TP6") (pin "1") (pinfunction "1_1") (pintype "passive"))
      (node (ref "U5") (pin "4") (pinfunction "GND_4") (pintype "power_in"))
    )
    (net (code "18") (name "GND_GS2") (class "Default")
      (node (ref "C33") (pin "2") (pinfunction "2_2") (pintype "passive"))
      (node (ref "C34") (pin "2") (pinfunction "2_2") (pintype "passive"))
      (node (ref "C36") (pin "1") (pinfunction "1_1") (pintype "passive"))
      (node (ref "C39") (pin "2") (pinfunction "2_2") (pintype "passive"))
      (node (ref "C50") (pin "2") (pinfunction "2_2") (pintype "passive"))
      (node (ref "C51") (pin "1") (pinfunction "1_1") (pintype "passive"))
      (node (ref "CR6") (pin "1") (pinfunction "A_1") (pintype "passive"))
      (node (ref "PS2") (pin "16") (pinfunction "-VOUT_16") (pintype "output"))
      (node (ref "R40") (pin "2") (pinfunction "2_2") (pintype "passive"))
      (node (ref "R51") (pin "2") (pinfunction "2_2") (pintype "passive"))
      (node (ref "R65") (pin "1") (pinfunction "1_1") (pintype "passive"))
      (node (ref "R88") (pin "2") (pinfunction "2_2") (pintype "passive"))
      (node (ref "TP12") (pin "1") (pinfunction "1_1") (pintype "passive"))
      (node (ref "TP56") (pin "1") (pinfunction "1_1") (pintype "passive"))
      (node (ref "U8") (pin "4") (pinfunction "GND_4") (pintype "power_in"))
    )
    (net (code "19") (name "GND_GS3") (class "Default")
      (node (ref "C40") (pin "2") (pinfunction "2_2") (pintype "passive"))
      (node (ref "C42") (pin "2") (pinfunction "2_2") (pintype "passive"))
      (node (ref "C43") (pin "2") (pinfunction "2_2") (pintype "passive"))
      (node (ref "C44") (pin "1") (pinfunction "1_1") (pintype "passive"))
      (node (ref "C54") (pin "1") (pinfunction "1_1") (pintype "passive"))
      (node (ref "C55") (pin "2") (pinfunction "2_2") (pintype "passive"))
      (node (ref "CR10") (pin "1") (pinfunction "A_1") (pintype "passive"))
      (node (ref "PS3") (pin "16") (pinfunction "-VOUT_16") (pintype "output"))
      (node (ref "R66") (pin "1") (pinfunction "1_1") (pintype "passive"))
      (node (ref "R68") (pin "2") (pinfunction "2_2") (pintype "passive"))
      (node (ref "R77") (pin "2") (pinfunction "2_2") (pintype "passive"))
      (node (ref "R94") (pin "2") (pinfunction "2_2") (pintype "passive"))
      (node (ref "TP18") (pin "1") (pinfunction "1_1") (pintype "passive"))
      (node (ref "TP61") (pin "1") (pinfunction "1_1") (pintype "passive"))
      (node (ref "U11") (pin "4") (pinfunction "GND_4") (pintype "power_in"))
    )
    (net (code "20") (name "GND_GS4") (class "Default")
      (node (ref "C23") (pin "2") (pinfunction "2_2") (pintype "passive"))
      (node (ref "C57") (pin "2") (pinfunction "2_2") (pintype "passive"))
      (node (ref "C58") (pin "2") (pinfunction "2_2") (pintype "passive"))
      (node (ref "C59") (pin "1") (pinfunction "1_1") (pintype "passive"))
      (node (ref "C61") (pin "2") (pinfunction "2_2") (pintype "passive"))
      (node (ref "C67") (pin "1") (pinfunction "1_1") (pintype "passive"))
      (node (ref "CR14") (pin "1") (pinfunction "A_1") (pintype "passive"))
      (node (ref "PS4") (pin "16") (pinfunction "-VOUT_16") (pintype "output"))
      (node (ref "R110") (pin "2") (pinfunction "2_2") (pintype "passive"))
      (node (ref "R119") (pin "2") (pinfunction "2_2") (pintype "passive"))
      (node (ref "R36") (pin "1") (pinfunction "1_1") (pintype "passive"))
      (node (ref "R90") (pin "2") (pinfunction "2_2") (pintype "passive"))
      (node (ref "TP24") (pin "1") (pinfunction "1_1") (pintype "passive"))
      (node (ref "TP65") (pin "1") (pinfunction "1_1") (pintype "passive"))
      (node (ref "U14") (pin "4") (pinfunction "GND_4") (pintype "power_in"))
    )
    (net (code "21") (name "GND_High voltage-out") (class "Default")
      (node (ref "L1") (pin "2") (pinfunction "2_2") (pintype "passive"))
      (node (ref "P2") (pin "3") (pinfunction "3_3") (pintype "passive"))
      (node (ref "P2") (pin "4") (pinfunction "4_4") (pintype "passive"))
      (node (ref "R151") (pin "1") (pinfunction "1_1") (pintype "passive"))
      (node (ref "R152") (pin "1") (pinfunction "1_1") (pintype "passive"))
      (node (ref "R154") (pin "2") (pinfunction "2_2") (pintype "passive"))
      (node (ref "R162") (pin "1") (pinfunction "1_1") (pintype "passive"))
      (node (ref "R163") (pin "1") (pinfunction "1_1") (pintype "passive"))
      (node (ref "TP42") (pin "1") (pinfunction "1_1") (pintype "passive"))
      (node (ref "TP74") (pin "1") (pinfunction "1_1") (pintype "passive"))
    )
    (net (code "22") (name "GND_IN") (class "Default")
      (node (ref "C2") (pin "2") (pinfunction "2_2") (pintype "passive"))
      (node (ref "C49") (pin "2") (pinfunction "2_2") (pintype "passive"))
      (node (ref "C52") (pin "2") (pinfunction "2_2") (pintype "passive"))
      (node (ref "C56") (pin "2") (pinfunction "2_2") (pintype "passive"))
      (node (ref "C68") (pin "2") (pinfunction "2_2") (pintype "passive"))
      (node (ref "C89") (pin "2") (pinfunction "2_2") (pintype "passive"))
      (node (ref "J1") (pin "2") (pinfunction "2_2") (pintype "passive"))
      (node (ref "PS1") (pin "2") (pinfunction "-VIN_2") (pintype "input"))
      (node (ref "PS1") (pin "3") (pinfunction "-VIN_3") (pintype "input"))
      (node (ref "PS2") (pin "2") (pinfunction "-VIN_2") (pintype "input"))
      (node (ref "PS2") (pin "3") (pinfunction "-VIN_3") (pintype "input"))
      (node (ref "PS3") (pin "2") (pinfunction "-VIN_2") (pintype "input"))
      (node (ref "PS3") (pin "3") (pinfunction "-VIN_3") (pintype "input"))
      (node (ref "PS4") (pin "2") (pinfunction "-VIN_2") (pintype "input"))
      (node (ref "PS4") (pin "3") (pinfunction "-VIN_3") (pintype "input"))
      (node (ref "TP57") (pin "1") (pinfunction "1_1") (pintype "passive"))
      (node (ref "U1") (pin "2") (pinfunction "-In_2") (pintype "passive"))
      (node (ref "U18") (pin "2") (pinfunction "-In_2") (pintype "passive"))
      (node (ref "U3") (pin "3") (pinfunction "E_3") (pintype "passive"))
    )
    (net (code "23") (name "Gate 1") (class "Default")
      (node (ref "D8") (pin "2") (pinfunction "C_2") (pintype "passive"))
      (node (ref "Q1") (pin "1") (pinfunction "G_1") (pintype "passive"))
      (node (ref "R19") (pin "2") (pinfunction "2_2") (pintype "passive"))
      (node (ref "R33") (pin "2") (pinfunction "2_2") (pintype "passive"))
      (node (ref "R7") (pin "2") (pinfunction "2_2") (pintype "passive"))
      (node (ref "R9") (pin "2") (pinfunction "2_2") (pintype "passive"))
      (node (ref "TP71") (pin "1") (pinfunction "1_1") (pintype "passive"))
    )
    (net (code "24") (name "Gate 2") (class "Default")
      (node (ref "D15") (pin "2") (pinfunction "C_2") (pintype "passive"))
      (node (ref "Q2") (pin "1") (pinfunction "G_1") (pintype "passive"))
      (node (ref "R37") (pin "2") (pinfunction "2_2") (pintype "passive"))
      (node (ref "R41") (pin "2") (pinfunction "2_2") (pintype "passive"))
      (node (ref "R50") (pin "2") (pinfunction "2_2") (pintype "passive"))
      (node (ref "R57") (pin "2") (pinfunction "2_2") (pintype "passive"))
      (node (ref "TP79") (pin "1") (pinfunction "1_1") (pintype "passive"))
    )
    (net (code "25") (name "Gate 3") (class "Default")
      (node (ref "D16") (pin "2") (pinfunction "C_2") (pintype "passive"))
      (node (ref "Q3") (pin "1") (pinfunction "G_1") (pintype "passive"))
      (node (ref "R58") (pin "2") (pinfunction "2_2") (pintype "passive"))
      (node (ref "R67") (pin "2") (pinfunction "2_2") (pintype "passive"))
      (node (ref "R69") (pin "2") (pinfunction "2_2") (pintype "passive"))
      (node (ref "R76") (pin "2") (pinfunction "2_2") (pintype "passive"))
      (node (ref "TP80") (pin "1") (pinfunction "1_1") (pintype "passive"))
    )
    (net (code "26") (name "Gate 4") (class "Default")
      (node (ref "D10") (pin "2") (pinfunction "C_2") (pintype "passive"))
      (node (ref "Q4") (pin "1") (pinfunction "G_1") (pintype "passive"))
      (node (ref "R109") (pin "2") (pinfunction "2_2") (pintype "passive"))
      (node (ref "R34") (pin "2") (pinfunction "2_2") (pintype "passive"))
      (node (ref "R89") (pin "2") (pinfunction "2_2") (pintype "passive"))
      (node (ref "R91") (pin "2") (pinfunction "2_2") (pintype "passive"))
      (node (ref "TP73") (pin "1") (pinfunction "1_1") (pintype "passive"))
    )
    (net (code "27") (name "High side FB") (class "Default")
      (node (ref "C24") (pin "2") (pinfunction "2_2") (pintype "passive"))
      (node (ref "D5") (pin "2") (pinfunction "C_2") (pintype "passive"))
      (node (ref "D6") (pin "2") (pinfunction "C_2") (pintype "passive"))
      (node (ref "F1") (pin "2") (pinfunction "2_2") (pintype "passive"))
      (node (ref "Q1") (pin "2") (pinfunction "C_2") (pintype "passive"))
      (node (ref "Q4") (pin "2") (pinfunction "C_2") (pintype "passive"))
      (node (ref "R142") (pin "1") (pinfunction "1_1") (pintype "passive"))
      (node (ref "R31") (pin "2") (pinfunction "2_2") (pintype "passive"))
      (node (ref "R32") (pin "2") (pinfunction "2_2") (pintype "passive"))
      (node (ref "TP68") (pin "1") (pinfunction "1_1") (pintype "passive"))
    )
    (net (code "28") (name "Input 400V") (class "Default")
      (node (ref "F4") (pin "1") (pinfunction "1_1") (pintype "passive"))
      (node (ref "P3") (pin "1") (pinfunction "1_1") (pintype "passive"))
      (node (ref "P3") (pin "2") (pinfunction "2_2") (pintype "passive"))
      (node (ref "R125") (pin "2") (pinfunction "2_2") (pintype "passive"))
      (node (ref "TP31") (pin "1") (pinfunction "1_1") (pintype "passive"))
    )
    (net (code "29") (name "Input voltage of FB") (class "Default")
      (node (ref "J2") (pin "15") (pinfunction "15_15") (pintype "passive"))
      (node (ref "TP59") (pin "1") (pinfunction "1_1") (pintype "passive"))
    )
    (net (code "30") (name "M1 FB command") (class "Default")
      (node (ref "FB3") (pin "1") (pinfunction "1_1") (pintype "power_in"))
      (node (ref "FB9") (pin "2") (pinfunction "2_2") (pintype "power_in"))
      (node (ref "R105") (pin "1") (pinfunction "1_1") (pintype "passive"))
      (node (ref "R26") (pin "1") (pinfunction "1_1") (pintype "passive"))
      (node (ref "TP3") (pin "1") (pinfunction "1_1") (pintype "passive"))
      (node (ref "TP49") (pin "1") (pinfunction "1_1") (pintype "passive"))
    )
    (net (code "31") (name "M2 FB command") (class "Default")
      (node (ref "FB4") (pin "1") (pinfunction "1_1") (pintype "power_in"))
      (node (ref "FB8") (pin "2") (pinfunction "2_2") (pintype "power_in"))
      (node (ref "R104") (pin "1") (pinfunction "1_1") (pintype "passive"))
      (node (ref "R60") (pin "1") (pinfunction "1_1") (pintype "passive"))
      (node (ref "TP50") (pin "1") (pinfunction "1_1") (pintype "passive"))
      (node (ref "TP9") (pin "1") (pinfunction "1_1") (pintype "passive"))
    )
    (net (code "32") (name "M3 FB command") (class "Default")
      (node (ref "FB5") (pin "1") (pinfunction "1_1") (pintype "power_in"))
      (node (ref "FB7") (pin "2") (pinfunction "2_2") (pintype "power_in"))
      (node (ref "R103") (pin "1") (pinfunction "1_1") (pintype "passive"))
      (node (ref "R82") (pin "1") (pinfunction "1_1") (pintype "passive"))
      (node (ref "TP15") (pin "1") (pinfunction "1_1") (pintype "passive"))
      (node (ref "TP51") (pin "1") (pinfunction "1_1") (pintype "passive"))
    )
    (net (code "33") (name "M4 FB command") (class "Default")
      (node (ref "FB10") (pin "1") (pinfunction "1_1") (pintype "power_in"))
      (node (ref "FB6") (pin "2") (pinfunction "2_2") (pintype "power_in"))
      (node (ref "R102") (pin "1") (pinfunction "1_1") (pintype "passive"))
      (node (ref "R115") (pin "1") (pinfunction "1_1") (pintype "passive"))
      (node (ref "TP21") (pin "1") (pinfunction "1_1") (pintype "passive"))
      (node (ref "TP52") (pin "1") (pinfunction "1_1") (pintype "passive"))
    )
    (net (code "34") (name "Net-(C11-Pad1)") (class "Default")
      (node (ref "C11") (pin "1") (pinfunction "1_1") (pintype "passive"))
      (node (ref "C12") (pin "1") (pinfunction "1_1") (pintype "passive"))
      (node (ref "C13") (pin "1") (pinfunction "1_1") (pintype "passive"))
      (node (ref "R31") (pin "1") (pinfunction "1_1") (pintype "passive"))
    )
    (net (code "35") (name "Net-(C15-Pad1)") (class "Default")
      (node (ref "C15") (pin "1") (pinfunction "1_1") (pintype "passive"))
      (node (ref "C16") (pin "1") (pinfunction "1_1") (pintype "passive"))
      (node (ref "C18") (pin "1") (pinfunction "1_1") (pintype "passive"))
      (node (ref "R32") (pin "1") (pinfunction "1_1") (pintype "passive"))
    )
    (net (code "36") (name "Net-(C22-Pad1)") (class "Default")
      (node (ref "C22") (pin "1") (pinfunction "1_1") (pintype "passive"))
      (node (ref "C25") (pin "1") (pinfunction "1_1") (pintype "passive"))
      (node (ref "F2") (pin "1") (pinfunction "1_1") (pintype "passive"))
    )
    (net (code "37") (name "Net-(C22-Pad2)") (class "Default")
      (node (ref "C22") (pin "2") (pinfunction "2_2") (pintype "passive"))
      (node (ref "C25") (pin "2") (pinfunction "2_2") (pintype "passive"))
      (node (ref "F3") (pin "2") (pinfunction "2_2") (pintype "passive"))
    )
    (net (code "38") (name "Net-(C26-Pad1)") (class "Default")
      (node (ref "C26") (pin "1") (pinfunction "1_1") (pintype "passive"))
      (node (ref "C27") (pin "1") (pinfunction "1_1") (pintype "passive"))
      (node (ref "C28") (pin "1") (pinfunction "1_1") (pintype "passive"))
      (node (ref "R52") (pin "1") (pinfunction "1_1") (pintype "passive"))
    )
    (net (code "39") (name "Net-(C29-Pad1)") (class "Default")
      (node (ref "C29") (pin "1") (pinfunction "1_1") (pintype "passive"))
      (node (ref "C30") (pin "1") (pinfunction "1_1") (pintype "passive"))
      (node (ref "C31") (pin "1") (pinfunction "1_1") (pintype "passive"))
      (node (ref "R54") (pin "1") (pinfunction "1_1") (pintype "passive"))
    )
    (net (code "40") (name "Net-(C74-Pad1)") (class "Default")
      (node (ref "C74") (pin "1") (pinfunction "1_1") (pintype "passive"))
      (node (ref "R132") (pin "2") (pinfunction "2_2") (pintype "passive"))
      (node (ref "R133") (pin "1") (pinfunction "1_1") (pintype "passive"))
    )
    (net (code "41") (name "Net-(C74-Pad2)") (class "Default")
      (node (ref "C74") (pin "2") (pinfunction "2_2") (pintype "passive"))
      (node (ref "R129") (pin "2") (pinfunction "2_2") (pintype "passive"))
      (node (ref "R130") (pin "1") (pinfunction "1_1") (pintype "passive"))
    )
    (net (code "42") (name "Net-(C75-Pad2)") (class "Default")
      (node (ref "C75") (pin "2") (pinfunction "2_2") (pintype "passive"))
      (node (ref "FB12") (pin "1") (pinfunction "1_1") (pintype "power_in"))
      (node (ref "R131") (pin "2") (pinfunction "2_2") (pintype "passive"))
      (node (ref "TP36") (pin "1") (pinfunction "1_1") (pintype "passive"))
    )
    (net (code "43") (name "Net-(C81-Pad2)") (class "Default")
      (node (ref "C81") (pin "2") (pinfunction "2_2") (pintype "passive"))
      (node (ref "R153") (pin "2") (pinfunction "2_2") (pintype "passive"))
    )
    (net (code "44") (name "Net-(C88-Pad2)") (class "Default")
      (node (ref "C88") (pin "2") (pinfunction "2_2") (pintype "passive"))
      (node (ref "R173") (pin "2") (pinfunction "2_2") (pintype "passive"))
      (node (ref "R174") (pin "1") (pinfunction "1_1") (pintype "passive"))
    )
    (net (code "45") (name "Net-(CR1-A)") (class "Default")
      (node (ref "CR1") (pin "1") (pinfunction "A_1") (pintype "passive"))
      (node (ref "CR2") (pin "2") (pinfunction "K_2") (pintype "passive"))
      (node (ref "R18") (pin "1") (pinfunction "1_1") (pintype "passive"))
      (node (ref "R30") (pin "2") (pinfunction "2_2") (pintype "passive"))
      (node (ref "TP5") (pin "1") (pinfunction "1_1") (pintype "passive"))
      (node (ref "U5") (pin "5") (pinfunction "VO_5") (pintype "output"))
    )
    (net (code "46") (name "Net-(CR3-K)") (class "Default")
      (node (ref "CR3") (pin "2") (pinfunction "K_2") (pintype "passive"))
      (node (ref "CR4") (pin "1") (pinfunction "A_1") (pintype "passive"))
      (node (ref "D3") (pin "2") (pinfunction "C_2") (pintype "passive"))
      (node (ref "D4") (pin "2") (pinfunction "C_2") (pintype "passive"))
      (node (ref "R13") (pin "1") (pinfunction "1_1") (pintype "passive"))
      (node (ref "R22") (pin "1") (pinfunction "1_1") (pintype "passive"))
      (node (ref "TP7") (pin "1") (pinfunction "1_1") (pintype "passive"))
      (node (ref "U6") (pin "6") (pinfunction "OUT_6") (pintype "output"))
      (node (ref "U6") (pin "7") (pinfunction "OUT_7") (pintype "output"))
    )
    (net (code "47") (name "Net-(CR5-A)") (class "Default")
      (node (ref "CR5") (pin "1") (pinfunction "A_1") (pintype "passive"))
      (node (ref "CR6") (pin "2") (pinfunction "K_2") (pintype "passive"))
      (node (ref "R49") (pin "1") (pinfunction "1_1") (pintype "passive"))
      (node (ref "R64") (pin "2") (pinfunction "2_2") (pintype "passive"))
      (node (ref "TP11") (pin "1") (pinfunction "1_1") (pintype "passive"))
      (node (ref "U8") (pin "5") (pinfunction "VO_5") (pintype "output"))
    )
    (net (code "48") (name "Net-(CR7-K)") (class "Default")
      (node (ref "CR7") (pin "2") (pinfunction "K_2") (pintype "passive"))
      (node (ref "CR8") (pin "1") (pinfunction "A_1") (pintype "passive"))
      (node (ref "D11") (pin "2") (pinfunction "C_2") (pintype "passive"))
      (node (ref "D12") (pin "2") (pinfunction "C_2") (pintype "passive"))
      (node (ref "R46") (pin "1") (pinfunction "1_1") (pintype "passive"))
      (node (ref "R55") (pin "1") (pinfunction "1_1") (pintype "passive"))
      (node (ref "TP13") (pin "1") (pinfunction "1_1") (pintype "passive"))
      (node (ref "U9") (pin "6") (pinfunction "OUT_6") (pintype "output"))
      (node (ref "U9") (pin "7") (pinfunction "OUT_7") (pintype "output"))
    )
    (net (code "49") (name "Net-(CR10-K)") (class "Default")
      (node (ref "CR10") (pin "2") (pinfunction "K_2") (pintype "passive"))
      (node (ref "CR9") (pin "1") (pinfunction "A_1") (pintype "passive"))
      (node (ref "R75") (pin "1") (pinfunction "1_1") (pintype "passive"))
      (node (ref "R86") (pin "2") (pinfunction "2_2") (pintype "passive"))
      (node (ref "TP17") (pin "1") (pinfunction "1_1") (pintype "passive"))
      (node (ref "U11") (pin "5") (pinfunction "VO_5") (pintype "output"))
    )
    (net (code "50") (name "Net-(CR11-K)") (class "Default")
      (node (ref "CR11") (pin "2") (pinfunction "K_2") (pintype "passive"))
      (node (ref "CR12") (pin "1") (pinfunction "A_1") (pintype "passive"))
      (node (ref "D19") (pin "2") (pinfunction "C_2") (pintype "passive"))
      (node (ref "D20") (pin "2") (pinfunction "C_2") (pintype "passive"))
      (node (ref "R72") (pin "1") (pinfunction "1_1") (pintype "passive"))
      (node (ref "R79") (pin "1") (pinfunction "1_1") (pintype "passive"))
      (node (ref "TP19") (pin "1") (pinfunction "1_1") (pintype "passive"))
      (node (ref "U12") (pin "6") (pinfunction "OUT_6") (pintype "output"))
      (node (ref "U12") (pin "7") (pinfunction "OUT_7") (pintype "output"))
    )
    (net (code "51") (name "Net-(CR13-A)") (class "Default")
      (node (ref "CR13") (pin "1") (pinfunction "A_1") (pintype "passive"))
      (node (ref "CR14") (pin "2") (pinfunction "K_2") (pintype "passive"))
      (node (ref "R108") (pin "1") (pinfunction "1_1") (pintype "passive"))
      (node (ref "R120") (pin "2") (pinfunction "2_2") (pintype "passive"))
      (node (ref "TP23") (pin "1") (pinfunction "1_1") (pintype "passive"))
      (node (ref "U14") (pin "5") (pinfunction "VO_5") (pintype "output"))
    )
    (net (code "52") (name "Net-(CR15-K)") (class "Default")
      (node (ref "CR15") (pin "2") (pinfunction "K_2") (pintype "passive"))
      (node (ref "CR16") (pin "1") (pinfunction "A_1") (pintype "passive"))
      (node (ref "D21") (pin "2") (pinfunction "C_2") (pintype "passive"))
      (node (ref "D22") (pin "2") (pinfunction "C_2") (pintype "passive"))
      (node (ref "R112") (pin "1") (pinfunction "1_1") (pintype "passive"))
      (node (ref "R97") (pin "1") (pinfunction "1_1") (pintype "passive"))
      (node (ref "TP27") (pin "1") (pinfunction "1_1") (pintype "passive"))
      (node (ref "U15") (pin "6") (pinfunction "OUT_6") (pintype "output"))
      (node (ref "U15") (pin "7") (pinfunction "OUT_7") (pintype "output"))
    )
    (net (code "53") (name "Net-(CR17-K)") (class "Default")
      (node (ref "CR17") (pin "2") (pinfunction "K_2") (pintype "passive"))
      (node (ref "CR18") (pin "2") (pinfunction "K_2") (pintype "passive"))
    )
    (net (code "54") (name "Net-(CR18-A)") (class "Default")
      (node (ref "C21") (pin "2") (pinfunction "2_2") (pintype "passive"))
      (node (ref "CR18") (pin "1") (pinfunction "A_1") (pintype "passive"))
      (node (ref "F1") (pin "1") (pinfunction "1_1") (pintype "passive"))
      (node (ref "F4") (pin "2") (pinfunction "2_2") (pintype "passive"))
      (node (ref "R38") (pin "1") (pinfunction "1_1") (pintype "passive"))
      (node (ref "R39") (pin "1") (pinfunction "1_1") (pintype "passive"))
    )
    (net (code "55") (name "Net-(D1-K)") (class "Default")
      (node (ref "D1") (pin "2") (pinfunction "K_2") (pintype "passive"))
      (node (ref "D2") (pin "2") (pinfunction "K_2") (pintype "passive"))
    )
    (net (code "56") (name "Net-(D3-A)") (class "Default")
      (node (ref "D3") (pin "1") (pinfunction "A_1") (pintype "passive"))
      (node (ref "D4") (pin "1") (pinfunction "A_1") (pintype "passive"))
      (node (ref "R7") (pin "1") (pinfunction "1_1") (pintype "passive"))
      (node (ref "R9") (pin "1") (pinfunction "1_1") (pintype "passive"))
    )
    (net (code "57") (name "Net-(D11-A)") (class "Default")
      (node (ref "D11") (pin "1") (pinfunction "A_1") (pintype "passive"))
      (node (ref "D12") (pin "1") (pinfunction "A_1") (pintype "passive"))
      (node (ref "R37") (pin "1") (pinfunction "1_1") (pintype "passive"))
      (node (ref "R41") (pin "1") (pinfunction "1_1") (pintype "passive"))
    )
    (net (code "58") (name "Net-(D19-A)") (class "Default")
      (node (ref "D19") (pin "1") (pinfunction "A_1") (pintype "passive"))
      (node (ref "D20") (pin "1") (pinfunction "A_1") (pintype "passive"))
      (node (ref "R67") (pin "1") (pinfunction "1_1") (pintype "passive"))
      (node (ref "R69") (pin "1") (pinfunction "1_1") (pintype "passive"))
    )
    (net (code "59") (name "Net-(D21-A)") (class "Default")
      (node (ref "D21") (pin "1") (pinfunction "A_1") (pintype "passive"))
      (node (ref "D22") (pin "1") (pinfunction "A_1") (pintype "passive"))
      (node (ref "R89") (pin "1") (pinfunction "1_1") (pintype "passive"))
      (node (ref "R91") (pin "1") (pinfunction "1_1") (pintype "passive"))
    )
    (net (code "60") (name "Net-(DS1-K)") (class "Default")
      (node (ref "DS1") (pin "2") (pinfunction "K_2") (pintype "passive"))
      (node (ref "R1") (pin "1") (pinfunction "1_1") (pintype "passive"))
    )
    (net (code "61") (name "Net-(DS2-A)") (class "Default")
      (node (ref "DS2") (pin "1") (pinfunction "A_1") (pintype "passive"))
      (node (ref "R5") (pin "1") (pinfunction "1_1") (pintype "passive"))
      (node (ref "TP1") (pin "1") (pinfunction "1_1") (pintype "passive"))
      (node (ref "U2") (pin "4") (pinfunction "Y_4") (pintype "output"))
    )
    (net (code "62") (name "Net-(DS2-K)") (class "Default")
      (node (ref "DS2") (pin "2") (pinfunction "K_2") (pintype "passive"))
      (node (ref "R10") (pin "1") (pinfunction "1_1") (pintype "passive"))
    )
    (net (code "63") (name "Net-(DS3-A)") (class "Default")
      (node (ref "DS3") (pin "1") (pinfunction "A_1") (pintype "passive"))
      (node (ref "R17") (pin "1") (pinfunction "1_1") (pintype "passive"))
      (node (ref "TP4") (pin "1") (pinfunction "1_1") (pintype "passive"))
      (node (ref "U4") (pin "4") (pinfunction "Y_4") (pintype "output"))
    )
    (net (code "64") (name "Net-(DS3-K)") (class "Default")
      (node (ref "DS3") (pin "2") (pinfunction "K_2") (pintype "passive"))
      (node (ref "R28") (pin "1") (pinfunction "1_1") (pintype "passive"))
    )
    (net (code "65") (name "Net-(DS4-A)") (class "Default")
      (node (ref "DS4") (pin "1") (pinfunction "A_1") (pintype "passive"))
      (node (ref "R48") (pin "1") (pinfunction "1_1") (pintype "passive"))
      (node (ref "TP10") (pin "1") (pinfunction "1_1") (pintype "passive"))
      (node (ref "U7") (pin "4") (pinfunction "Y_4") (pintype "output"))
    )
    (net (code "66") (name "Net-(DS4-K)") (class "Default")
      (node (ref "DS4") (pin "2") (pinfunction "K_2") (pintype "passive"))
      (node (ref "R62") (pin "1") (pinfunction "1_1") (pintype "passive"))
    )
    (net (code "67") (name "Net-(DS5-A)") (class "Default")
      (node (ref "DS5") (pin "1") (pinfunction "A_1") (pintype "passive"))
      (node (ref "R74") (pin "1") (pinfunction "1_1") (pintype "passive"))
      (node (ref "TP16") (pin "1") (pinfunction "1_1") (pintype "passive"))
      (node (ref "U10") (pin "4") (pinfunction "Y_4") (pintype "output"))
    )
    (net (code "68") (name "Net-(DS5-K)") (class "Default")
      (node (ref "DS5") (pin "2") (pinfunction "K_2") (pintype "passive"))
      (node (ref "R84") (pin "1") (pinfunction "1_1") (pintype "passive"))
    )
    (net (code "69") (name "Net-(DS6-K)") (class "Default")
      (node (ref "DS6") (pin "2") (pinfunction "K_2") (pintype "passive"))
      (node (ref "R87") (pin "1") (pinfunction "1_1") (pintype "passive"))
    )
    (net (code "70") (name "Net-(DS7-K)") (class "Default")
      (node (ref "DS7") (pin "2") (pinfunction "K_2") (pintype "passive"))
      (node (ref "R88") (pin "1") (pinfunction "1_1") (pintype "passive"))
    )
    (net (code "71") (name "Net-(DS8-K)") (class "Default")
      (node (ref "DS8") (pin "2") (pinfunction "K_2") (pintype "passive"))
      (node (ref "R94") (pin "1") (pinfunction "1_1") (pintype "passive"))
    )
    (net (code "72") (name "Net-(DS9-A)") (class "Default")
      (node (ref "DS9") (pin "1") (pinfunction "A_1") (pintype "passive"))
      (node (ref "R107") (pin "1") (pinfunction "1_1") (pintype "passive"))
      (node (ref "TP22") (pin "1") (pinfunction "1_1") (pintype "passive"))
      (node (ref "U13") (pin "4") (pinfunction "Y_4") (pintype "output"))
    )
    (net (code "73") (name "Net-(DS9-K)") (class "Default")
      (node (ref "DS9") (pin "2") (pinfunction "K_2") (pintype "passive"))
      (node (ref "R117") (pin "1") (pinfunction "1_1") (pintype "passive"))
    )
    (net (code "74") (name "Net-(DS10-K)") (class "Default")
      (node (ref "DS10") (pin "2") (pinfunction "K_2") (pintype "passive"))
      (node (ref "R121") (pin "1") (pinfunction "1_1") (pintype "passive"))
    )
    (net (code "75") (name "Net-(DS11-K)") (class "Default")
      (node (ref "DS11") (pin "2") (pinfunction "K_2") (pintype "passive"))
      (node (ref "R119") (pin "1") (pinfunction "1_1") (pintype "passive"))
    )
    (net (code "76") (name "Net-(DS12-K)") (class "Default")
      (node (ref "DS12") (pin "2") (pinfunction "K_2") (pintype "passive"))
      (node (ref "R122") (pin "1") (pinfunction "1_1") (pintype "passive"))
    )
    (net (code "77") (name "Net-(DS13-K)") (class "Default")
      (node (ref "DS13") (pin "2") (pinfunction "K_2") (pintype "passive"))
      (node (ref "R93") (pin "1") (pinfunction "1_1") (pintype "passive"))
    )
    (net (code "78") (name "Net-(F3-Pad1)") (class "Default")
      (node (ref "F3") (pin "1") (pinfunction "1_1") (pintype "passive"))
      (node (ref "U17") (pin "10") (pinfunction "OUT_10") (pintype "passive"))
      (node (ref "U17") (pin "8") (pinfunction "OUT_8") (pintype "passive"))
      (node (ref "U17") (pin "9") (pinfunction "OUT_9") (pintype "passive"))
    )
    (net (code "79") (name "Net-(FB1-Pad2)") (class "Default")
      (node (ref "FB1") (pin "2") (pinfunction "2_2") (pintype "power_in"))
      (node (ref "R4") (pin "1") (pinfunction "1_1") (pintype "passive"))
    )
    (net (code "80") (name "Net-(FB2-Pad1)") (class "Default")
      (node (ref "FB2") (pin "1") (pinfunction "1_1") (pintype "power_in"))
      (node (ref "P1") (pin "4") (pinfunction "4_4") (pintype "passive"))
      (node (ref "R24") (pin "1") (pinfunction "1_1") (pintype "passive"))
    )
    (net (code "81") (name "Net-(FB3-Pad2)") (class "Default")
      (node (ref "FB3") (pin "2") (pinfunction "2_2") (pintype "power_in"))
      (node (ref "R16") (pin "1") (pinfunction "1_1") (pintype "passive"))
      (node (ref "R27") (pin "1") (pinfunction "1_1") (pintype "passive"))
    )
    (net (code "82") (name "Net-(FB4-Pad2)") (class "Default")
      (node (ref "FB4") (pin "2") (pinfunction "2_2") (pintype "power_in"))
      (node (ref "R47") (pin "1") (pinfunction "1_1") (pintype "passive"))
      (node (ref "R61") (pin "1") (pinfunction "1_1") (pintype "passive"))
    )
    (net (code "83") (name "Net-(FB5-Pad2)") (class "Default")
      (node (ref "FB5") (pin "2") (pinfunction "2_2") (pintype "power_in"))
      (node (ref "R73") (pin "1") (pinfunction "1_1") (pintype "passive"))
      (node (ref "R83") (pin "1") (pinfunction "1_1") (pintype "passive"))
    )
    (net (code "84") (name "Net-(FB6-Pad1)") (class "Default")
      (node (ref "FB6") (pin "1") (pinfunction "1_1") (pintype "power_in"))
      (node (ref "J2") (pin "21") (pinfunction "21_21") (pintype "passive"))
      (node (ref "R98") (pin "1") (pinfunction "1_1") (pintype "passive"))
    )
    (net (code "85") (name "Net-(FB7-Pad1)") (class "Default")
      (node (ref "FB7") (pin "1") (pinfunction "1_1") (pintype "power_in"))
      (node (ref "J2") (pin "9") (pinfunction "9_9") (pintype "passive"))
      (node (ref "R99") (pin "1") (pinfunction "1_1") (pintype "passive"))
    )
    (net (code "86") (name "Net-(FB8-Pad1)") (class "Default")
      (node (ref "FB8") (pin "1") (pinfunction "1_1") (pintype "power_in"))
      (node (ref "J2") (pin "22") (pinfunction "22_22") (pintype "passive"))
      (node (ref "R100") (pin "1") (pinfunction "1_1") (pintype "passive"))
    )
    (net (code "87") (name "Net-(FB9-Pad1)") (class "Default")
      (node (ref "FB9") (pin "1") (pinfunction "1_1") (pintype "power_in"))
      (node (ref "J2") (pin "10") (pinfunction "10_10") (pintype "passive"))
      (node (ref "R101") (pin "1") (pinfunction "1_1") (pintype "passive"))
    )
    (net (code "88") (name "Net-(FB10-Pad2)") (class "Default")
      (node (ref "FB10") (pin "2") (pinfunction "2_2") (pintype "power_in"))
      (node (ref "R106") (pin "1") (pinfunction "1_1") (pintype "passive"))
      (node (ref "R116") (pin "1") (pinfunction "1_1") (pintype "passive"))
    )
    (net (code "89") (name "Net-(FB13-Pad1)") (class "Default")
      (node (ref "FB13") (pin "1") (pinfunction "1_1") (pintype "power_in"))
      (node (ref "R174") (pin "2") (pinfunction "2_2") (pintype "passive"))
      (node (ref "R175") (pin "1") (pinfunction "1_1") (pintype "passive"))
    )
    (net (code "90") (name "Net-(P1-Pad3)") (class "Default")
      (node (ref "P1") (pin "3") (pinfunction "3_3") (pintype "passive"))
      (node (ref "R14") (pin "2") (pinfunction "2_2") (pintype "passive"))
      (node (ref "R15") (pin "2") (pinfunction "2_2") (pintype "passive"))
    )
    (net (code "91") (name "Net-(Q5-GND1)") (class "Default")
      (node (ref "C84") (pin "2") (pinfunction "2_2") (pintype "passive"))
      (node (ref "C85") (pin "2") (pinfunction "2_2") (pintype "passive"))
      (node (ref "Q5") (pin "4") (pinfunction "GND1_4") (pintype "power_in"))
      (node (ref "R154") (pin "1") (pinfunction "1_1") (pintype "passive"))
      (node (ref "R162") (pin "2") (pinfunction "2_2") (pintype "passive"))
      (node (ref "R168") (pin "1") (pinfunction "1_1") (pintype "passive"))
      (node (ref "TP46") (pin "1") (pinfunction "1_1") (pintype "passive"))
    )
    (net (code "92") (name "Net-(Q5-SHDN)") (class "Default")
      (node (ref "Q5") (pin "3") (pinfunction "SHDN_3") (pintype "input"))
      (node (ref "R163") (pin "2") (pinfunction "2_2") (pintype "passive"))
      (node (ref "R167") (pin "1") (pinfunction "1_1") (pintype "passive"))
      (node (ref "R92") (pin "1") (pinfunction "1_1") (pintype "passive"))
    )
    (net (code "93") (name "Net-(Q5-VDD2)") (class "Default")
      (node (ref "C82") (pin "1") (pinfunction "1_1") (pintype "passive"))
      (node (ref "C83") (pin "1") (pinfunction "1_1") (pintype "passive"))
      (node (ref "Q5") (pin "8") (pinfunction "VDD2_8") (pintype "power_in"))
      (node (ref "R149") (pin "1") (pinfunction "1_1") (pintype "passive"))
      (node (ref "R150") (pin "1") (pinfunction "1_1") (pintype "passive"))
    )
    (net (code "94") (name "Net-(Q5-VIN)") (class "Default")
      (node (ref "C84") (pin "1") (pinfunction "1_1") (pintype "passive"))
      (node (ref "Q5") (pin "2") (pinfunction "VIN_2") (pintype "power_in"))
      (node (ref "R147") (pin "1") (pinfunction "1_1") (pintype "passive"))
      (node (ref "R148") (pin "1") (pinfunction "1_1") (pintype "passive"))
      (node (ref "R151") (pin "2") (pinfunction "2_2") (pintype "passive"))
      (node (ref "R152") (pin "2") (pinfunction "2_2") (pintype "passive"))
      (node (ref "TP41") (pin "1") (pinfunction "1_1") (pintype "passive"))
    )
    (net (code "95") (name "Net-(Q5-VOUT+)") (class "Default")
      (node (ref "Q5") (pin "7") (pinfunction "VOUT+_7") (pintype "passive"))
      (node (ref "R153") (pin "1") (pinfunction "1_1") (pintype "passive"))
      (node (ref "R157") (pin "2") (pinfunction "2_2") (pintype "passive"))
      (node (ref "TP43") (pin "1") (pinfunction "1_1") (pintype "passive"))
    )
    (net (code "96") (name "Net-(Q5-VOUT-)") (class "Default")
      (node (ref "C81") (pin "1") (pinfunction "1_1") (pintype "passive"))
      (node (ref "Q5") (pin "6") (pinfunction "VOUT-_6") (pintype "passive"))
      (node (ref "R158") (pin "2") (pinfunction "2_2") (pintype "passive"))
      (node (ref "R159") (pin "1") (pinfunction "1_1") (pintype "passive"))
      (node (ref "TP44") (pin "1") (pinfunction "1_1") (pintype "passive"))
    )
    (net (code "97") (name "Net-(R13-Pad2)") (class "Default")
      (node (ref "R13") (pin "2") (pinfunction "2_2") (pintype "passive"))
      (node (ref "R19") (pin "1") (pinfunction "1_1") (pintype "passive"))
      (node (ref "R22") (pin "2") (pinfunction "2_2") (pintype "passive"))
    )
    (net (code "98") (name "Net-(R38-Pad2)") (class "Default")
      (node (ref "R38") (pin "2") (pinfunction "2_2") (pintype "passive"))
      (node (ref "R42") (pin "1") (pinfunction "1_1") (pintype "passive"))
    )
    (net (code "99") (name "Net-(R39-Pad2)") (class "Default")
      (node (ref "R39") (pin "2") (pinfunction "2_2") (pintype "passive"))
      (node (ref "R43") (pin "1") (pinfunction "1_1") (pintype "passive"))
    )
    (net (code "100") (name "Net-(R46-Pad2)") (class "Default")
      (node (ref "R46") (pin "2") (pinfunction "2_2") (pintype "passive"))
      (node (ref "R50") (pin "1") (pinfunction "1_1") (pintype "passive"))
      (node (ref "R55") (pin "2") (pinfunction "2_2") (pintype "passive"))
    )
    (net (code "101") (name "Net-(R72-Pad2)") (class "Default")
      (node (ref "R72") (pin "2") (pinfunction "2_2") (pintype "passive"))
      (node (ref "R76") (pin "1") (pinfunction "1_1") (pintype "passive"))
      (node (ref "R79") (pin "2") (pinfunction "2_2") (pintype "passive"))
    )
    (net (code "102") (name "Net-(R109-Pad1)") (class "Default")
      (node (ref "R109") (pin "1") (pinfunction "1_1") (pintype "passive"))
      (node (ref "R112") (pin "2") (pinfunction "2_2") (pintype "passive"))
      (node (ref "R97") (pin "2") (pinfunction "2_2") (pintype "passive"))
    )
    (net (code "103") (name "Net-(R123-Pad1)") (class "Default")
      (node (ref "R123") (pin "1") (pinfunction "1_1") (pintype "passive"))
      (node (ref "R124") (pin "2") (pinfunction "2_2") (pintype "passive"))
      (node (ref "R132") (pin "1") (pinfunction "1_1") (pintype "passive"))
      (node (ref "TP30") (pin "1") (pinfunction "1_1") (pintype "passive"))
    )
    (net (code "104") (name "Net-(R123-Pad2)") (class "Default")
      (node (ref "R123") (pin "2") (pinfunction "2_2") (pintype "passive"))
      (node (ref "U17") (pin "11") (pinfunction "OUT_11") (pintype "passive"))
    )
    (net (code "105") (name "Net-(R126-Pad2)") (class "Default")
      (node (ref "R126") (pin "2") (pinfunction "2_2") (pintype "passive"))
      (node (ref "R127") (pin "1") (pinfunction "1_1") (pintype "passive"))
    )
    (net (code "106") (name "Net-(R141-Pad2)") (class "Default")
      (node (ref "R141") (pin "2") (pinfunction "2_2") (pintype "passive"))
      (node (ref "R142") (pin "2") (pinfunction "2_2") (pintype "passive"))
      (node (ref "R147") (pin "2") (pinfunction "2_2") (pintype "passive"))
      (node (ref "R148") (pin "2") (pinfunction "2_2") (pintype "passive"))
      (node (ref "TP40") (pin "1") (pinfunction "1_1") (pintype "passive"))
    )
    (net (code "107") (name "Net-(R155-Pad1)") (class "Default")
      (node (ref "R155") (pin "1") (pinfunction "1_1") (pintype "passive"))
      (node (ref "R156") (pin "2") (pinfunction "2_2") (pintype "passive"))
    )
    (net (code "108") (name "Net-(R156-Pad1)") (class "Default")
      (node (ref "R156") (pin "1") (pinfunction "1_1") (pintype "passive"))
      (node (ref "R160") (pin "1") (pinfunction "1_1") (pintype "passive"))
      (node (ref "R161") (pin "1") (pinfunction "1_1") (pintype "passive"))
    )
    (net (code "109") (name "Net-(R161-Pad2)") (class "Default")
      (node (ref "R161") (pin "2") (pinfunction "2_2") (pintype "passive"))
      (node (ref "R166") (pin "1") (pinfunction "1_1") (pintype "passive"))
      (node (ref "R171") (pin "2") (pinfunction "2_2") (pintype "passive"))
      (node (ref "R172") (pin "1") (pinfunction "1_1") (pintype "passive"))
    )
    (net (code "110") (name "Net-(R165-Pad1)") (class "Default")
      (node (ref "R165") (pin "1") (pinfunction "1_1") (pintype "passive"))
      (node (ref "R166") (pin "2") (pinfunction "2_2") (pintype "passive"))
    )
    (net (code "111") (name "Net-(U1-on{slash}off)") (class "Default")
      (node (ref "U1") (pin "6") (pinfunction "on/off_6") (pintype "passive"))
      (node (ref "U3") (pin "4") (pinfunction "C_4") (pintype "passive"))
    )
    (net (code "112") (name "Net-(U2-A)") (class "Default")
      (node (ref "R4") (pin "2") (pinfunction "2_2") (pintype "passive"))
      (node (ref "U2") (pin "2") (pinfunction "A_2") (pintype "input"))
    )
    (net (code "113") (name "Net-(U2-NC)") (class "Default")
      (node (ref "R6") (pin "2") (pinfunction "2_2") (pintype "passive"))
      (node (ref "U2") (pin "1") (pinfunction "NC_1") (pintype "passive"))
    )
    (net (code "114") (name "Net-(U2-VCC)") (class "Default")
      (node (ref "C1") (pin "1") (pinfunction "1_1") (pintype "passive"))
      (node (ref "R2") (pin "1") (pinfunction "1_1") (pintype "passive"))
      (node (ref "R3") (pin "2") (pinfunction "2_2") (pintype "passive"))
      (node (ref "U2") (pin "5") (pinfunction "VCC_5") (pintype "power_in"))
    )
    (net (code "115") (name "Net-(U3-A)") (class "Default")
      (node (ref "R5") (pin "2") (pinfunction "2_2") (pintype "passive"))
      (node (ref "U3") (pin "1") (pinfunction "A_1") (pintype "passive"))
    )
    (net (code "116") (name "Net-(U4-A)") (class "Default")
      (node (ref "R16") (pin "2") (pinfunction "2_2") (pintype "passive"))
      (node (ref "U4") (pin "2") (pinfunction "A_2") (pintype "input"))
    )
    (net (code "117") (name "Net-(U4-NC)") (class "Default")
      (node (ref "R21") (pin "2") (pinfunction "2_2") (pintype "passive"))
      (node (ref "U4") (pin "1") (pinfunction "NC_1") (pintype "passive"))
    )
    (net (code "118") (name "Net-(U4-VCC)") (class "Default")
      (node (ref "C5") (pin "1") (pinfunction "1_1") (pintype "passive"))
      (node (ref "R11") (pin "1") (pinfunction "1_1") (pintype "passive"))
      (node (ref "R12") (pin "2") (pinfunction "2_2") (pintype "passive"))
      (node (ref "U4") (pin "5") (pinfunction "VCC_5") (pintype "power_in"))
    )
    (net (code "119") (name "Net-(U5-ANODE)") (class "Default")
      (node (ref "R17") (pin "2") (pinfunction "2_2") (pintype "passive"))
      (node (ref "R23") (pin "1") (pinfunction "1_1") (pintype "passive"))
      (node (ref "U5") (pin "1") (pinfunction "ANODE_1") (pintype "passive"))
    )
    (net (code "120") (name "Net-(U5-NC)") (class "Default")
      (node (ref "R25") (pin "2") (pinfunction "2_2") (pintype "passive"))
      (node (ref "U5") (pin "2") (pinfunction "NC_2") (pintype "passive"))
    )
    (net (code "121") (name "Net-(U6-IN)") (class "Default")
      (node (ref "R18") (pin "2") (pinfunction "2_2") (pintype "passive"))
      (node (ref "U6") (pin "2") (pinfunction "IN_2") (pintype "input"))
    )
    (net (code "122") (name "Net-(U6-NC)") (class "Default")
      (node (ref "R29") (pin "2") (pinfunction "2_2") (pintype "passive"))
      (node (ref "U6") (pin "3") (pinfunction "NC_3") (pintype "passive"))
    )
    (net (code "123") (name "Net-(U7-A)") (class "Default")
      (node (ref "R47") (pin "2") (pinfunction "2_2") (pintype "passive"))
      (node (ref "U7") (pin "2") (pinfunction "A_2") (pintype "input"))
    )
    (net (code "124") (name "Net-(U7-NC)") (class "Default")
      (node (ref "R53") (pin "2") (pinfunction "2_2") (pintype "passive"))
      (node (ref "U7") (pin "1") (pinfunction "NC_1") (pintype "passive"))
    )
    (net (code "125") (name "Net-(U7-VCC)") (class "Default")
      (node (ref "C20") (pin "1") (pinfunction "1_1") (pintype "passive"))
      (node (ref "R44") (pin "1") (pinfunction "1_1") (pintype "passive"))
      (node (ref "R45") (pin "2") (pinfunction "2_2") (pintype "passive"))
      (node (ref "U7") (pin "5") (pinfunction "VCC_5") (pintype "power_in"))
    )
    (net (code "126") (name "Net-(U8-ANODE)") (class "Default")
      (node (ref "R48") (pin "2") (pinfunction "2_2") (pintype "passive"))
      (node (ref "R56") (pin "1") (pinfunction "1_1") (pintype "passive"))
      (node (ref "U8") (pin "1") (pinfunction "ANODE_1") (pintype "passive"))
    )
    (net (code "127") (name "Net-(U8-NC)") (class "Default")
      (node (ref "R59") (pin "2") (pinfunction "2_2") (pintype "passive"))
      (node (ref "U8") (pin "2") (pinfunction "NC_2") (pintype "passive"))
    )
    (net (code "128") (name "Net-(U9-IN)") (class "Default")
      (node (ref "R49") (pin "2") (pinfunction "2_2") (pintype "passive"))
      (node (ref "U9") (pin "2") (pinfunction "IN_2") (pintype "input"))
    )
    (net (code "129") (name "Net-(U9-NC)") (class "Default")
      (node (ref "R63") (pin "2") (pinfunction "2_2") (pintype "passive"))
      (node (ref "U9") (pin "3") (pinfunction "NC_3") (pintype "passive"))
    )
    (net (code "130") (name "Net-(U10-A)") (class "Default")
      (node (ref "R73") (pin "2") (pinfunction "2_2") (pintype "passive"))
      (node (ref "U10") (pin "2") (pinfunction "A_2") (pintype "input"))
    )
    (net (code "131") (name "Net-(U10-NC)") (class "Default")
      (node (ref "R78") (pin "2") (pinfunction "2_2") (pintype "passive"))
      (node (ref "U10") (pin "1") (pinfunction "NC_1") (pintype "passive"))
    )
    (net (code "132") (name "Net-(U10-VCC)") (class "Default")
      (node (ref "C41") (pin "1") (pinfunction "1_1") (pintype "passive"))
      (node (ref "R70") (pin "1") (pinfunction "1_1") (pintype "passive"))
      (node (ref "R71") (pin "2") (pinfunction "2_2") (pintype "passive"))
      (node (ref "U10") (pin "5") (pinfunction "VCC_5") (pintype "power_in"))
    )
    (net (code "133") (name "Net-(U11-ANODE)") (class "Default")
      (node (ref "R74") (pin "2") (pinfunction "2_2") (pintype "passive"))
      (node (ref "R80") (pin "1") (pinfunction "1_1") (pintype "passive"))
      (node (ref "U11") (pin "1") (pinfunction "ANODE_1") (pintype "passive"))
    )
    (net (code "134") (name "Net-(U11-NC)") (class "Default")
      (node (ref "R81") (pin "2") (pinfunction "2_2") (pintype "passive"))
      (node (ref "U11") (pin "2") (pinfunction "NC_2") (pintype "passive"))
    )
    (net (code "135") (name "Net-(U12-IN)") (class "Default")
      (node (ref "R75") (pin "2") (pinfunction "2_2") (pintype "passive"))
      (node (ref "U12") (pin "2") (pinfunction "IN_2") (pintype "input"))
    )
    (net (code "136") (name "Net-(U12-NC)") (class "Default")
      (node (ref "R85") (pin "2") (pinfunction "2_2") (pintype "passive"))
      (node (ref "U12") (pin "3") (pinfunction "NC_3") (pintype "passive"))
    )
    (net (code "137") (name "Net-(U13-A)") (class "Default")
      (node (ref "R106") (pin "2") (pinfunction "2_2") (pintype "passive"))
      (node (ref "U13") (pin "2") (pinfunction "A_2") (pintype "input"))
    )
    (net (code "138") (name "Net-(U13-NC)") (class "Default")
      (node (ref "R111") (pin "2") (pinfunction "2_2") (pintype "passive"))
      (node (ref "U13") (pin "1") (pinfunction "NC_1") (pintype "passive"))
    )
    (net (code "139") (name "Net-(U13-VCC)") (class "Default")
      (node (ref "C53") (pin "1") (pinfunction "1_1") (pintype "passive"))
      (node (ref "R95") (pin "1") (pinfunction "1_1") (pintype "passive"))
      (node (ref "R96") (pin "2") (pinfunction "2_2") (pintype "passive"))
      (node (ref "U13") (pin "5") (pinfunction "VCC_5") (pintype "power_in"))
    )
    (net (code "140") (name "Net-(U14-ANODE)") (class "Default")
      (node (ref "R107") (pin "2") (pinfunction "2_2") (pintype "passive"))
      (node (ref "R113") (pin "1") (pinfunction "1_1") (pintype "passive"))
      (node (ref "U14") (pin "1") (pinfunction "ANODE_1") (pintype "passive"))
    )
    (net (code "141") (name "Net-(U14-NC)") (class "Default")
      (node (ref "R114") (pin "2") (pinfunction "2_2") (pintype "passive"))
      (node (ref "U14") (pin "2") (pinfunction "NC_2") (pintype "passive"))
    )
    (net (code "142") (name "Net-(U15-IN)") (class "Default")
      (node (ref "R108") (pin "2") (pinfunction "2_2") (pintype "passive"))
      (node (ref "U15") (pin "2") (pinfunction "IN_2") (pintype "input"))
    )
    (net (code "143") (name "Net-(U15-NC)") (class "Default")
      (node (ref "R118") (pin "2") (pinfunction "2_2") (pintype "passive"))
      (node (ref "U15") (pin "3") (pinfunction "NC_3") (pintype "passive"))
    )
    (net (code "144") (name "Net-(U16-IN)") (class "Default")
      (node (ref "C62") (pin "2") (pinfunction "2_2") (pintype "passive"))
      (node (ref "C63") (pin "2") (pinfunction "2_2") (pintype "passive"))
      (node (ref "FB11") (pin "2") (pinfunction "2_2") (pintype "power_in"))
      (node (ref "U16") (pin "1") (pinfunction "~{SHDN}_1") (pintype "input"))
      (node (ref "U16") (pin "2") (pinfunction "IN_2") (pintype "power_in"))
    )
    (net (code "145") (name "Net-(U19-IN+)") (class "Default")
      (node (ref "C77") (pin "2") (pinfunction "2_2") (pintype "passive"))
      (node (ref "R133") (pin "2") (pinfunction "2_2") (pintype "passive"))
      (node (ref "R136") (pin "2") (pinfunction "2_2") (pintype "passive"))
      (node (ref "TP37") (pin "1") (pinfunction "1_1") (pintype "passive"))
      (node (ref "U19") (pin "3") (pinfunction "IN+_3") (pintype "input"))
    )
    (net (code "146") (name "Net-(U19-IN-)") (class "Default")
      (node (ref "C70") (pin "2") (pinfunction "2_2") (pintype "passive"))
      (node (ref "R126") (pin "1") (pinfunction "1_1") (pintype "passive"))
      (node (ref "R130") (pin "2") (pinfunction "2_2") (pintype "passive"))
      (node (ref "TP34") (pin "1") (pinfunction "1_1") (pintype "passive"))
      (node (ref "U19") (pin "4") (pinfunction "IN-_4") (pintype "input"))
    )
    (net (code "147") (name "Net-(U19-OUT)") (class "Default")
      (node (ref "C70") (pin "1") (pinfunction "1_1") (pintype "passive"))
      (node (ref "R127") (pin "2") (pinfunction "2_2") (pintype "passive"))
      (node (ref "R131") (pin "1") (pinfunction "1_1") (pintype "passive"))
      (node (ref "U19") (pin "1") (pinfunction "OUT_1") (pintype "output"))
    )
    (net (code "148") (name "Net-(U19-V-)") (class "Default")
      (node (ref "R134") (pin "1") (pinfunction "1_1") (pintype "passive"))
      (node (ref "R135") (pin "1") (pinfunction "1_1") (pintype "passive"))
      (node (ref "U19") (pin "2") (pinfunction "V-_2") (pintype "power_in"))
    )
    (net (code "149") (name "Net-(U20-CE)") (class "Default")
      (node (ref "R138") (pin "2") (pinfunction "2_2") (pintype "passive"))
      (node (ref "R139") (pin "1") (pinfunction "1_1") (pintype "passive"))
      (node (ref "U20") (pin "3") (pinfunction "CE_3") (pintype "input"))
    )
    (net (code "150") (name "Net-(U20-NC)") (class "Default")
      (node (ref "R137") (pin "1") (pinfunction "1_1") (pintype "passive"))
      (node (ref "U20") (pin "4") (pinfunction "NC_4") (pintype "passive"))
    )
    (net (code "151") (name "Output Current of FB to micro controller") (class "Default")
      (node (ref "FB12") (pin "2") (pinfunction "2_2") (pintype "power_in"))
      (node (ref "J2") (pin "2") (pinfunction "2_2") (pintype "passive"))
    )
    (net (code "152") (name "Output voltage of FB") (class "Default")
      (node (ref "FB13") (pin "2") (pinfunction "2_2") (pintype "power_in"))
      (node (ref "J2") (pin "3") (pinfunction "3_3") (pintype "passive"))
      (node (ref "TP47") (pin "1") (pinfunction "1_1") (pintype "passive"))
      (node (ref "TP60") (pin "1") (pinfunction "1_1") (pintype "passive"))
    )
    (net (code "153") (name "P1 OP37-2") (class "Default")
      (node (ref "R155") (pin "2") (pinfunction "2_2") (pintype "passive"))
      (node (ref "U21") (pin "1") (pinfunction "OFFSET_TRIM_1") (pintype "input"))
    )
    (net (code "154") (name "P2 OP37-2") (class "Default")
      (node (ref "C87") (pin "1") (pinfunction "1_1") (pintype "passive"))
      (node (ref "R158") (pin "1") (pinfunction "1_1") (pintype "passive"))
      (node (ref "R159") (pin "2") (pinfunction "2_2") (pintype "passive"))
      (node (ref "R169") (pin "2") (pinfunction "2_2") (pintype "passive"))
      (node (ref "R170") (pin "2") (pinfunction "2_2") (pintype "passive"))
      (node (ref "U21") (pin "2") (pinfunction "IN-_2") (pintype "input"))
    )
    (net (code "155") (name "P3 OP37-2") (class "Default")
      (node (ref "C86") (pin "1") (pinfunction "1_1") (pintype "passive"))
      (node (ref "R157") (pin "1") (pinfunction "1_1") (pintype "passive"))
      (node (ref "R164") (pin "1") (pinfunction "1_1") (pintype "passive"))
      (node (ref "U21") (pin "3") (pinfunction "IN+_3") (pintype "input"))
    )
    (net (code "156") (name "P4 OP37-2") (class "Default")
      (node (ref "R145") (pin "2") (pinfunction "2_2") (pintype "passive"))
      (node (ref "R146") (pin "2") (pinfunction "2_2") (pintype "passive"))
      (node (ref "U21") (pin "4") (pinfunction "VCC-_4") (pintype "power_in"))
    )
    (net (code "157") (name "P5 OP37-2") (class "Default")
      (node (ref "R143") (pin "1") (pinfunction "1_1") (pintype "passive"))
      (node (ref "U21") (pin "5") (pinfunction "NC_5") (pintype "passive"))
    )
    (net (code "158") (name "P6 OP37-2") (class "Default")
      (node (ref "C87") (pin "2") (pinfunction "2_2") (pintype "passive"))
      (node (ref "C88") (pin "1") (pinfunction "1_1") (pintype "passive"))
      (node (ref "R169") (pin "1") (pinfunction "1_1") (pintype "passive"))
      (node (ref "R170") (pin "1") (pinfunction "1_1") (pintype "passive"))
      (node (ref "R173") (pin "1") (pinfunction "1_1") (pintype "passive"))
      (node (ref "TP45") (pin "1") (pinfunction "1_1") (pintype "passive"))
      (node (ref "U21") (pin "6") (pinfunction "OUT_6") (pintype "output"))
    )
    (net (code "159") (name "P7 OP37-2") (class "Default")
      (node (ref "C80") (pin "1") (pinfunction "1_1") (pintype "passive"))
      (node (ref "R140") (pin "2") (pinfunction "2_2") (pintype "passive"))
      (node (ref "R144") (pin "2") (pinfunction "2_2") (pintype "passive"))
      (node (ref "U21") (pin "7") (pinfunction "VCC+_7") (pintype "power_in"))
    )
    (net (code "160") (name "P8 OP37-2") (class "Default")
      (node (ref "R165") (pin "2") (pinfunction "2_2") (pintype "passive"))
      (node (ref "U21") (pin "8") (pinfunction "OFFSET_TRIM_8") (pintype "input"))
    )
    (net (code "161") (name "Relay FB command") (class "Default")
      (node (ref "J2") (pin "11") (pinfunction "11_11") (pintype "passive"))
    )
    (net (code "162") (name "Source 1") (class "Default")
      (node (ref "C10") (pin "2") (pinfunction "2_2") (pintype "passive"))
      (node (ref "C14") (pin "1") (pinfunction "1_1") (pintype "passive"))
      (node (ref "C15") (pin "2") (pinfunction "2_2") (pintype "passive"))
      (node (ref "C16") (pin "2") (pinfunction "2_2") (pintype "passive"))
      (node (ref "C18") (pin "2") (pinfunction "2_2") (pintype "passive"))
      (node (ref "C19") (pin "1") (pinfunction "1_1") (pintype "passive"))
      (node (ref "C9") (pin "2") (pinfunction "2_2") (pintype "passive"))
      (node (ref "CR3") (pin "1") (pinfunction "A_1") (pintype "passive"))
      (node (ref "D13") (pin "2") (pinfunction "C_2") (pintype "passive"))
      (node (ref "D6") (pin "1") (pinfunction "A_1") (pintype "passive"))
      (node (ref "D7") (pin "1") (pinfunction "A_1") (pintype "passive"))
      (node (ref "D8") (pin "1") (pinfunction "A_1") (pintype "passive"))
      (node (ref "Q1") (pin "3") (pinfunction "E_3") (pintype "passive"))
      (node (ref "Q2") (pin "2") (pinfunction "C_2") (pintype "passive"))
      (node (ref "R20") (pin "1") (pinfunction "1_1") (pintype "passive"))
      (node (ref "R30") (pin "1") (pinfunction "1_1") (pintype "passive"))
      (node (ref "R33") (pin "1") (pinfunction "1_1") (pintype "passive"))
      (node (ref "R35") (pin "2") (pinfunction "2_2") (pintype "passive"))
      (node (ref "R52") (pin "2") (pinfunction "2_2") (pintype "passive"))
      (node (ref "R8") (pin "1") (pinfunction "1_1") (pintype "passive"))
      (node (ref "TP77") (pin "1") (pinfunction "1_1") (pintype "passive"))
      (node (ref "TP78") (pin "1") (pinfunction "1_1") (pintype "passive"))
      (node (ref "U17") (pin "1") (pinfunction "IN_1") (pintype "passive"))
      (node (ref "U17") (pin "2") (pinfunction "IN_2") (pintype "passive"))
      (node (ref "U17") (pin "3") (pinfunction "IN_3") (pintype "passive"))
      (node (ref "U6") (pin "4") (pinfunction "GND_4") (pintype "power_in"))
      (node (ref "U6") (pin "5") (pinfunction "GND_5") (pintype "power_in"))
    )
    (net (code "163") (name "Source 4") (class "Default")
      (node (ref "C11") (pin "2") (pinfunction "2_2") (pintype "passive"))
      (node (ref "C12") (pin "2") (pinfunction "2_2") (pintype "passive"))
      (node (ref "C13") (pin "2") (pinfunction "2_2") (pintype "passive"))
      (node (ref "C17") (pin "1") (pinfunction "1_1") (pintype "passive"))
      (node (ref "C23") (pin "1") (pinfunction "1_1") (pintype "passive"))
      (node (ref "C65") (pin "2") (pinfunction "2_2") (pintype "passive"))
      (node (ref "C66") (pin "2") (pinfunction "2_2") (pintype "passive"))
      (node (ref "CR15") (pin "1") (pinfunction "A_1") (pintype "passive"))
      (node (ref "D10") (pin "1") (pinfunction "A_1") (pintype "passive"))
      (node (ref "D14") (pin "2") (pinfunction "C_2") (pintype "passive"))
      (node (ref "D5") (pin "1") (pinfunction "A_1") (pintype "passive"))
      (node (ref "D9") (pin "1") (pinfunction "A_1") (pintype "passive"))
      (node (ref "L1") (pin "1") (pinfunction "1_1") (pintype "passive"))
      (node (ref "Q3") (pin "2") (pinfunction "C_2") (pintype "passive"))
      (node (ref "Q4") (pin "3") (pinfunction "E_3") (pintype "passive"))
      (node (ref "R110") (pin "1") (pinfunction "1_1") (pintype "passive"))
      (node (ref "R120") (pin "1") (pinfunction "1_1") (pintype "passive"))
      (node (ref "R34") (pin "1") (pinfunction "1_1") (pintype "passive"))
      (node (ref "R36") (pin "2") (pinfunction "2_2") (pintype "passive"))
      (node (ref "R54") (pin "2") (pinfunction "2_2") (pintype "passive"))
      (node (ref "R90") (pin "1") (pinfunction "1_1") (pintype "passive"))
      (node (ref "TP75") (pin "1") (pinfunction "1_1") (pintype "passive"))
      (node (ref "TP76") (pin "1") (pinfunction "1_1") (pintype "passive"))
      (node (ref "U15") (pin "4") (pinfunction "GND_4") (pintype "power_in"))
      (node (ref "U15") (pin "5") (pinfunction "GND_5") (pintype "power_in"))
    )
    (net (code "164") (name "Spare Analog FB 1") (class "Default")
      (node (ref "J2") (pin "4") (pinfunction "4_4") (pintype "passive"))
    )
    (net (code "165") (name "Spare Analog FB 2") (class "Default")
      (node (ref "J2") (pin "17") (pinfunction "17_17") (pintype "passive"))
    )
    (net (code "166") (name "Spare Analog FB 3") (class "Default")
      (node (ref "J2") (pin "5") (pinfunction "5_5") (pintype "passive"))
    )
    (net (code "167") (name "Spare Analog FB 4") (class "Default")
      (node (ref "J2") (pin "18") (pinfunction "18_18") (pintype "passive"))
    )
    (net (code "168") (name "Spare Dig FB 1") (class "Default")
      (node (ref "J2") (pin "20") (pinfunction "20_20") (pintype "passive"))
    )
    (net (code "169") (name "Spare Dig FB 2") (class "Default")
      (node (ref "J2") (pin "7") (pinfunction "7_7") (pintype "passive"))
    )
    (net (code "170") (name "Spare Dig FB 3") (class "Default")
      (node (ref "J2") (pin "19") (pinfunction "19_19") (pintype "passive"))
    )
    (net (code "171") (name "Spare Dig FB 4") (class "Default")
      (node (ref "J2") (pin "6") (pinfunction "6_6") (pintype "passive"))
    )
    (net (code "172") (name "VDD Sensor voltage out") (class "Default")
      (node (ref "C76") (pin "1") (pinfunction "1_1") (pintype "passive"))
      (node (ref "C85") (pin "1") (pinfunction "1_1") (pintype "passive"))
      (node (ref "C90") (pin "2") (pinfunction "2_2") (pintype "passive"))
      (node (ref "DS13") (pin "1") (pinfunction "A_1") (pintype "passive"))
      (node (ref "Q5") (pin "1") (pinfunction "VDD1_1") (pintype "power_in"))
      (node (ref "TP88") (pin "1") (pinfunction "1_1") (pintype "passive"))
      (node (ref "U18") (pin "3") (pinfunction "+Out_3") (pintype "passive"))
    )
    (net (code "173") (name "VGS 1") (class "Default")
      (node (ref "C10") (pin "1") (pinfunction "1_1") (pintype "passive"))
      (node (ref "C14") (pin "2") (pinfunction "2_2") (pintype "passive"))
      (node (ref "C47") (pin "1") (pinfunction "1_1") (pintype "passive"))
      (node (ref "C48") (pin "2") (pinfunction "2_2") (pintype "passive"))
      (node (ref "C6") (pin "1") (pinfunction "1_1") (pintype "passive"))
      (node (ref "C7") (pin "1") (pinfunction "1_1") (pintype "passive"))
      (node (ref "C8") (pin "2") (pinfunction "2_2") (pintype "passive"))
      (node (ref "C9") (pin "1") (pinfunction "1_1") (pintype "passive"))
      (node (ref "CR1") (pin "2") (pinfunction "K_2") (pintype "passive"))
      (node (ref "CR4") (pin "2") (pinfunction "K_2") (pintype "passive"))
      (node (ref "D7") (pin "2") (pinfunction "K_2") (pintype "passive"))
      (node (ref "DS6") (pin "1") (pinfunction "A_1") (pintype "passive"))
      (node (ref "PS1") (pin "14") (pinfunction "+VOUT_14") (pintype "output"))
      (node (ref "TP35") (pin "1") (pinfunction "1_1") (pintype "passive"))
      (node (ref "TP70") (pin "1") (pinfunction "1_1") (pintype "passive"))
      (node (ref "U5") (pin "6") (pinfunction "VDD_6") (pintype "power_in"))
      (node (ref "U6") (pin "1") (pinfunction "VCC_1") (pintype "power_in"))
      (node (ref "U6") (pin "8") (pinfunction "VCC_8") (pintype "power_in"))
    )
    (net (code "174") (name "VGS 2") (class "Default")
      (node (ref "C32") (pin "2") (pinfunction "2_2") (pintype "passive"))
      (node (ref "C33") (pin "1") (pinfunction "1_1") (pintype "passive"))
      (node (ref "C34") (pin "1") (pinfunction "1_1") (pintype "passive"))
      (node (ref "C36") (pin "2") (pinfunction "2_2") (pintype "passive"))
      (node (ref "C37") (pin "1") (pinfunction "1_1") (pintype "passive"))
      (node (ref "C38") (pin "1") (pinfunction "1_1") (pintype "passive"))
      (node (ref "C50") (pin "1") (pinfunction "1_1") (pintype "passive"))
      (node (ref "C51") (pin "2") (pinfunction "2_2") (pintype "passive"))
      (node (ref "CR5") (pin "2") (pinfunction "K_2") (pintype "passive"))
      (node (ref "CR8") (pin "2") (pinfunction "K_2") (pintype "passive"))
      (node (ref "D17") (pin "2") (pinfunction "K_2") (pintype "passive"))
      (node (ref "DS7") (pin "1") (pinfunction "A_1") (pintype "passive"))
      (node (ref "PS2") (pin "14") (pinfunction "+VOUT_14") (pintype "output"))
      (node (ref "TP54") (pin "1") (pinfunction "1_1") (pintype "passive"))
      (node (ref "TP81") (pin "1") (pinfunction "1_1") (pintype "passive"))
      (node (ref "U8") (pin "6") (pinfunction "VDD_6") (pintype "power_in"))
      (node (ref "U9") (pin "1") (pinfunction "VCC_1") (pintype "power_in"))
      (node (ref "U9") (pin "8") (pinfunction "VCC_8") (pintype "power_in"))
    )
    (net (code "175") (name "VGS 3") (class "Default")
      (node (ref "C35") (pin "2") (pinfunction "2_2") (pintype "passive"))
      (node (ref "C42") (pin "1") (pinfunction "1_1") (pintype "passive"))
      (node (ref "C43") (pin "1") (pinfunction "1_1") (pintype "passive"))
      (node (ref "C44") (pin "2") (pinfunction "2_2") (pintype "passive"))
      (node (ref "C45") (pin "1") (pinfunction "1_1") (pintype "passive"))
      (node (ref "C46") (pin "1") (pinfunction "1_1") (pintype "passive"))
      (node (ref "C54") (pin "2") (pinfunction "2_2") (pintype "passive"))
      (node (ref "C55") (pin "1") (pinfunction "1_1") (pintype "passive"))
      (node (ref "CR12") (pin "2") (pinfunction "K_2") (pintype "passive"))
      (node (ref "CR9") (pin "2") (pinfunction "K_2") (pintype "passive"))
      (node (ref "D18") (pin "2") (pinfunction "K_2") (pintype "passive"))
      (node (ref "DS8") (pin "1") (pinfunction "A_1") (pintype "passive"))
      (node (ref "PS3") (pin "14") (pinfunction "+VOUT_14") (pintype "output"))
      (node (ref "TP58") (pin "1") (pinfunction "1_1") (pintype "passive"))
      (node (ref "TP82") (pin "1") (pinfunction "1_1") (pintype "passive"))
      (node (ref "U11") (pin "6") (pinfunction "VDD_6") (pintype "power_in"))
      (node (ref "U12") (pin "1") (pinfunction "VCC_1") (pintype "power_in"))
      (node (ref "U12") (pin "8") (pinfunction "VCC_8") (pintype "power_in"))
    )
    (net (code "176") (name "VGS 4") (class "Default")
      (node (ref "C17") (pin "2") (pinfunction "2_2") (pintype "passive"))
      (node (ref "C57") (pin "1") (pinfunction "1_1") (pintype "passive"))
      (node (ref "C58") (pin "1") (pinfunction "1_1") (pintype "passive"))
      (node (ref "C59") (pin "2") (pinfunction "2_2") (pintype "passive"))
      (node (ref "C61") (pin "1") (pinfunction "1_1") (pintype "passive"))
      (node (ref "C65") (pin "1") (pinfunction "1_1") (pintype "passive"))
      (node (ref "C66") (pin "1") (pinfunction "1_1") (pintype "passive"))
      (node (ref "C67") (pin "2") (pinfunction "2_2") (pintype "passive"))
      (node (ref "CR13") (pin "2") (pinfunction "K_2") (pintype "passive"))
      (node (ref "CR16") (pin "2") (pinfunction "K_2") (pintype "passive"))
      (node (ref "D9") (pin "2") (pinfunction "K_2") (pintype "passive"))
      (node (ref "DS11") (pin "1") (pinfunction "A_1") (pintype "passive"))
      (node (ref "PS4") (pin "14") (pinfunction "+VOUT_14") (pintype "output"))
      (node (ref "TP62") (pin "1") (pinfunction "1_1") (pintype "passive"))
      (node (ref "TP72") (pin "1") (pinfunction "1_1") (pintype "passive"))
      (node (ref "U14") (pin "6") (pinfunction "VDD_6") (pintype "power_in"))
      (node (ref "U15") (pin "1") (pinfunction "VCC_1") (pintype "power_in"))
      (node (ref "U15") (pin "8") (pinfunction "VCC_8") (pintype "power_in"))
    )
    (net (code "177") (name "unconnected-(J2-PadM1)") (class "Default")
      (node (ref "J2") (pin "M1") (pinfunction "M1_M1") (pintype "passive"))
    )
    (net (code "178") (name "unconnected-(J2-PadM2)") (class "Default")
      (node (ref "J2") (pin "M2") (pinfunction "M2_M2") (pintype "passive"))
    )
    (net (code "179") (name "unconnected-(PS1-NC-Pad9)") (class "Default")
      (node (ref "PS1") (pin "9") (pinfunction "NC_9") (pintype "passive"))
    )
    (net (code "180") (name "unconnected-(PS1-NC1-Pad11)") (class "Default")
      (node (ref "PS1") (pin "11") (pinfunction "NC1_11") (pintype "passive"))
    )
    (net (code "181") (name "unconnected-(PS2-NC-Pad9)") (class "Default")
      (node (ref "PS2") (pin "9") (pinfunction "NC_9") (pintype "passive"))
    )
    (net (code "182") (name "unconnected-(PS2-NC1-Pad11)") (class "Default")
      (node (ref "PS2") (pin "11") (pinfunction "NC1_11") (pintype "passive"))
    )
    (net (code "183") (name "unconnected-(PS3-NC-Pad9)") (class "Default")
      (node (ref "PS3") (pin "9") (pinfunction "NC_9") (pintype "passive"))
    )
    (net (code "184") (name "unconnected-(PS3-NC1-Pad11)") (class "Default")
      (node (ref "PS3") (pin "11") (pinfunction "NC1_11") (pintype "passive"))
    )
    (net (code "185") (name "unconnected-(PS4-NC-Pad9)") (class "Default")
      (node (ref "PS4") (pin "9") (pinfunction "NC_9") (pintype "passive"))
    )
    (net (code "186") (name "unconnected-(PS4-NC1-Pad11)") (class "Default")
      (node (ref "PS4") (pin "11") (pinfunction "NC1_11") (pintype "passive"))
    )
    (net (code "187") (name "unconnected-(U1-trim-Pad4)") (class "Default")
      (node (ref "U1") (pin "4") (pinfunction "trim_4") (pintype "passive"))
    )
    (net (code "188") (name "unconnected-(U18-on{slash}off-Pad6)") (class "Default")
      (node (ref "U18") (pin "6") (pinfunction "on/off_6") (pintype "passive"))
    )
    (net (code "189") (name "unconnected-(U18-trim-Pad4)") (class "Default")
      (node (ref "U18") (pin "4") (pinfunction "trim_4") (pintype "passive"))
    )
  )
)
